# RFBoard.net
KiCad netlist of a schematic drawn in EAGLE
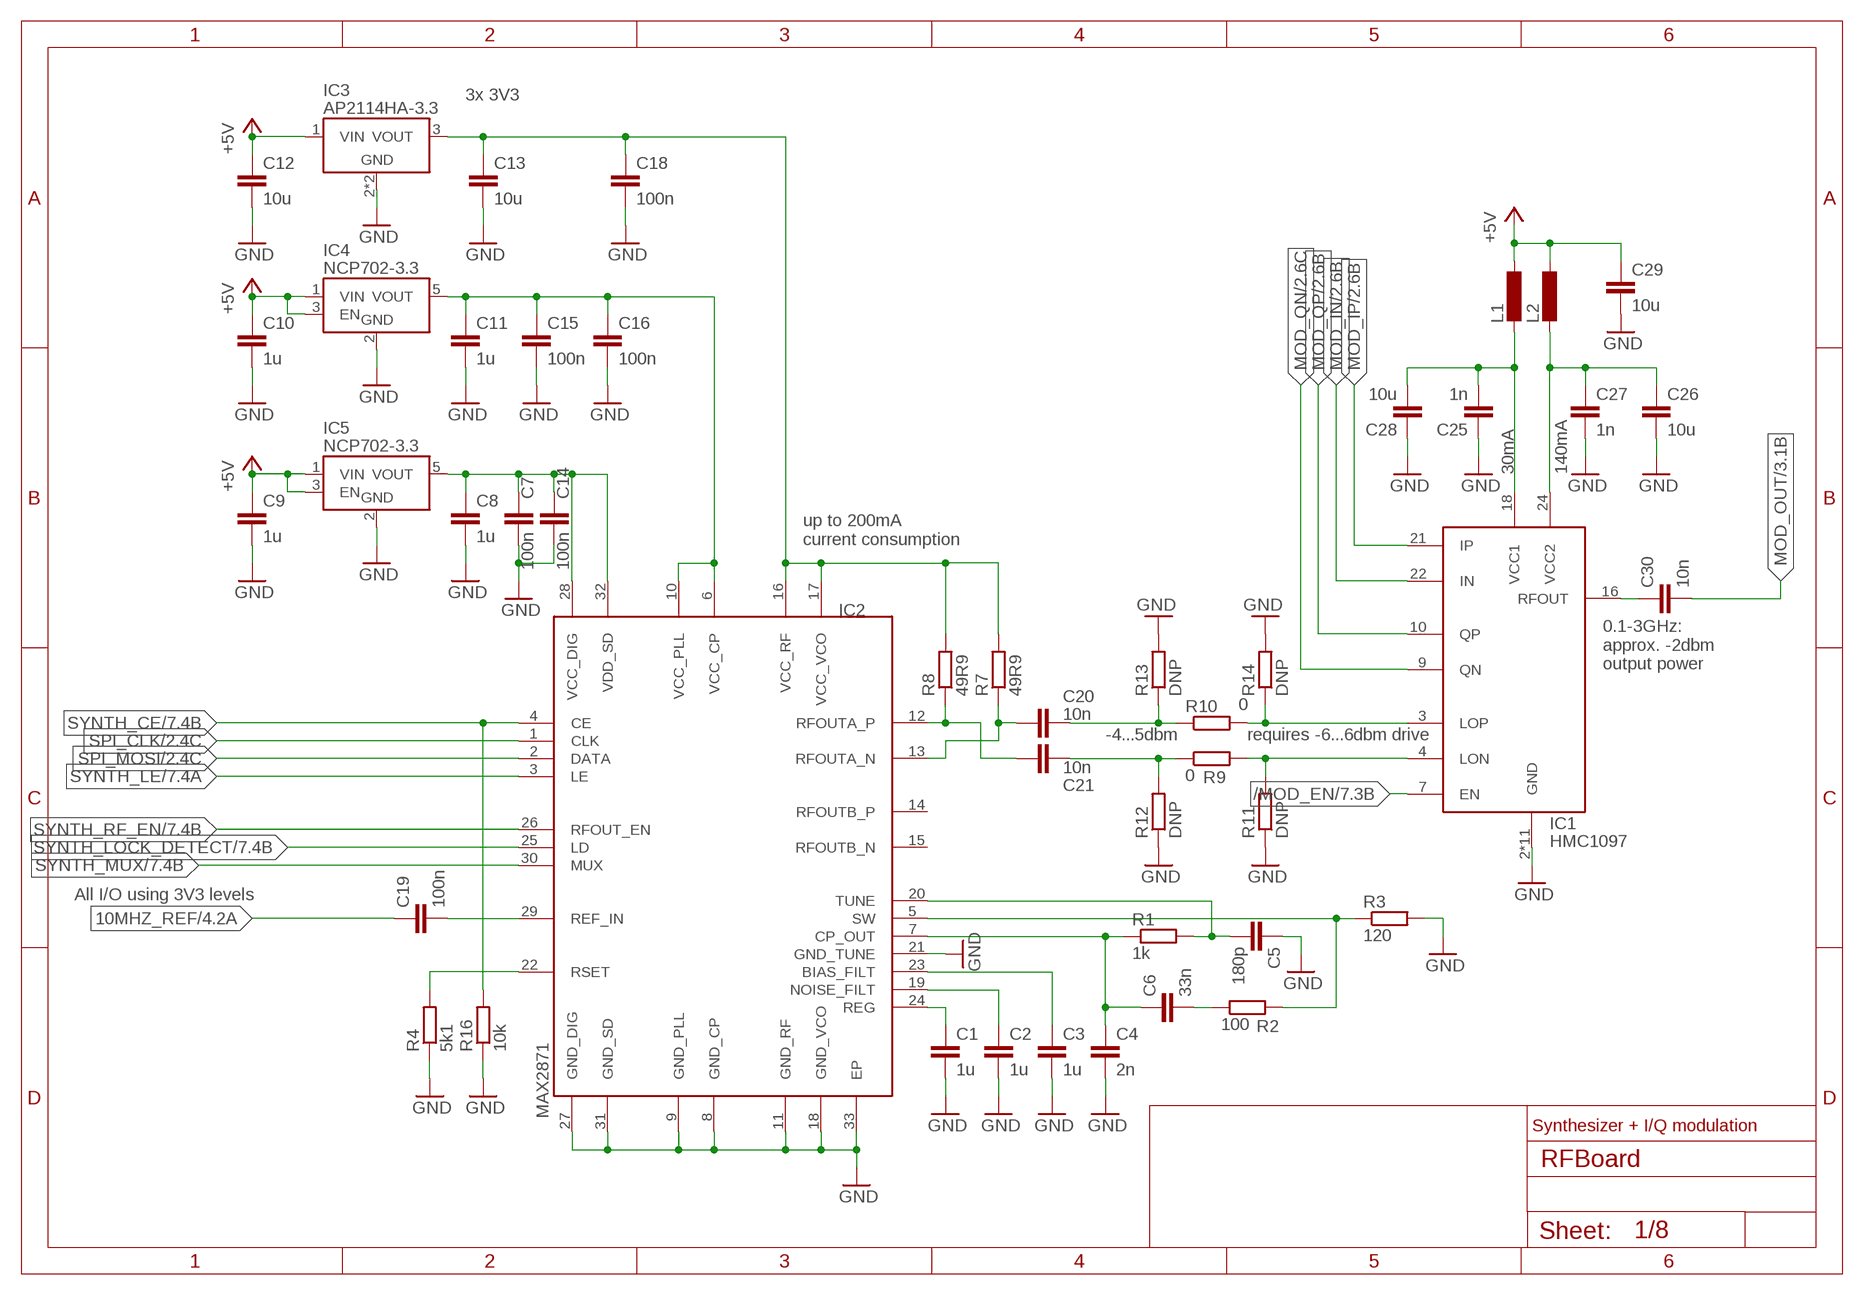
[diagram p0: schematic, sheet 1]
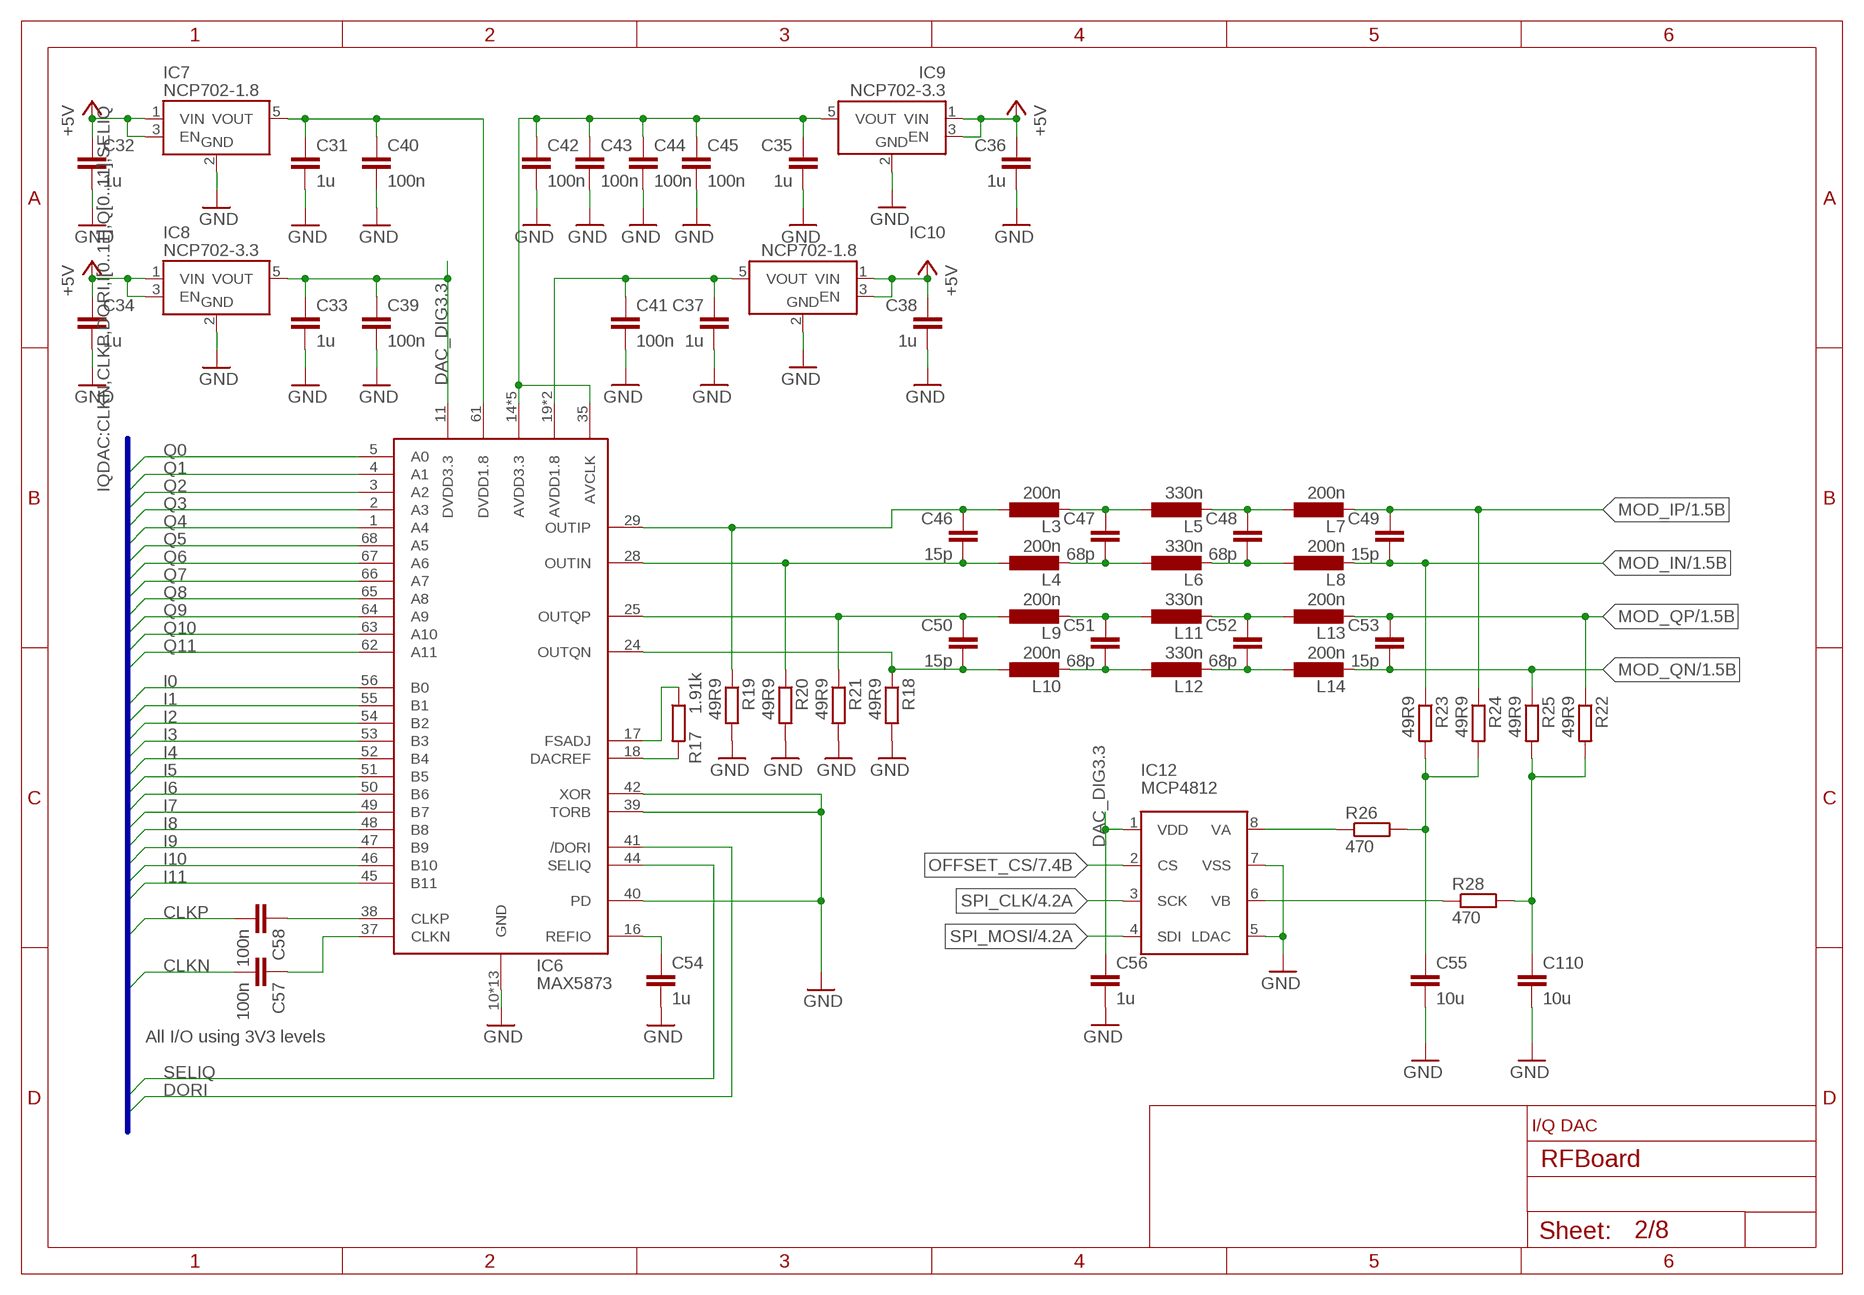
[diagram p1: schematic, sheet 2]
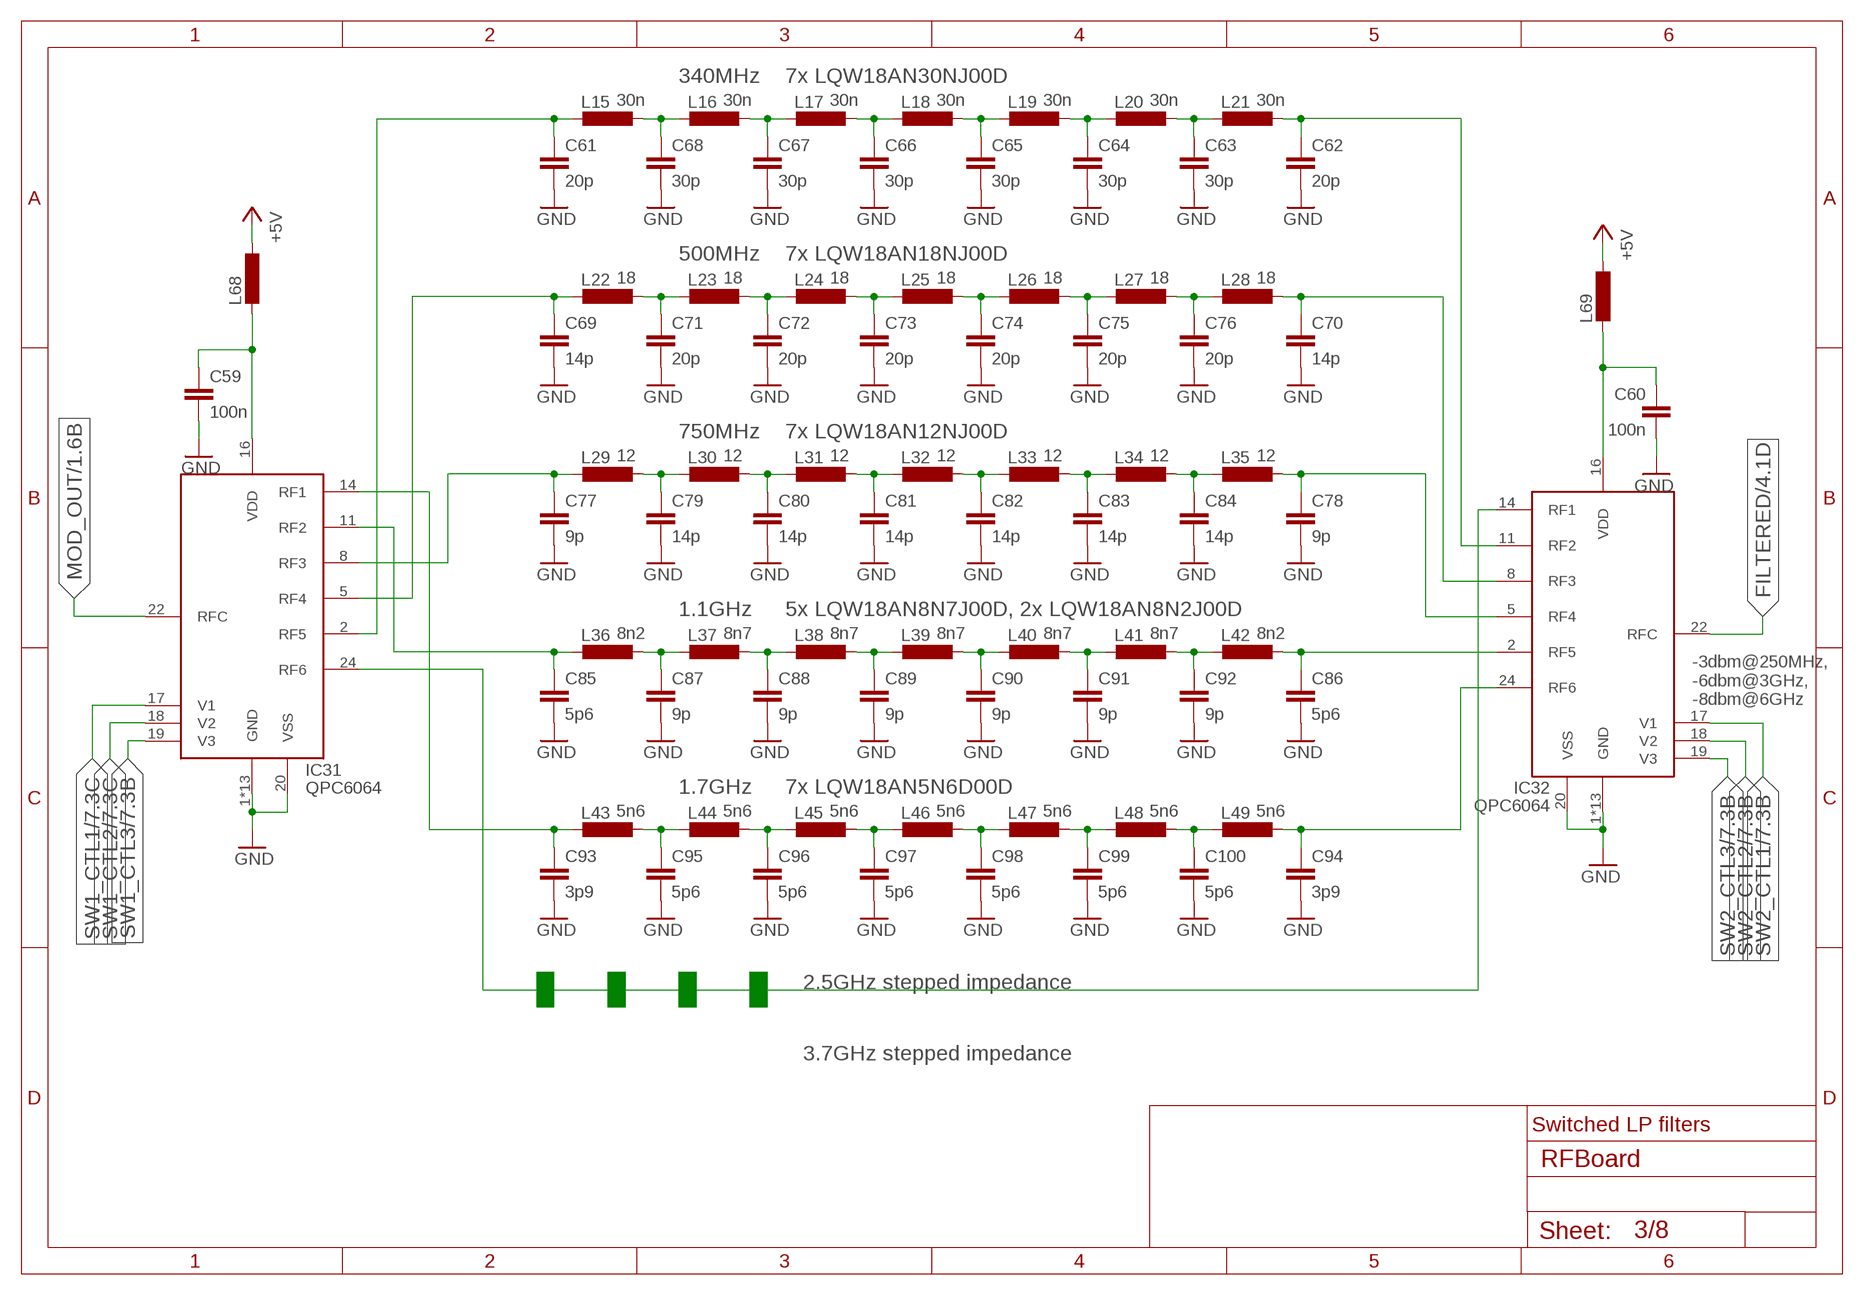
[diagram p2: schematic, sheet 3]
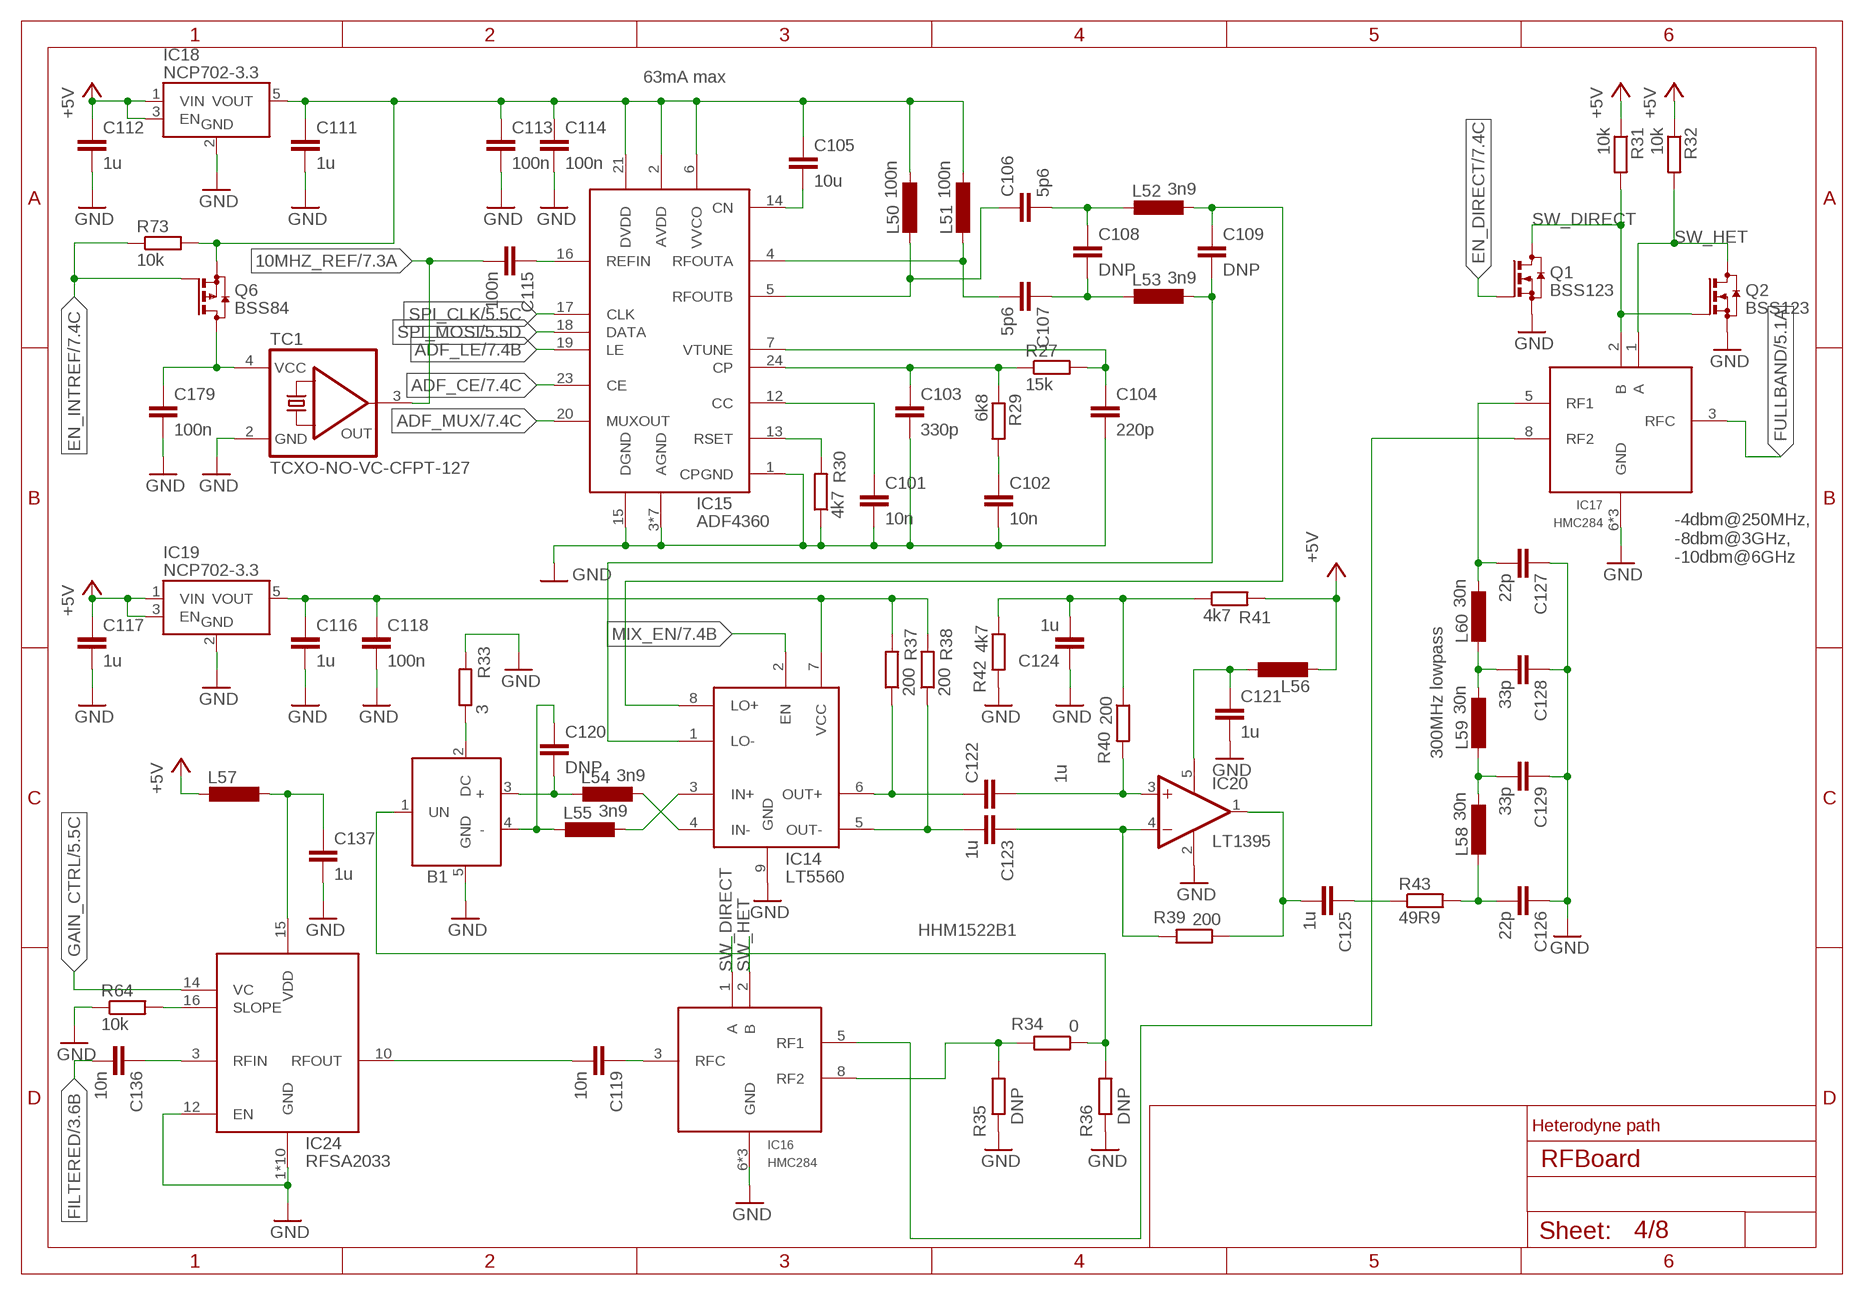
[diagram p3: schematic, sheet 4]
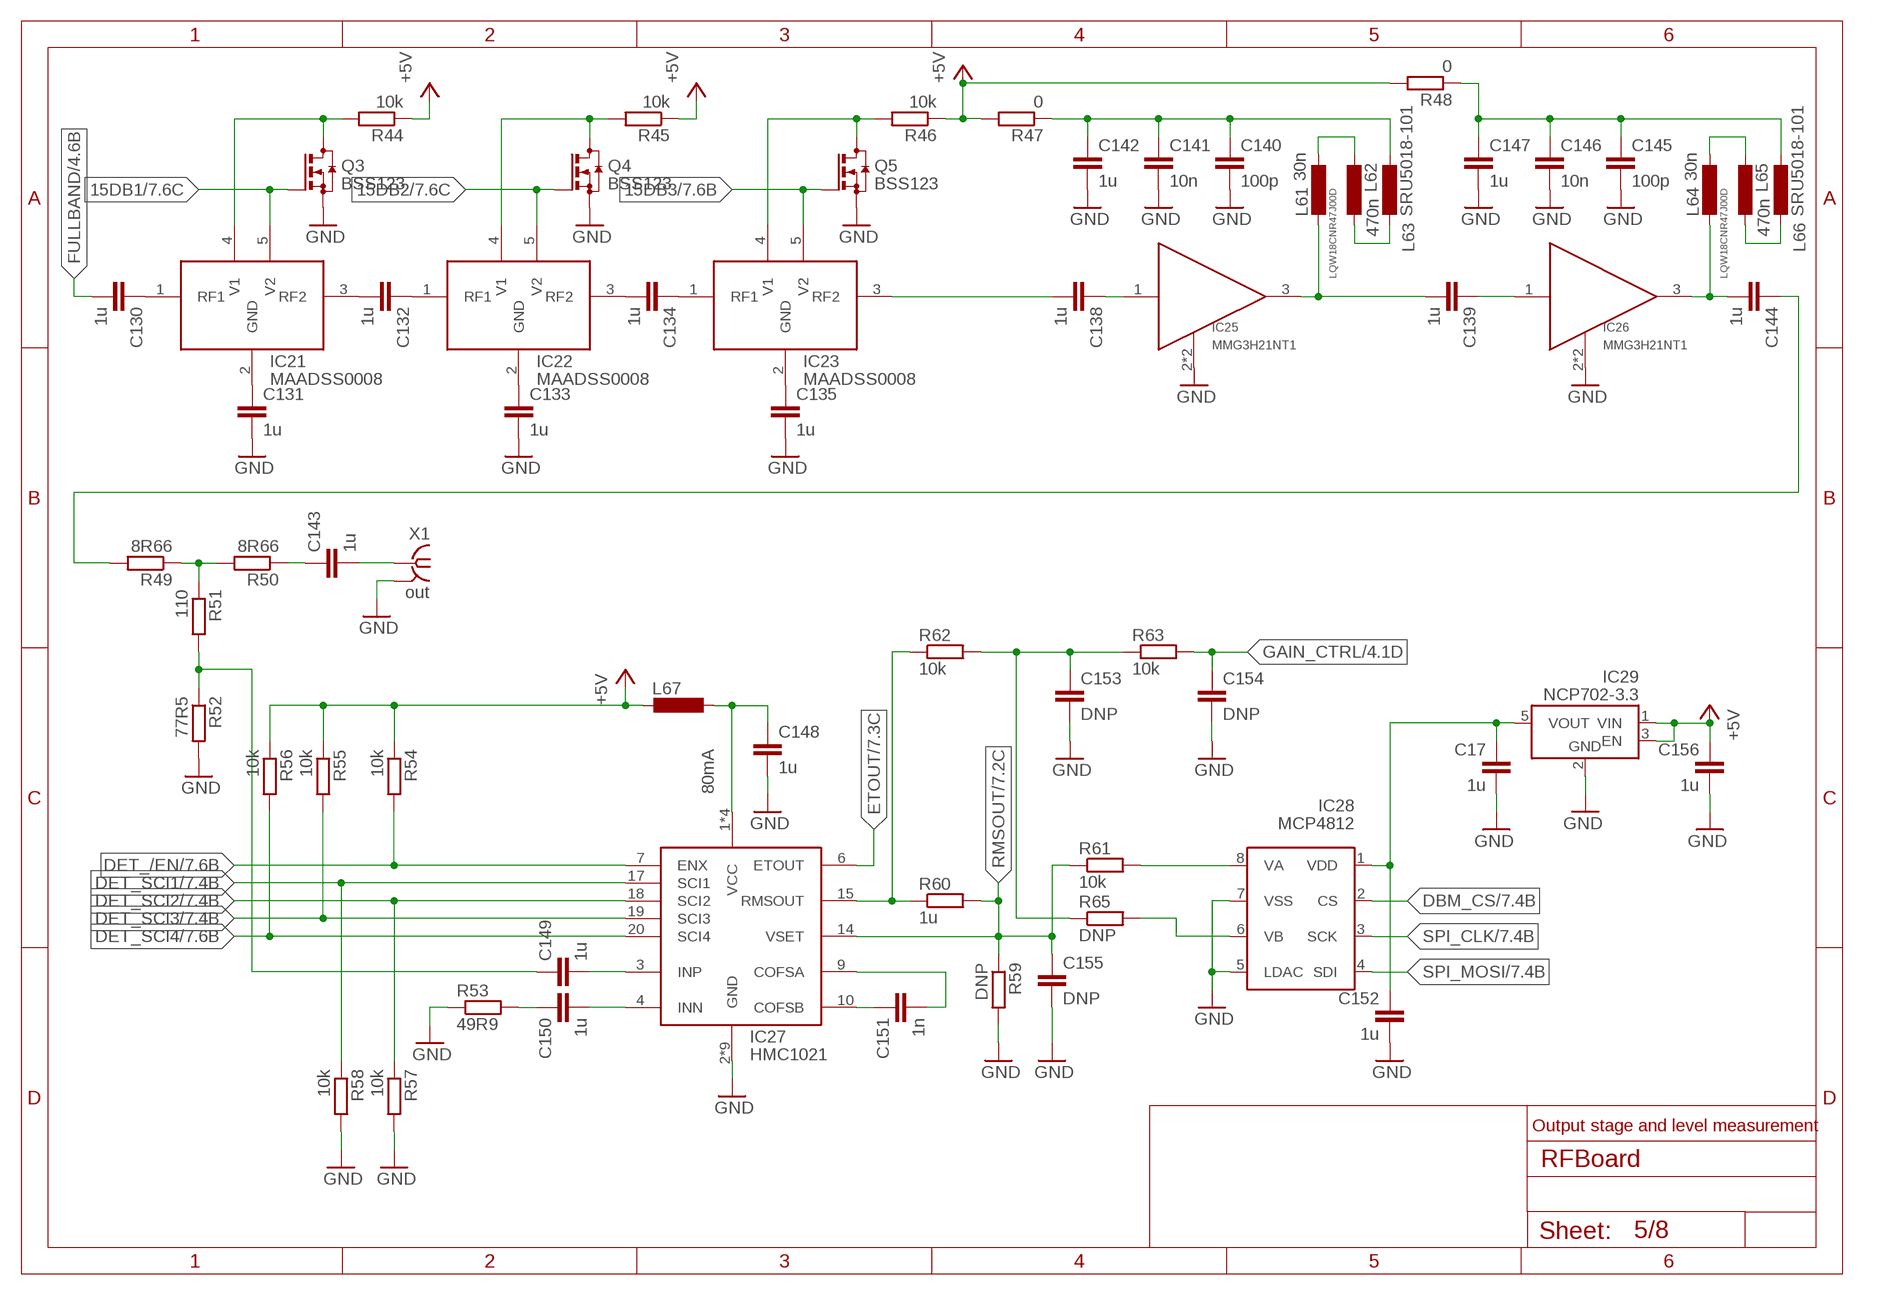
[diagram p4: schematic, sheet 5]
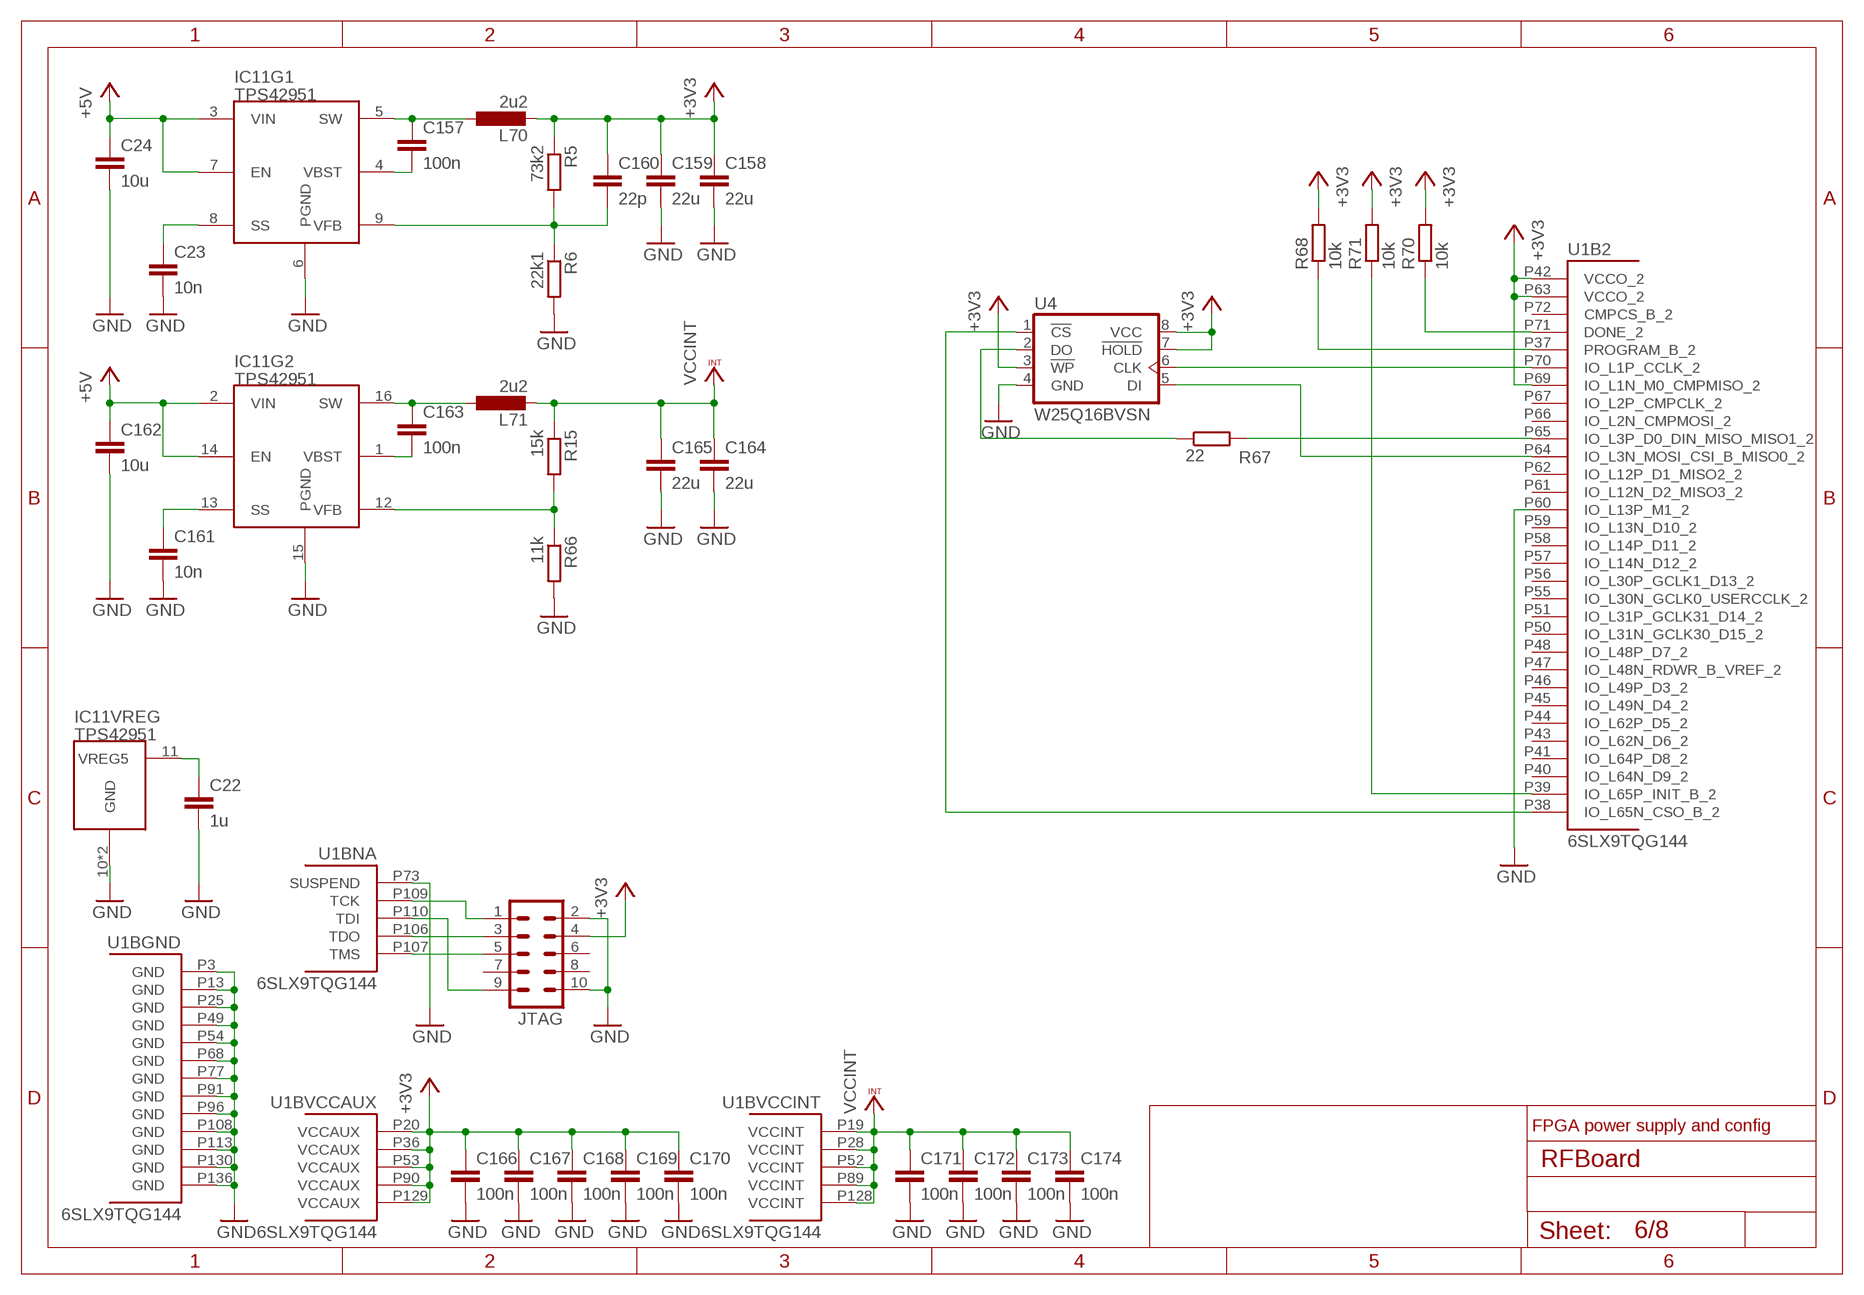
[diagram p5: schematic, sheet 6]
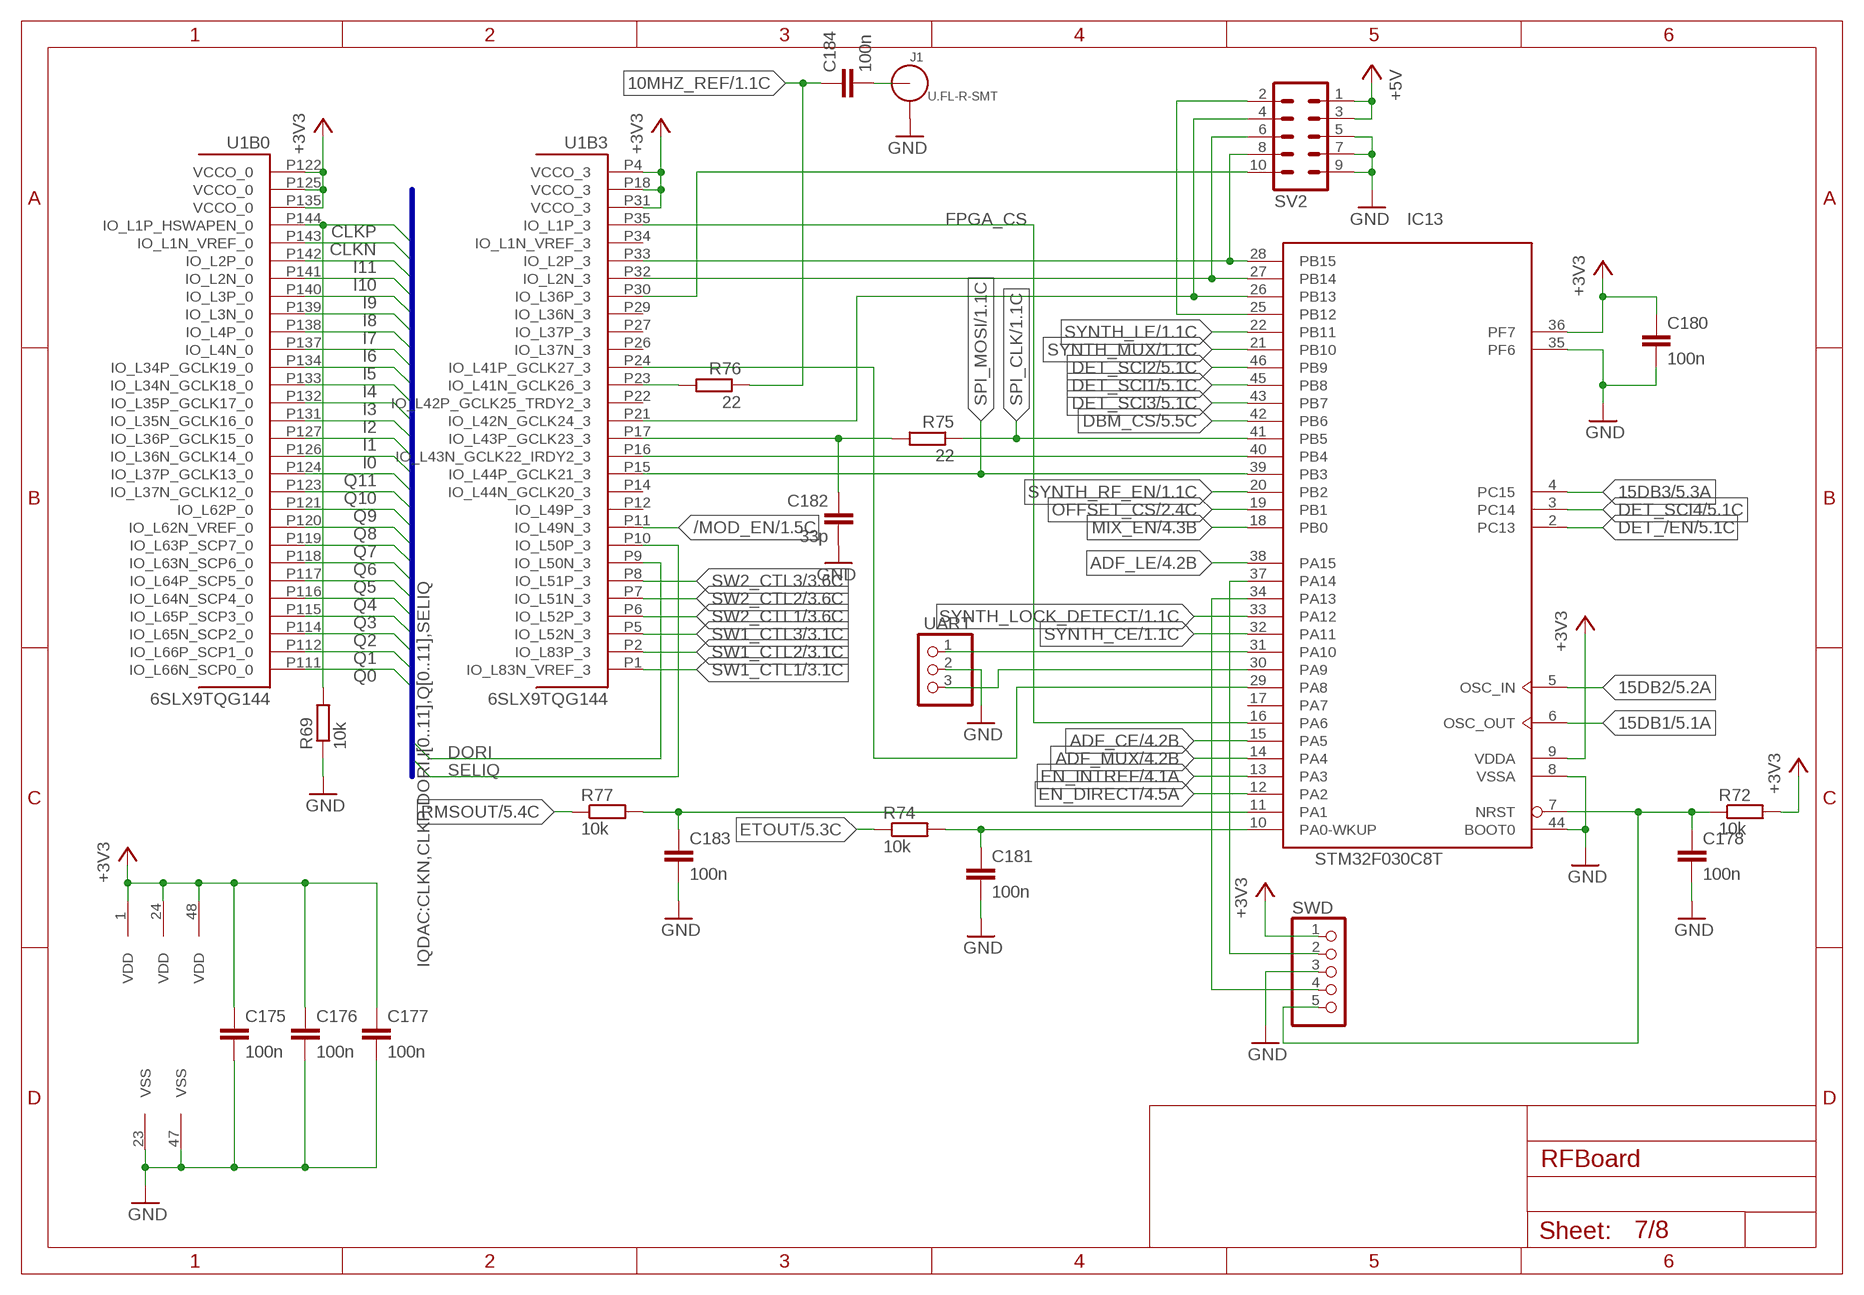
[diagram p6: schematic, sheet 7]
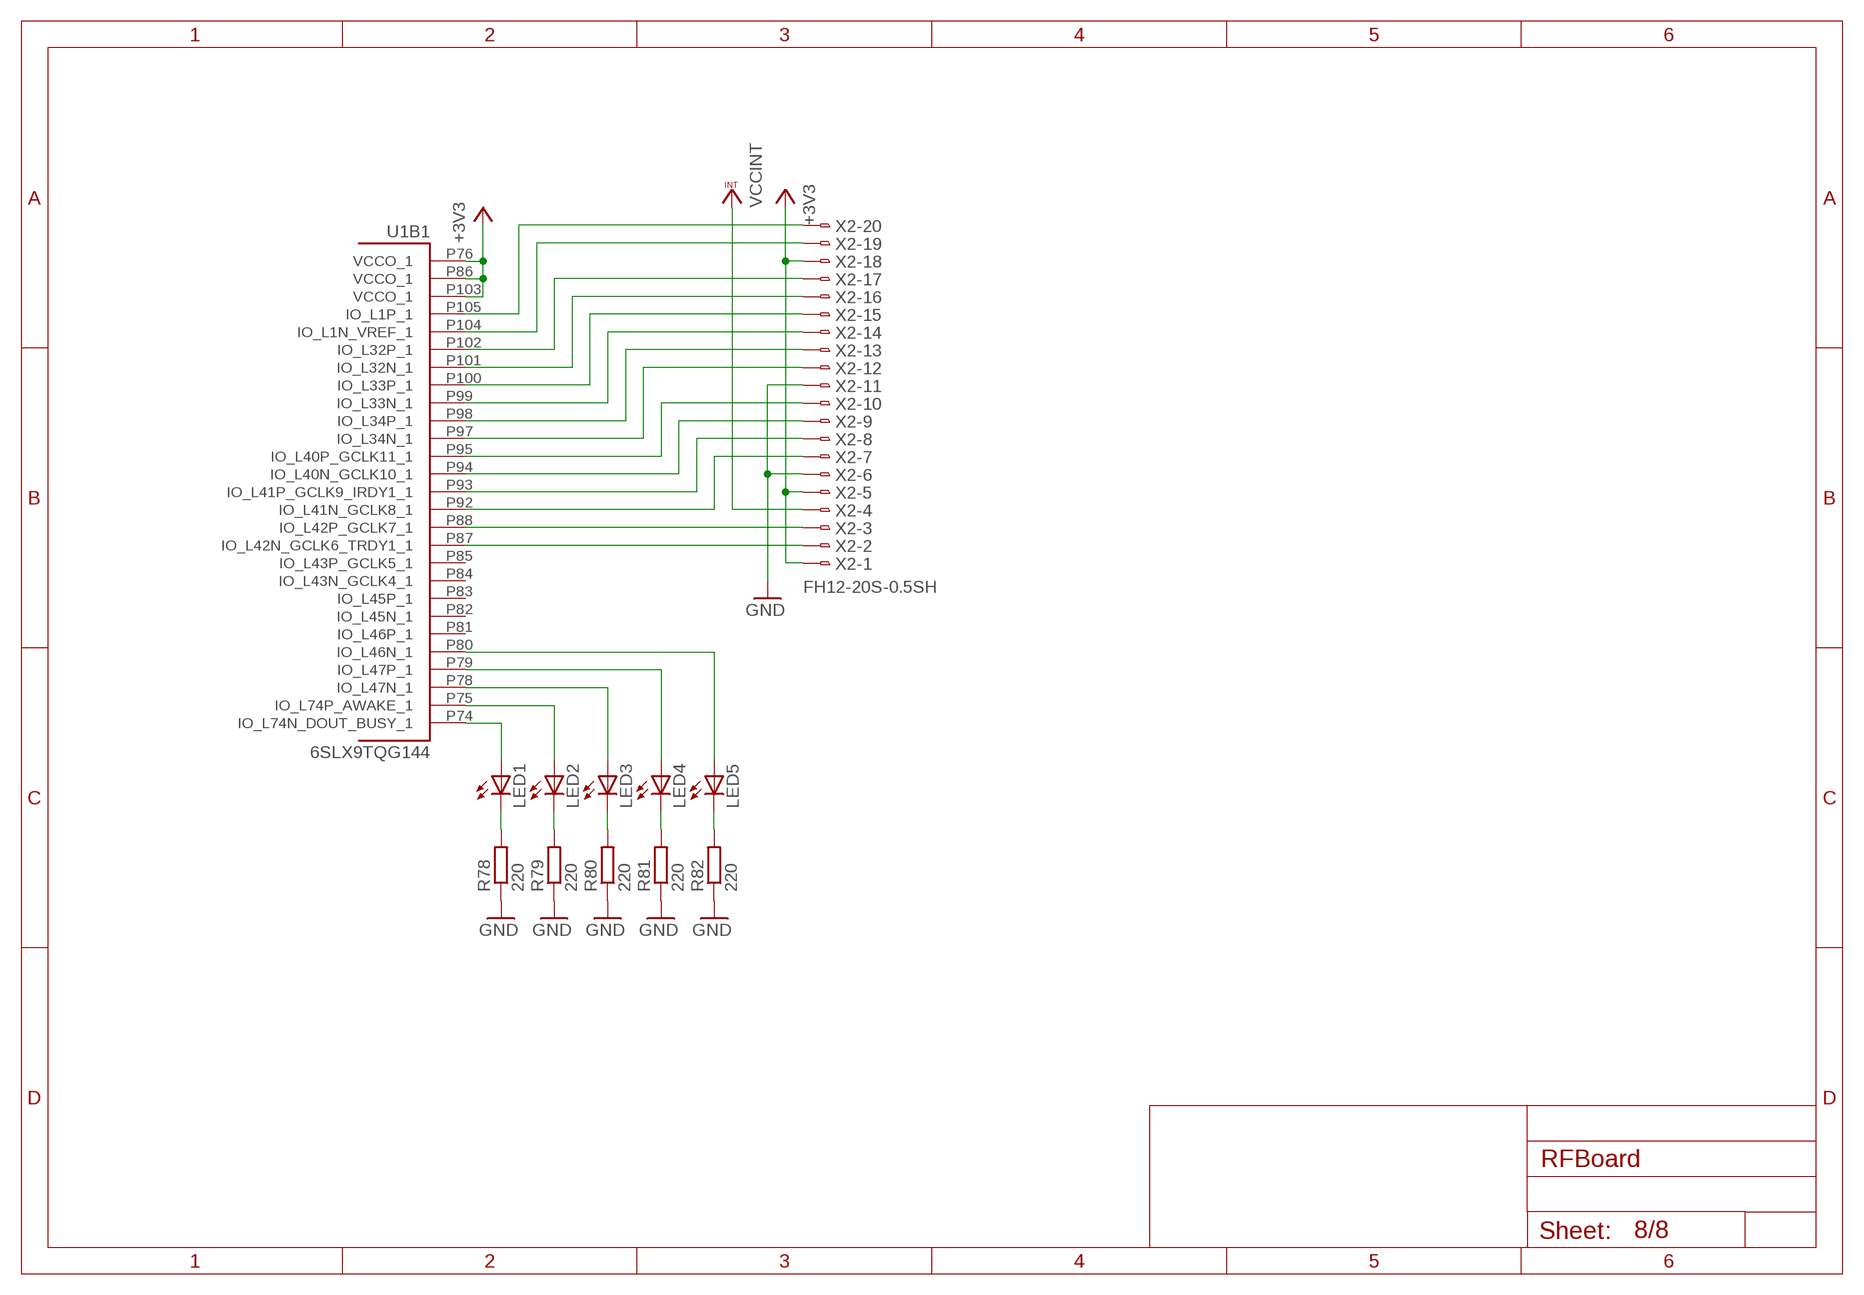
[diagram p7: schematic, sheet 8]

(export (version "E")
  (design (tool "Eeschema 10.0.6"))
  (components
    (comp (ref "C1")
      (value "1u")
      (footprint "eagle-import:C0603")
      (libsource (lib "eagle-import") (part "C-EUC0603"))
    )
    (comp (ref "C2")
      (value "1u")
      (footprint "eagle-import:C0603")
      (libsource (lib "eagle-import") (part "C-EUC0603"))
    )
    (comp (ref "C3")
      (value "1u")
      (footprint "eagle-import:C0603")
      (libsource (lib "eagle-import") (part "C-EUC0603"))
    )
    (comp (ref "C4")
      (value "2n")
      (footprint "eagle-import:C0603")
      (libsource (lib "eagle-import") (part "C-EUC0603"))
    )
    (comp (ref "C5")
      (value "180p")
      (footprint "eagle-import:C0603")
      (libsource (lib "eagle-import") (part "C-EUC0603"))
    )
    (comp (ref "C6")
      (value "33n")
      (footprint "eagle-import:C0603")
      (libsource (lib "eagle-import") (part "C-EUC0603"))
    )
    (comp (ref "C7")
      (value "100n")
      (footprint "eagle-import:C0603")
      (libsource (lib "eagle-import") (part "C-EUC0603"))
    )
    (comp (ref "C8")
      (value "1u")
      (footprint "eagle-import:C0603")
      (libsource (lib "eagle-import") (part "C-EUC0603"))
    )
    (comp (ref "C9")
      (value "1u")
      (footprint "eagle-import:C0603")
      (libsource (lib "eagle-import") (part "C-EUC0603"))
    )
    (comp (ref "C10")
      (value "1u")
      (footprint "eagle-import:C0603")
      (libsource (lib "eagle-import") (part "C-EUC0603"))
    )
    (comp (ref "C11")
      (value "1u")
      (footprint "eagle-import:C0603")
      (libsource (lib "eagle-import") (part "C-EUC0603"))
    )
    (comp (ref "C12")
      (value "10u")
      (footprint "eagle-import:C1206")
      (libsource (lib "eagle-import") (part "C-EUC1206"))
    )
    (comp (ref "C13")
      (value "10u")
      (footprint "eagle-import:C1206")
      (libsource (lib "eagle-import") (part "C-EUC1206"))
    )
    (comp (ref "C14")
      (value "100n")
      (footprint "eagle-import:C0603")
      (libsource (lib "eagle-import") (part "C-EUC0603"))
    )
    (comp (ref "C15")
      (value "100n")
      (footprint "eagle-import:C0603")
      (libsource (lib "eagle-import") (part "C-EUC0603"))
    )
    (comp (ref "C16")
      (value "100n")
      (footprint "eagle-import:C0603")
      (libsource (lib "eagle-import") (part "C-EUC0603"))
    )
    (comp (ref "C18")
      (value "100n")
      (footprint "eagle-import:C0603")
      (libsource (lib "eagle-import") (part "C-EUC0603"))
    )
    (comp (ref "C19")
      (value "100n")
      (footprint "eagle-import:C0603")
      (libsource (lib "eagle-import") (part "C-EUC0603"))
    )
    (comp (ref "C20")
      (value "10n")
      (footprint "eagle-import:C0603")
      (libsource (lib "eagle-import") (part "C-EUC0603"))
    )
    (comp (ref "C21")
      (value "10n")
      (footprint "eagle-import:C0603")
      (libsource (lib "eagle-import") (part "C-EUC0603"))
    )
    (comp (ref "C25")
      (value "1n")
      (footprint "eagle-import:C0603")
      (libsource (lib "eagle-import") (part "C-EUC0603"))
    )
    (comp (ref "C26")
      (value "10u")
      (footprint "eagle-import:C1206")
      (libsource (lib "eagle-import") (part "C-EUC1206"))
    )
    (comp (ref "C27")
      (value "1n")
      (footprint "eagle-import:C0603")
      (libsource (lib "eagle-import") (part "C-EUC0603"))
    )
    (comp (ref "C28")
      (value "10u")
      (footprint "eagle-import:C1206")
      (libsource (lib "eagle-import") (part "C-EUC1206"))
    )
    (comp (ref "C29")
      (value "10u")
      (footprint "eagle-import:C1206")
      (libsource (lib "eagle-import") (part "C-EUC1206"))
    )
    (comp (ref "C30")
      (value "10n")
      (footprint "eagle-import:C0603")
      (libsource (lib "eagle-import") (part "C-EUC0603"))
    )
    (comp (ref "IC1")
      (value "HMC1097")
      (footprint "eagle-import:QFN50P400X400X100-25T280")
      (libsource (lib "eagle-import") (part "HMC1097"))
    )
    (comp (ref "IC2")
      (value "MAX2871")
      (footprint "eagle-import:QFN50P500X500X80-33T310")
      (libsource (lib "eagle-import") (part "MAX2871"))
    )
    (comp (ref "IC3")
      (value "AP2114HA-3.3")
      (footprint "eagle-import:SOT230P700X180-4")
      (libsource (lib "eagle-import") (part "AP2114HA"))
    )
    (comp (ref "IC4")
      (value "NCP702-3.3")
      (footprint "eagle-import:SOT95P240X110-5")
      (libsource (lib "eagle-import") (part "NCP702"))
    )
    (comp (ref "IC5")
      (value "NCP702-3.3")
      (footprint "eagle-import:SOT95P240X110-5")
      (libsource (lib "eagle-import") (part "NCP702"))
    )
    (comp (ref "L1")
      (value "L-EUL2012C")
      (footprint "eagle-import:L2012C")
      (libsource (lib "eagle-import") (part "L-EUL2012C"))
    )
    (comp (ref "L2")
      (value "L-EUL2012C")
      (footprint "eagle-import:L2012C")
      (libsource (lib "eagle-import") (part "L-EUL2012C"))
    )
    (comp (ref "R1")
      (value "1k")
      (footprint "eagle-import:R0603")
      (libsource (lib "eagle-import") (part "resistor_R-EU_R0603"))
    )
    (comp (ref "R2")
      (value "100")
      (footprint "eagle-import:R0603")
      (libsource (lib "eagle-import") (part "resistor_R-EU_R0603"))
    )
    (comp (ref "R3")
      (value "120")
      (footprint "eagle-import:R0603")
      (libsource (lib "eagle-import") (part "resistor_R-EU_R0603"))
    )
    (comp (ref "R4")
      (value "5k1")
      (footprint "eagle-import:R0603")
      (libsource (lib "eagle-import") (part "resistor_R-EU_R0603"))
    )
    (comp (ref "R7")
      (value "49R9")
      (footprint "eagle-import:R0603")
      (libsource (lib "eagle-import") (part "resistor_R-EU_R0603"))
    )
    (comp (ref "R8")
      (value "49R9")
      (footprint "eagle-import:R0603")
      (libsource (lib "eagle-import") (part "resistor_R-EU_R0603"))
    )
    (comp (ref "R9")
      (value "0")
      (footprint "eagle-import:R0603")
      (libsource (lib "eagle-import") (part "resistor_R-EU_R0603"))
    )
    (comp (ref "R10")
      (value "0")
      (footprint "eagle-import:R0603")
      (libsource (lib "eagle-import") (part "resistor_R-EU_R0603"))
    )
    (comp (ref "R11")
      (value "DNP")
      (footprint "eagle-import:R0603")
      (libsource (lib "eagle-import") (part "resistor_R-EU_R0603"))
    )
    (comp (ref "R12")
      (value "DNP")
      (footprint "eagle-import:R0603")
      (libsource (lib "eagle-import") (part "resistor_R-EU_R0603"))
    )
    (comp (ref "R13")
      (value "DNP")
      (footprint "eagle-import:R0603")
      (libsource (lib "eagle-import") (part "resistor_R-EU_R0603"))
    )
    (comp (ref "R14")
      (value "DNP")
      (footprint "eagle-import:R0603")
      (libsource (lib "eagle-import") (part "resistor_R-EU_R0603"))
    )
    (comp (ref "R16")
      (value "10k")
      (footprint "eagle-import:R0603")
      (libsource (lib "eagle-import") (part "resistor_R-EU_R0603"))
    )
    (comp (ref "C175")
      (value "100n")
      (footprint "eagle-import:C0603")
      (libsource (lib "eagle-import") (part "C-EUC0603"))
    )
    (comp (ref "C176")
      (value "100n")
      (footprint "eagle-import:C0603")
      (libsource (lib "eagle-import") (part "C-EUC0603"))
    )
    (comp (ref "C177")
      (value "100n")
      (footprint "eagle-import:C0603")
      (libsource (lib "eagle-import") (part "C-EUC0603"))
    )
    (comp (ref "C178")
      (value "100n")
      (footprint "eagle-import:C0603")
      (libsource (lib "eagle-import") (part "C-EUC0603"))
    )
    (comp (ref "C180")
      (value "100n")
      (footprint "eagle-import:C0603")
      (libsource (lib "eagle-import") (part "C-EUC0603"))
    )
    (comp (ref "C181")
      (value "100n")
      (footprint "eagle-import:C0603")
      (libsource (lib "eagle-import") (part "C-EUC0603"))
    )
    (comp (ref "C182")
      (value "33p")
      (footprint "eagle-import:C0603")
      (libsource (lib "eagle-import") (part "C-EUC0603"))
    )
    (comp (ref "C183")
      (value "100n")
      (footprint "eagle-import:C0603")
      (libsource (lib "eagle-import") (part "C-EUC0603"))
    )
    (comp (ref "C184")
      (value "100n")
      (footprint "eagle-import:C0603")
      (libsource (lib "eagle-import") (part "C-EUC0603"))
    )
    (comp (ref "IC13")
      (value "STM32F030C8T")
      (footprint "eagle-import:LQFP48")
      (libsource (lib "eagle-import") (part "STM32F030CT8"))
    )
    (comp (ref "J1")
      (value "U.FL-R-SMT")
      (footprint "eagle-import:U.FL_SMT")
      (fields (field (name "MANUFACTURER") "Hirose") (field (name "MPN") "U.FL-R-SMT-1(01)"))
      (libsource (lib "eagle-import") (part "U.FL-R-SMT"))
    )
    (comp (ref "R69")
      (value "10k")
      (footprint "eagle-import:R0603")
      (libsource (lib "eagle-import") (part "resistor_R-EU_R0603"))
    )
    (comp (ref "R72")
      (value "10k")
      (footprint "eagle-import:R0603")
      (libsource (lib "eagle-import") (part "resistor_R-EU_R0603"))
    )
    (comp (ref "R74")
      (value "10k")
      (footprint "eagle-import:R0603")
      (libsource (lib "eagle-import") (part "resistor_R-EU_R0603"))
    )
    (comp (ref "R75")
      (value "22")
      (footprint "eagle-import:R0603")
      (libsource (lib "eagle-import") (part "resistor_R-EU_R0603"))
    )
    (comp (ref "R76")
      (value "22")
      (footprint "eagle-import:R0603")
      (libsource (lib "eagle-import") (part "resistor_R-EU_R0603"))
    )
    (comp (ref "R77")
      (value "10k")
      (footprint "eagle-import:R0603")
      (libsource (lib "eagle-import") (part "resistor_R-EU_R0603"))
    )
    (comp (ref "SV2")
      (value "ML10")
      (footprint "eagle-import:ML10")
      (libsource (lib "eagle-import") (part "ML10"))
    )
    (comp (ref "SWD")
      (value "PINHD-1X5")
      (footprint "eagle-import:1X05")
      (libsource (lib "eagle-import") (part "PINHD-1X5"))
    )
    (comp (ref "U1")
      (value "6SLX9TQG144")
      (footprint "eagle-import:TQ144")
      (libsource (lib "eagle-import") (part "6SLX9TQG144"))
    )
    (comp (ref "UART")
      (value "PINHD-1X3")
      (footprint "eagle-import:1X03")
      (libsource (lib "eagle-import") (part "PINHD-1X3"))
    )
    (comp (ref "C17")
      (value "1u")
      (footprint "eagle-import:C0603")
      (libsource (lib "eagle-import") (part "C-EUC0603"))
    )
    (comp (ref "C130")
      (value "1u")
      (footprint "eagle-import:C0603")
      (libsource (lib "eagle-import") (part "C-EUC0603"))
    )
    (comp (ref "C131")
      (value "1u")
      (footprint "eagle-import:C0603")
      (libsource (lib "eagle-import") (part "C-EUC0603"))
    )
    (comp (ref "C132")
      (value "1u")
      (footprint "eagle-import:C0603")
      (libsource (lib "eagle-import") (part "C-EUC0603"))
    )
    (comp (ref "C133")
      (value "1u")
      (footprint "eagle-import:C0603")
      (libsource (lib "eagle-import") (part "C-EUC0603"))
    )
    (comp (ref "C134")
      (value "1u")
      (footprint "eagle-import:C0603")
      (libsource (lib "eagle-import") (part "C-EUC0603"))
    )
    (comp (ref "C135")
      (value "1u")
      (footprint "eagle-import:C0603")
      (libsource (lib "eagle-import") (part "C-EUC0603"))
    )
    (comp (ref "C138")
      (value "1u")
      (footprint "eagle-import:C0603")
      (libsource (lib "eagle-import") (part "C-EUC0603"))
    )
    (comp (ref "C139")
      (value "1u")
      (footprint "eagle-import:C0603")
      (libsource (lib "eagle-import") (part "C-EUC0603"))
    )
    (comp (ref "C140")
      (value "100p")
      (footprint "eagle-import:C0603")
      (libsource (lib "eagle-import") (part "C-EUC0603"))
    )
    (comp (ref "C141")
      (value "10n")
      (footprint "eagle-import:C0603")
      (libsource (lib "eagle-import") (part "C-EUC0603"))
    )
    (comp (ref "C142")
      (value "1u")
      (footprint "eagle-import:C0603")
      (libsource (lib "eagle-import") (part "C-EUC0603"))
    )
    (comp (ref "C143")
      (value "1u")
      (footprint "eagle-import:C0603")
      (libsource (lib "eagle-import") (part "C-EUC0603"))
    )
    (comp (ref "C144")
      (value "1u")
      (footprint "eagle-import:C0603")
      (libsource (lib "eagle-import") (part "C-EUC0603"))
    )
    (comp (ref "C145")
      (value "100p")
      (footprint "eagle-import:C0603")
      (libsource (lib "eagle-import") (part "C-EUC0603"))
    )
    (comp (ref "C146")
      (value "10n")
      (footprint "eagle-import:C0603")
      (libsource (lib "eagle-import") (part "C-EUC0603"))
    )
    (comp (ref "C147")
      (value "1u")
      (footprint "eagle-import:C0603")
      (libsource (lib "eagle-import") (part "C-EUC0603"))
    )
    (comp (ref "C148")
      (value "1u")
      (footprint "eagle-import:C0603")
      (libsource (lib "eagle-import") (part "C-EUC0603"))
    )
    (comp (ref "C149")
      (value "1u")
      (footprint "eagle-import:C0603")
      (libsource (lib "eagle-import") (part "C-EUC0603"))
    )
    (comp (ref "C150")
      (value "1u")
      (footprint "eagle-import:C0603")
      (libsource (lib "eagle-import") (part "C-EUC0603"))
    )
    (comp (ref "C151")
      (value "1n")
      (footprint "eagle-import:C0603")
      (libsource (lib "eagle-import") (part "C-EUC0603"))
    )
    (comp (ref "C152")
      (value "1u")
      (footprint "eagle-import:C0603")
      (libsource (lib "eagle-import") (part "C-EUC0603"))
    )
    (comp (ref "C153")
      (value "DNP")
      (footprint "eagle-import:C0603")
      (libsource (lib "eagle-import") (part "C-EUC0603"))
    )
    (comp (ref "C154")
      (value "DNP")
      (footprint "eagle-import:C0603")
      (libsource (lib "eagle-import") (part "C-EUC0603"))
    )
    (comp (ref "C155")
      (value "DNP")
      (footprint "eagle-import:C0603")
      (libsource (lib "eagle-import") (part "C-EUC0603"))
    )
    (comp (ref "C156")
      (value "1u")
      (footprint "eagle-import:C0603")
      (libsource (lib "eagle-import") (part "C-EUC0603"))
    )
    (comp (ref "IC21")
      (value "MAADSS0008")
      (footprint "eagle-import:SOT95P280X110-5")
      (libsource (lib "eagle-import") (part "MAADSS0008"))
    )
    (comp (ref "IC22")
      (value "MAADSS0008")
      (footprint "eagle-import:SOT95P280X110-5")
      (libsource (lib "eagle-import") (part "MAADSS0008"))
    )
    (comp (ref "IC23")
      (value "MAADSS0008")
      (footprint "eagle-import:SOT95P280X110-5")
      (libsource (lib "eagle-import") (part "MAADSS0008"))
    )
    (comp (ref "IC25")
      (value "MMG3H21NT1")
      (footprint "eagle-import:SOT89")
      (libsource (lib "eagle-import") (part "HMC480"))
    )
    (comp (ref "IC26")
      (value "MMG3H21NT1")
      (footprint "eagle-import:SOT89")
      (libsource (lib "eagle-import") (part "HMC480"))
    )
    (comp (ref "IC27")
      (value "HMC1021")
      (footprint "eagle-import:QFN50P400X400X100-25T270")
      (libsource (lib "eagle-import") (part "HMC1021"))
    )
    (comp (ref "IC28")
      (value "MCP4812")
      (footprint "eagle-import:SO08")
      (fields (field (name "MPN") "MCP4822-E/SN"))
      (libsource (lib "eagle-import") (part "MCP4812"))
    )
    (comp (ref "IC29")
      (value "NCP702-3.3")
      (footprint "eagle-import:SOT95P240X110-5")
      (libsource (lib "eagle-import") (part "NCP702"))
    )
    (comp (ref "L61")
      (value "30n")
      (footprint "eagle-import:R0603")
      (libsource (lib "eagle-import") (part "INDUCTOR0603"))
    )
    (comp (ref "L62")
      (value "470n")
      (footprint "eagle-import:R0603")
      (libsource (lib "eagle-import") (part "INDUCTOR0603"))
    )
    (comp (ref "L63")
      (value "SRU5018-101")
      (footprint "eagle-import:SMD5018")
      (libsource (lib "eagle-import") (part "INDUCTOR5018"))
    )
    (comp (ref "L64")
      (value "30n")
      (footprint "eagle-import:R0603")
      (libsource (lib "eagle-import") (part "INDUCTOR0603"))
    )
    (comp (ref "L65")
      (value "470n")
      (footprint "eagle-import:R0603")
      (libsource (lib "eagle-import") (part "INDUCTOR0603"))
    )
    (comp (ref "L66")
      (value "SRU5018-101")
      (footprint "eagle-import:SMD5018")
      (libsource (lib "eagle-import") (part "INDUCTOR5018"))
    )
    (comp (ref "L67")
      (value "L-EUL2012C")
      (footprint "eagle-import:L2012C")
      (libsource (lib "eagle-import") (part "L-EUL2012C"))
    )
    (comp (ref "Q3")
      (value "BSS123")
      (footprint "eagle-import:SOT23")
      (libsource (lib "eagle-import") (part "BSS123"))
    )
    (comp (ref "Q4")
      (value "BSS123")
      (footprint "eagle-import:SOT23")
      (libsource (lib "eagle-import") (part "BSS123"))
    )
    (comp (ref "Q5")
      (value "BSS123")
      (footprint "eagle-import:SOT23")
      (libsource (lib "eagle-import") (part "BSS123"))
    )
    (comp (ref "R44")
      (value "10k")
      (footprint "eagle-import:R0603")
      (libsource (lib "eagle-import") (part "resistor_R-EU_R0603"))
    )
    (comp (ref "R45")
      (value "10k")
      (footprint "eagle-import:R0603")
      (libsource (lib "eagle-import") (part "resistor_R-EU_R0603"))
    )
    (comp (ref "R46")
      (value "10k")
      (footprint "eagle-import:R0603")
      (libsource (lib "eagle-import") (part "resistor_R-EU_R0603"))
    )
    (comp (ref "R47")
      (value "0")
      (footprint "eagle-import:R0603")
      (libsource (lib "eagle-import") (part "resistor_R-EU_R0603"))
    )
    (comp (ref "R48")
      (value "0")
      (footprint "eagle-import:R0603")
      (libsource (lib "eagle-import") (part "resistor_R-EU_R0603"))
    )
    (comp (ref "R49")
      (value "8R66")
      (footprint "eagle-import:R0603")
      (libsource (lib "eagle-import") (part "resistor_R-EU_R0603"))
    )
    (comp (ref "R50")
      (value "8R66")
      (footprint "eagle-import:R0603")
      (libsource (lib "eagle-import") (part "resistor_R-EU_R0603"))
    )
    (comp (ref "R51")
      (value "110")
      (footprint "eagle-import:R0603")
      (libsource (lib "eagle-import") (part "resistor_R-EU_R0603"))
    )
    (comp (ref "R52")
      (value "77R5")
      (footprint "eagle-import:R0603")
      (libsource (lib "eagle-import") (part "resistor_R-EU_R0603"))
    )
    (comp (ref "R53")
      (value "49R9")
      (footprint "eagle-import:R0603")
      (libsource (lib "eagle-import") (part "R-EU_R0603"))
    )
    (comp (ref "R54")
      (value "10k")
      (footprint "eagle-import:R0603")
      (libsource (lib "eagle-import") (part "resistor_R-EU_R0603"))
    )
    (comp (ref "R55")
      (value "10k")
      (footprint "eagle-import:R0603")
      (libsource (lib "eagle-import") (part "resistor_R-EU_R0603"))
    )
    (comp (ref "R56")
      (value "10k")
      (footprint "eagle-import:R0603")
      (libsource (lib "eagle-import") (part "resistor_R-EU_R0603"))
    )
    (comp (ref "R57")
      (value "10k")
      (footprint "eagle-import:R0603")
      (libsource (lib "eagle-import") (part "resistor_R-EU_R0603"))
    )
    (comp (ref "R58")
      (value "10k")
      (footprint "eagle-import:R0603")
      (libsource (lib "eagle-import") (part "resistor_R-EU_R0603"))
    )
    (comp (ref "R59")
      (value "DNP")
      (footprint "eagle-import:R0603")
      (libsource (lib "eagle-import") (part "resistor_R-EU_R0603"))
    )
    (comp (ref "R60")
      (value "1u")
      (footprint "eagle-import:R0603")
      (libsource (lib "eagle-import") (part "resistor_R-EU_R0603"))
    )
    (comp (ref "R61")
      (value "10k")
      (footprint "eagle-import:R0603")
      (libsource (lib "eagle-import") (part "resistor_R-EU_R0603"))
    )
    (comp (ref "R62")
      (value "10k")
      (footprint "eagle-import:R0603")
      (libsource (lib "eagle-import") (part "resistor_R-EU_R0603"))
    )
    (comp (ref "R63")
      (value "10k")
      (footprint "eagle-import:R0603")
      (libsource (lib "eagle-import") (part "resistor_R-EU_R0603"))
    )
    (comp (ref "R65")
      (value "DNP")
      (footprint "eagle-import:R0603")
      (libsource (lib "eagle-import") (part "resistor_R-EU_R0603"))
    )
    (comp (ref "X1")
      (value "out")
      (footprint "eagle-import:J502-ND-142-0711-821_826")
      (libsource (lib "eagle-import") (part "SMA_CONNECTOR"))
    )
    (comp (ref "C31")
      (value "1u")
      (footprint "eagle-import:C0603")
      (libsource (lib "eagle-import") (part "C-EUC0603"))
    )
    (comp (ref "C32")
      (value "1u")
      (footprint "eagle-import:C0603")
      (libsource (lib "eagle-import") (part "C-EUC0603"))
    )
    (comp (ref "C33")
      (value "1u")
      (footprint "eagle-import:C0603")
      (libsource (lib "eagle-import") (part "C-EUC0603"))
    )
    (comp (ref "C34")
      (value "1u")
      (footprint "eagle-import:C0603")
      (libsource (lib "eagle-import") (part "C-EUC0603"))
    )
    (comp (ref "C35")
      (value "1u")
      (footprint "eagle-import:C0603")
      (libsource (lib "eagle-import") (part "C-EUC0603"))
    )
    (comp (ref "C36")
      (value "1u")
      (footprint "eagle-import:C0603")
      (libsource (lib "eagle-import") (part "C-EUC0603"))
    )
    (comp (ref "C37")
      (value "1u")
      (footprint "eagle-import:C0603")
      (libsource (lib "eagle-import") (part "C-EUC0603"))
    )
    (comp (ref "C38")
      (value "1u")
      (footprint "eagle-import:C0603")
      (libsource (lib "eagle-import") (part "C-EUC0603"))
    )
    (comp (ref "C39")
      (value "100n")
      (footprint "eagle-import:C0603")
      (libsource (lib "eagle-import") (part "C-EUC0603"))
    )
    (comp (ref "C40")
      (value "100n")
      (footprint "eagle-import:C0603")
      (libsource (lib "eagle-import") (part "C-EUC0603"))
    )
    (comp (ref "C41")
      (value "100n")
      (footprint "eagle-import:C0603")
      (libsource (lib "eagle-import") (part "C-EUC0603"))
    )
    (comp (ref "C42")
      (value "100n")
      (footprint "eagle-import:C0603")
      (libsource (lib "eagle-import") (part "C-EUC0603"))
    )
    (comp (ref "C43")
      (value "100n")
      (footprint "eagle-import:C0603")
      (libsource (lib "eagle-import") (part "C-EUC0603"))
    )
    (comp (ref "C44")
      (value "100n")
      (footprint "eagle-import:C0603")
      (libsource (lib "eagle-import") (part "C-EUC0603"))
    )
    (comp (ref "C45")
      (value "100n")
      (footprint "eagle-import:C0603")
      (libsource (lib "eagle-import") (part "C-EUC0603"))
    )
    (comp (ref "C46")
      (value "15p")
      (footprint "eagle-import:C0603")
      (libsource (lib "eagle-import") (part "C-EUC0603"))
    )
    (comp (ref "C47")
      (value "68p")
      (footprint "eagle-import:C0603")
      (libsource (lib "eagle-import") (part "C-EUC0603"))
    )
    (comp (ref "C48")
      (value "68p")
      (footprint "eagle-import:C0603")
      (libsource (lib "eagle-import") (part "C-EUC0603"))
    )
    (comp (ref "C49")
      (value "15p")
      (footprint "eagle-import:C0603")
      (libsource (lib "eagle-import") (part "C-EUC0603"))
    )
    (comp (ref "C50")
      (value "15p")
      (footprint "eagle-import:C0603")
      (libsource (lib "eagle-import") (part "C-EUC0603"))
    )
    (comp (ref "C51")
      (value "68p")
      (footprint "eagle-import:C0603")
      (libsource (lib "eagle-import") (part "C-EUC0603"))
    )
    (comp (ref "C52")
      (value "68p")
      (footprint "eagle-import:C0603")
      (libsource (lib "eagle-import") (part "C-EUC0603"))
    )
    (comp (ref "C53")
      (value "15p")
      (footprint "eagle-import:C0603")
      (libsource (lib "eagle-import") (part "C-EUC0603"))
    )
    (comp (ref "C54")
      (value "1u")
      (footprint "eagle-import:C0603")
      (libsource (lib "eagle-import") (part "C-EUC0603"))
    )
    (comp (ref "C55")
      (value "10u")
      (footprint "eagle-import:C0603")
      (libsource (lib "eagle-import") (part "C-EUC0603"))
    )
    (comp (ref "C56")
      (value "1u")
      (footprint "eagle-import:C0603")
      (libsource (lib "eagle-import") (part "C-EUC0603"))
    )
    (comp (ref "C57")
      (value "100n")
      (footprint "eagle-import:C0603")
      (libsource (lib "eagle-import") (part "C-EUC0603"))
    )
    (comp (ref "C58")
      (value "100n")
      (footprint "eagle-import:C0603")
      (libsource (lib "eagle-import") (part "C-EUC0603"))
    )
    (comp (ref "C110")
      (value "10u")
      (footprint "eagle-import:C0603")
      (libsource (lib "eagle-import") (part "C-EUC0603"))
    )
    (comp (ref "IC6")
      (value "MAX5873")
      (footprint "eagle-import:QFN50P1000X1000X100-69T770")
      (libsource (lib "eagle-import") (part "MAX5873"))
    )
    (comp (ref "IC7")
      (value "NCP702-1.8")
      (footprint "eagle-import:SOT95P240X110-5")
      (libsource (lib "eagle-import") (part "NCP702"))
    )
    (comp (ref "IC8")
      (value "NCP702-3.3")
      (footprint "eagle-import:SOT95P240X110-5")
      (libsource (lib "eagle-import") (part "NCP702"))
    )
    (comp (ref "IC9")
      (value "NCP702-3.3")
      (footprint "eagle-import:SOT95P240X110-5")
      (libsource (lib "eagle-import") (part "NCP702"))
    )
    (comp (ref "IC10")
      (value "NCP702-1.8")
      (footprint "eagle-import:SOT95P240X110-5")
      (libsource (lib "eagle-import") (part "NCP702"))
    )
    (comp (ref "IC12")
      (value "MCP4812")
      (footprint "eagle-import:SO08")
      (fields (field (name "MPN") "MCP4822-E/SN"))
      (libsource (lib "eagle-import") (part "MCP4812"))
    )
    (comp (ref "L3")
      (value "200n")
      (footprint "eagle-import:R0603")
      (libsource (lib "eagle-import") (part "INDUCTOR0603"))
    )
    (comp (ref "L4")
      (value "200n")
      (footprint "eagle-import:R0603")
      (libsource (lib "eagle-import") (part "INDUCTOR0603"))
    )
    (comp (ref "L5")
      (value "330n")
      (footprint "eagle-import:R0603")
      (libsource (lib "eagle-import") (part "INDUCTOR0603"))
    )
    (comp (ref "L6")
      (value "330n")
      (footprint "eagle-import:R0603")
      (libsource (lib "eagle-import") (part "INDUCTOR0603"))
    )
    (comp (ref "L7")
      (value "200n")
      (footprint "eagle-import:R0603")
      (libsource (lib "eagle-import") (part "INDUCTOR0603"))
    )
    (comp (ref "L8")
      (value "200n")
      (footprint "eagle-import:R0603")
      (libsource (lib "eagle-import") (part "INDUCTOR0603"))
    )
    (comp (ref "L9")
      (value "200n")
      (footprint "eagle-import:R0603")
      (libsource (lib "eagle-import") (part "INDUCTOR0603"))
    )
    (comp (ref "L10")
      (value "200n")
      (footprint "eagle-import:R0603")
      (libsource (lib "eagle-import") (part "INDUCTOR0603"))
    )
    (comp (ref "L11")
      (value "330n")
      (footprint "eagle-import:R0603")
      (libsource (lib "eagle-import") (part "INDUCTOR0603"))
    )
    (comp (ref "L12")
      (value "330n")
      (footprint "eagle-import:R0603")
      (libsource (lib "eagle-import") (part "INDUCTOR0603"))
    )
    (comp (ref "L13")
      (value "200n")
      (footprint "eagle-import:R0603")
      (libsource (lib "eagle-import") (part "INDUCTOR0603"))
    )
    (comp (ref "L14")
      (value "200n")
      (footprint "eagle-import:R0603")
      (libsource (lib "eagle-import") (part "INDUCTOR0603"))
    )
    (comp (ref "R17")
      (value "1.91k")
      (footprint "eagle-import:R0603")
      (libsource (lib "eagle-import") (part "R-EU_R0603"))
    )
    (comp (ref "R18")
      (value "49R9")
      (footprint "eagle-import:R0603")
      (libsource (lib "eagle-import") (part "R-EU_R0603"))
    )
    (comp (ref "R19")
      (value "49R9")
      (footprint "eagle-import:R0603")
      (libsource (lib "eagle-import") (part "R-EU_R0603"))
    )
    (comp (ref "R20")
      (value "49R9")
      (footprint "eagle-import:R0603")
      (libsource (lib "eagle-import") (part "R-EU_R0603"))
    )
    (comp (ref "R21")
      (value "49R9")
      (footprint "eagle-import:R0603")
      (libsource (lib "eagle-import") (part "R-EU_R0603"))
    )
    (comp (ref "R22")
      (value "49R9")
      (footprint "eagle-import:R0603")
      (libsource (lib "eagle-import") (part "R-EU_R0603"))
    )
    (comp (ref "R23")
      (value "49R9")
      (footprint "eagle-import:R0603")
      (libsource (lib "eagle-import") (part "R-EU_R0603"))
    )
    (comp (ref "R24")
      (value "49R9")
      (footprint "eagle-import:R0603")
      (libsource (lib "eagle-import") (part "R-EU_R0603"))
    )
    (comp (ref "R25")
      (value "49R9")
      (footprint "eagle-import:R0603")
      (libsource (lib "eagle-import") (part "R-EU_R0603"))
    )
    (comp (ref "R26")
      (value "470")
      (footprint "eagle-import:R0603")
      (libsource (lib "eagle-import") (part "R-EU_R0603"))
    )
    (comp (ref "R28")
      (value "470")
      (footprint "eagle-import:R0603")
      (libsource (lib "eagle-import") (part "R-EU_R0603"))
    )
    (comp (ref "C22")
      (value "1u")
      (footprint "eagle-import:C0603")
      (libsource (lib "eagle-import") (part "C-EUC0603"))
    )
    (comp (ref "C23")
      (value "10n")
      (footprint "eagle-import:C0603")
      (libsource (lib "eagle-import") (part "C-EUC0603"))
    )
    (comp (ref "C24")
      (value "10u")
      (footprint "eagle-import:C1206")
      (libsource (lib "eagle-import") (part "C-EUC1206"))
    )
    (comp (ref "C157")
      (value "100n")
      (footprint "eagle-import:C0603")
      (libsource (lib "eagle-import") (part "C-EUC0603"))
    )
    (comp (ref "C158")
      (value "22u")
      (footprint "eagle-import:C1206")
      (libsource (lib "eagle-import") (part "C-EUC1206"))
    )
    (comp (ref "C159")
      (value "22u")
      (footprint "eagle-import:C1206")
      (libsource (lib "eagle-import") (part "C-EUC1206"))
    )
    (comp (ref "C160")
      (value "22p")
      (footprint "eagle-import:C0603")
      (libsource (lib "eagle-import") (part "C-EUC0603"))
    )
    (comp (ref "C161")
      (value "10n")
      (footprint "eagle-import:C0603")
      (libsource (lib "eagle-import") (part "C-EUC0603"))
    )
    (comp (ref "C162")
      (value "10u")
      (footprint "eagle-import:C1206")
      (libsource (lib "eagle-import") (part "C-EUC1206"))
    )
    (comp (ref "C163")
      (value "100n")
      (footprint "eagle-import:C0603")
      (libsource (lib "eagle-import") (part "C-EUC0603"))
    )
    (comp (ref "C164")
      (value "22u")
      (footprint "eagle-import:C1206")
      (libsource (lib "eagle-import") (part "C-EUC1206"))
    )
    (comp (ref "C165")
      (value "22u")
      (footprint "eagle-import:C1206")
      (libsource (lib "eagle-import") (part "C-EUC1206"))
    )
    (comp (ref "C166")
      (value "100n")
      (footprint "eagle-import:C0603")
      (libsource (lib "eagle-import") (part "C-EUC0603"))
    )
    (comp (ref "C167")
      (value "100n")
      (footprint "eagle-import:C0603")
      (libsource (lib "eagle-import") (part "C-EUC0603"))
    )
    (comp (ref "C168")
      (value "100n")
      (footprint "eagle-import:C0603")
      (libsource (lib "eagle-import") (part "C-EUC0603"))
    )
    (comp (ref "C169")
      (value "100n")
      (footprint "eagle-import:C0603")
      (libsource (lib "eagle-import") (part "C-EUC0603"))
    )
    (comp (ref "C170")
      (value "100n")
      (footprint "eagle-import:C0603")
      (libsource (lib "eagle-import") (part "C-EUC0603"))
    )
    (comp (ref "C171")
      (value "100n")
      (footprint "eagle-import:C0603")
      (libsource (lib "eagle-import") (part "C-EUC0603"))
    )
    (comp (ref "C172")
      (value "100n")
      (footprint "eagle-import:C0603")
      (libsource (lib "eagle-import") (part "C-EUC0603"))
    )
    (comp (ref "C173")
      (value "100n")
      (footprint "eagle-import:C0603")
      (libsource (lib "eagle-import") (part "C-EUC0603"))
    )
    (comp (ref "C174")
      (value "100n")
      (footprint "eagle-import:C0603")
      (libsource (lib "eagle-import") (part "C-EUC0603"))
    )
    (comp (ref "IC11")
      (value "TPS42951")
      (footprint "eagle-import:QFN65P400X400X100-17T270")
      (libsource (lib "eagle-import") (part "TPS42951"))
    )
    (comp (ref "JTAG")
      (value "ML10")
      (footprint "eagle-import:ML10")
      (libsource (lib "eagle-import") (part "ML10"))
    )
    (comp (ref "L70")
      (value "2u2")
      (footprint "eagle-import:SRN5040")
      (libsource (lib "eagle-import") (part "SRN5040"))
    )
    (comp (ref "L71")
      (value "2u2")
      (footprint "eagle-import:SRN5040")
      (libsource (lib "eagle-import") (part "SRN5040"))
    )
    (comp (ref "R5")
      (value "73k2")
      (footprint "eagle-import:R0603")
      (libsource (lib "eagle-import") (part "resistor_R-EU_R0603"))
    )
    (comp (ref "R6")
      (value "22k1")
      (footprint "eagle-import:R0603")
      (libsource (lib "eagle-import") (part "resistor_R-EU_R0603"))
    )
    (comp (ref "R15")
      (value "15k")
      (footprint "eagle-import:R0603")
      (libsource (lib "eagle-import") (part "resistor_R-EU_R0603"))
    )
    (comp (ref "R66")
      (value "11k")
      (footprint "eagle-import:R0603")
      (libsource (lib "eagle-import") (part "resistor_R-EU_R0603"))
    )
    (comp (ref "R67")
      (value "22")
      (footprint "eagle-import:R0603")
      (libsource (lib "eagle-import") (part "resistor_R-EU_R0603"))
    )
    (comp (ref "R68")
      (value "10k")
      (footprint "eagle-import:R0603")
      (libsource (lib "eagle-import") (part "resistor_R-EU_R0603"))
    )
    (comp (ref "R70")
      (value "10k")
      (footprint "eagle-import:R0603")
      (libsource (lib "eagle-import") (part "resistor_R-EU_R0603"))
    )
    (comp (ref "R71")
      (value "10k")
      (footprint "eagle-import:R0603")
      (libsource (lib "eagle-import") (part "resistor_R-EU_R0603"))
    )
    (comp (ref "U4")
      (value "W25Q16BVSN")
      (footprint "eagle-import:SO08")
      (libsource (lib "eagle-import") (part "W25Q16BVSN"))
    )
    (comp (ref "LED1")
      (value "LEDCHIP-LED0603")
      (footprint "eagle-import:CHIP-LED0603")
      (libsource (lib "eagle-import") (part "LEDCHIP-LED0603"))
    )
    (comp (ref "LED2")
      (value "LEDCHIP-LED0603")
      (footprint "eagle-import:CHIP-LED0603")
      (libsource (lib "eagle-import") (part "LEDCHIP-LED0603"))
    )
    (comp (ref "LED3")
      (value "LEDCHIP-LED0603")
      (footprint "eagle-import:CHIP-LED0603")
      (libsource (lib "eagle-import") (part "LEDCHIP-LED0603"))
    )
    (comp (ref "LED4")
      (value "LEDCHIP-LED0603")
      (footprint "eagle-import:CHIP-LED0603")
      (libsource (lib "eagle-import") (part "LEDCHIP-LED0603"))
    )
    (comp (ref "LED5")
      (value "LEDCHIP-LED0603")
      (footprint "eagle-import:CHIP-LED0603")
      (libsource (lib "eagle-import") (part "LEDCHIP-LED0603"))
    )
    (comp (ref "R78")
      (value "220")
      (footprint "eagle-import:R0603")
      (libsource (lib "eagle-import") (part "resistor_R-EU_R0603"))
    )
    (comp (ref "R79")
      (value "220")
      (footprint "eagle-import:R0603")
      (libsource (lib "eagle-import") (part "resistor_R-EU_R0603"))
    )
    (comp (ref "R80")
      (value "220")
      (footprint "eagle-import:R0603")
      (libsource (lib "eagle-import") (part "resistor_R-EU_R0603"))
    )
    (comp (ref "R81")
      (value "220")
      (footprint "eagle-import:R0603")
      (libsource (lib "eagle-import") (part "resistor_R-EU_R0603"))
    )
    (comp (ref "R82")
      (value "220")
      (footprint "eagle-import:R0603")
      (libsource (lib "eagle-import") (part "resistor_R-EU_R0603"))
    )
    (comp (ref "X2")
      (value "FH12-20S-0.5SH")
      (footprint "eagle-import:FH12-20S-0.5SH")
      (fields (field (name "MPN") "FH12-20S-0.5SH(55)"))
      (libsource (lib "eagle-import") (part "FH12-20S-0.5SH"))
    )
    (comp (ref "B1")
      (value "HHM1522B1")
      (footprint "eagle-import:INDCAF65P200X125X95-6")
      (libsource (lib "eagle-import") (part "HHM1522B1"))
    )
    (comp (ref "C101")
      (value "10n")
      (footprint "eagle-import:C0603")
      (libsource (lib "eagle-import") (part "C-EUC0603"))
    )
    (comp (ref "C102")
      (value "10n")
      (footprint "eagle-import:C0603")
      (libsource (lib "eagle-import") (part "C-EUC0603"))
    )
    (comp (ref "C103")
      (value "330p")
      (footprint "eagle-import:C0603")
      (libsource (lib "eagle-import") (part "C-EUC0603"))
    )
    (comp (ref "C104")
      (value "220p")
      (footprint "eagle-import:C0603")
      (libsource (lib "eagle-import") (part "C-EUC0603"))
    )
    (comp (ref "C105")
      (value "10u")
      (footprint "eagle-import:C0603")
      (libsource (lib "eagle-import") (part "C-EUC0603"))
    )
    (comp (ref "C106")
      (value "5p6")
      (footprint "eagle-import:C0603")
      (libsource (lib "eagle-import") (part "C-EUC0603"))
    )
    (comp (ref "C107")
      (value "5p6")
      (footprint "eagle-import:C0603")
      (libsource (lib "eagle-import") (part "C-EUC0603"))
    )
    (comp (ref "C108")
      (value "DNP")
      (footprint "eagle-import:C0603")
      (libsource (lib "eagle-import") (part "C-EUC0603"))
    )
    (comp (ref "C109")
      (value "DNP")
      (footprint "eagle-import:C0603")
      (libsource (lib "eagle-import") (part "C-EUC0603"))
    )
    (comp (ref "C111")
      (value "1u")
      (footprint "eagle-import:C0603")
      (libsource (lib "eagle-import") (part "C-EUC0603"))
    )
    (comp (ref "C112")
      (value "1u")
      (footprint "eagle-import:C0603")
      (libsource (lib "eagle-import") (part "C-EUC0603"))
    )
    (comp (ref "C113")
      (value "100n")
      (footprint "eagle-import:C0603")
      (libsource (lib "eagle-import") (part "C-EUC0603"))
    )
    (comp (ref "C114")
      (value "100n")
      (footprint "eagle-import:C0603")
      (libsource (lib "eagle-import") (part "C-EUC0603"))
    )
    (comp (ref "C115")
      (value "100n")
      (footprint "eagle-import:C0603")
      (libsource (lib "eagle-import") (part "C-EUC0603"))
    )
    (comp (ref "C116")
      (value "1u")
      (footprint "eagle-import:C0603")
      (libsource (lib "eagle-import") (part "C-EUC0603"))
    )
    (comp (ref "C117")
      (value "1u")
      (footprint "eagle-import:C0603")
      (libsource (lib "eagle-import") (part "C-EUC0603"))
    )
    (comp (ref "C118")
      (value "100n")
      (footprint "eagle-import:C0603")
      (libsource (lib "eagle-import") (part "C-EUC0603"))
    )
    (comp (ref "C119")
      (value "10n")
      (footprint "eagle-import:C0603")
      (libsource (lib "eagle-import") (part "C-EUC0603"))
    )
    (comp (ref "C120")
      (value "DNP")
      (footprint "eagle-import:C0603")
      (libsource (lib "eagle-import") (part "C-EUC0603"))
    )
    (comp (ref "C121")
      (value "1u")
      (footprint "eagle-import:C0603")
      (libsource (lib "eagle-import") (part "C-EUC0603"))
    )
    (comp (ref "C122")
      (value "1u")
      (footprint "eagle-import:C0603")
      (libsource (lib "eagle-import") (part "C-EUC0603"))
    )
    (comp (ref "C123")
      (value "1u")
      (footprint "eagle-import:C0603")
      (libsource (lib "eagle-import") (part "C-EUC0603"))
    )
    (comp (ref "C124")
      (value "1u")
      (footprint "eagle-import:C0603")
      (libsource (lib "eagle-import") (part "C-EUC0603"))
    )
    (comp (ref "C125")
      (value "1u")
      (footprint "eagle-import:C0603")
      (libsource (lib "eagle-import") (part "C-EUC0603"))
    )
    (comp (ref "C126")
      (value "22p")
      (footprint "eagle-import:C0603")
      (libsource (lib "eagle-import") (part "C-EUC0603"))
    )
    (comp (ref "C127")
      (value "22p")
      (footprint "eagle-import:C0603")
      (libsource (lib "eagle-import") (part "C-EUC0603"))
    )
    (comp (ref "C128")
      (value "33p")
      (footprint "eagle-import:C0603")
      (libsource (lib "eagle-import") (part "C-EUC0603"))
    )
    (comp (ref "C129")
      (value "33p")
      (footprint "eagle-import:C0603")
      (libsource (lib "eagle-import") (part "C-EUC0603"))
    )
    (comp (ref "C136")
      (value "10n")
      (footprint "eagle-import:C0603")
      (libsource (lib "eagle-import") (part "C-EUC0603"))
    )
    (comp (ref "C137")
      (value "1u")
      (footprint "eagle-import:C0603")
      (libsource (lib "eagle-import") (part "C-EUC0603"))
    )
    (comp (ref "C179")
      (value "100n")
      (footprint "eagle-import:C0603")
      (libsource (lib "eagle-import") (part "C-EUC0603"))
    )
    (comp (ref "IC14")
      (value "LT5560")
      (footprint "eagle-import:SON50P300X300X80-9T165X238")
      (libsource (lib "eagle-import") (part "LT5560"))
    )
    (comp (ref "IC15")
      (value "ADF4360")
      (footprint "eagle-import:QFN50P400X400X80-25T230")
      (libsource (lib "eagle-import") (part "ADF4360"))
    )
    (comp (ref "IC16")
      (value "HMC284")
      (footprint "eagle-import:MSOP08")
      (libsource (lib "eagle-import") (part "HMC284"))
    )
    (comp (ref "IC17")
      (value "HMC284")
      (footprint "eagle-import:MSOP08")
      (libsource (lib "eagle-import") (part "HMC284"))
    )
    (comp (ref "IC18")
      (value "NCP702-3.3")
      (footprint "eagle-import:SOT95P240X110-5")
      (libsource (lib "eagle-import") (part "NCP702"))
    )
    (comp (ref "IC19")
      (value "NCP702-3.3")
      (footprint "eagle-import:SOT95P240X110-5")
      (libsource (lib "eagle-import") (part "NCP702"))
    )
    (comp (ref "IC20")
      (value "LT1395")
      (footprint "eagle-import:SOT23-5")
      (libsource (lib "eagle-import") (part "OPA-SOT23344N"))
    )
    (comp (ref "IC24")
      (value "RFSA2033")
      (footprint "eagle-import:QFN50P300X300X85-17T170")
      (libsource (lib "eagle-import") (part "RFSA2033"))
    )
    (comp (ref "L50")
      (value "100n")
      (footprint "eagle-import:R0603")
      (libsource (lib "eagle-import") (part "INDUCTOR0603"))
    )
    (comp (ref "L51")
      (value "100n")
      (footprint "eagle-import:R0603")
      (libsource (lib "eagle-import") (part "INDUCTOR0603"))
    )
    (comp (ref "L52")
      (value "3n9")
      (footprint "eagle-import:R0603")
      (libsource (lib "eagle-import") (part "INDUCTOR0603"))
    )
    (comp (ref "L53")
      (value "3n9")
      (footprint "eagle-import:R0603")
      (libsource (lib "eagle-import") (part "INDUCTOR0603"))
    )
    (comp (ref "L54")
      (value "3n9")
      (footprint "eagle-import:R0603")
      (libsource (lib "eagle-import") (part "INDUCTOR0603"))
    )
    (comp (ref "L55")
      (value "3n9")
      (footprint "eagle-import:R0603")
      (libsource (lib "eagle-import") (part "INDUCTOR0603"))
    )
    (comp (ref "L56")
      (value "L-EUL2012C")
      (footprint "eagle-import:L2012C")
      (libsource (lib "eagle-import") (part "L-EUL2012C"))
    )
    (comp (ref "L57")
      (value "L-EUL2012C")
      (footprint "eagle-import:L2012C")
      (libsource (lib "eagle-import") (part "L-EUL2012C"))
    )
    (comp (ref "L58")
      (value "30n")
      (footprint "eagle-import:R0603")
      (libsource (lib "eagle-import") (part "INDUCTOR0603"))
    )
    (comp (ref "L59")
      (value "30n")
      (footprint "eagle-import:R0603")
      (libsource (lib "eagle-import") (part "INDUCTOR0603"))
    )
    (comp (ref "L60")
      (value "30n")
      (footprint "eagle-import:R0603")
      (libsource (lib "eagle-import") (part "INDUCTOR0603"))
    )
    (comp (ref "Q1")
      (value "BSS123")
      (footprint "eagle-import:SOT23")
      (libsource (lib "eagle-import") (part "BSS123"))
    )
    (comp (ref "Q2")
      (value "BSS123")
      (footprint "eagle-import:SOT23")
      (libsource (lib "eagle-import") (part "BSS123"))
    )
    (comp (ref "Q6")
      (value "BSS84")
      (footprint "eagle-import:SOT23")
      (libsource (lib "eagle-import") (part "BSS84"))
    )
    (comp (ref "R27")
      (value "15k")
      (footprint "eagle-import:R0603")
      (libsource (lib "eagle-import") (part "resistor_R-EU_R0603"))
    )
    (comp (ref "R29")
      (value "6k8")
      (footprint "eagle-import:R0603")
      (libsource (lib "eagle-import") (part "resistor_R-EU_R0603"))
    )
    (comp (ref "R30")
      (value "4k7")
      (footprint "eagle-import:R0603")
      (libsource (lib "eagle-import") (part "resistor_R-EU_R0603"))
    )
    (comp (ref "R31")
      (value "10k")
      (footprint "eagle-import:R0603")
      (libsource (lib "eagle-import") (part "resistor_R-EU_R0603"))
    )
    (comp (ref "R32")
      (value "10k")
      (footprint "eagle-import:R0603")
      (libsource (lib "eagle-import") (part "resistor_R-EU_R0603"))
    )
    (comp (ref "R33")
      (value "3")
      (footprint "eagle-import:R0603")
      (libsource (lib "eagle-import") (part "resistor_R-EU_R0603"))
    )
    (comp (ref "R34")
      (value "0")
      (footprint "eagle-import:R0603")
      (libsource (lib "eagle-import") (part "resistor_R-EU_R0603"))
    )
    (comp (ref "R35")
      (value "DNP")
      (footprint "eagle-import:R0603")
      (libsource (lib "eagle-import") (part "resistor_R-EU_R0603"))
    )
    (comp (ref "R36")
      (value "DNP")
      (footprint "eagle-import:R0603")
      (libsource (lib "eagle-import") (part "resistor_R-EU_R0603"))
    )
    (comp (ref "R37")
      (value "200")
      (footprint "eagle-import:R0603")
      (libsource (lib "eagle-import") (part "resistor_R-EU_R0603"))
    )
    (comp (ref "R38")
      (value "200")
      (footprint "eagle-import:R0603")
      (libsource (lib "eagle-import") (part "resistor_R-EU_R0603"))
    )
    (comp (ref "R39")
      (value "200")
      (footprint "eagle-import:R0603")
      (libsource (lib "eagle-import") (part "resistor_R-EU_R0603"))
    )
    (comp (ref "R40")
      (value "200")
      (footprint "eagle-import:R0603")
      (libsource (lib "eagle-import") (part "resistor_R-EU_R0603"))
    )
    (comp (ref "R41")
      (value "4k7")
      (footprint "eagle-import:R0603")
      (libsource (lib "eagle-import") (part "resistor_R-EU_R0603"))
    )
    (comp (ref "R42")
      (value "4k7")
      (footprint "eagle-import:R0603")
      (libsource (lib "eagle-import") (part "resistor_R-EU_R0603"))
    )
    (comp (ref "R43")
      (value "49R9")
      (footprint "eagle-import:R0603")
      (libsource (lib "eagle-import") (part "R-EU_R0603"))
    )
    (comp (ref "R64")
      (value "10k")
      (footprint "eagle-import:R0603")
      (libsource (lib "eagle-import") (part "resistor_R-EU_R0603"))
    )
    (comp (ref "R73")
      (value "10k")
      (footprint "eagle-import:R0603")
      (libsource (lib "eagle-import") (part "resistor_R-EU_R0603"))
    )
    (comp (ref "TC1")
      (value "TCXO-NO-VC-CFPT-127")
      (footprint "eagle-import:5.0X3.2-TCXO")
      (libsource (lib "eagle-import") (part "TCXO-NO-VC-CFPT-127"))
    )
    (comp (ref "C59")
      (value "100n")
      (footprint "eagle-import:C0603")
      (libsource (lib "eagle-import") (part "C-EUC0603"))
    )
    (comp (ref "C60")
      (value "100n")
      (footprint "eagle-import:C0603")
      (libsource (lib "eagle-import") (part "C-EUC0603"))
    )
    (comp (ref "C61")
      (value "20p")
      (footprint "eagle-import:C0603")
      (libsource (lib "eagle-import") (part "resistor_C-EUC0603"))
    )
    (comp (ref "C62")
      (value "20p")
      (footprint "eagle-import:C0603")
      (libsource (lib "eagle-import") (part "resistor_C-EUC0603"))
    )
    (comp (ref "C63")
      (value "30p")
      (footprint "eagle-import:C0603")
      (libsource (lib "eagle-import") (part "resistor_C-EUC0603"))
    )
    (comp (ref "C64")
      (value "30p")
      (footprint "eagle-import:C0603")
      (libsource (lib "eagle-import") (part "resistor_C-EUC0603"))
    )
    (comp (ref "C65")
      (value "30p")
      (footprint "eagle-import:C0603")
      (libsource (lib "eagle-import") (part "resistor_C-EUC0603"))
    )
    (comp (ref "C66")
      (value "30p")
      (footprint "eagle-import:C0603")
      (libsource (lib "eagle-import") (part "resistor_C-EUC0603"))
    )
    (comp (ref "C67")
      (value "30p")
      (footprint "eagle-import:C0603")
      (libsource (lib "eagle-import") (part "resistor_C-EUC0603"))
    )
    (comp (ref "C68")
      (value "30p")
      (footprint "eagle-import:C0603")
      (libsource (lib "eagle-import") (part "resistor_C-EUC0603"))
    )
    (comp (ref "C69")
      (value "14p")
      (footprint "eagle-import:C0603")
      (libsource (lib "eagle-import") (part "resistor_C-EUC0603"))
    )
    (comp (ref "C70")
      (value "14p")
      (footprint "eagle-import:C0603")
      (libsource (lib "eagle-import") (part "resistor_C-EUC0603"))
    )
    (comp (ref "C71")
      (value "20p")
      (footprint "eagle-import:C0603")
      (libsource (lib "eagle-import") (part "resistor_C-EUC0603"))
    )
    (comp (ref "C72")
      (value "20p")
      (footprint "eagle-import:C0603")
      (libsource (lib "eagle-import") (part "resistor_C-EUC0603"))
    )
    (comp (ref "C73")
      (value "20p")
      (footprint "eagle-import:C0603")
      (libsource (lib "eagle-import") (part "resistor_C-EUC0603"))
    )
    (comp (ref "C74")
      (value "20p")
      (footprint "eagle-import:C0603")
      (libsource (lib "eagle-import") (part "resistor_C-EUC0603"))
    )
    (comp (ref "C75")
      (value "20p")
      (footprint "eagle-import:C0603")
      (libsource (lib "eagle-import") (part "resistor_C-EUC0603"))
    )
    (comp (ref "C76")
      (value "20p")
      (footprint "eagle-import:C0603")
      (libsource (lib "eagle-import") (part "resistor_C-EUC0603"))
    )
    (comp (ref "C77")
      (value "9p")
      (footprint "eagle-import:C0603")
      (libsource (lib "eagle-import") (part "resistor_C-EUC0603"))
    )
    (comp (ref "C78")
      (value "9p")
      (footprint "eagle-import:C0603")
      (libsource (lib "eagle-import") (part "resistor_C-EUC0603"))
    )
    (comp (ref "C79")
      (value "14p")
      (footprint "eagle-import:C0603")
      (libsource (lib "eagle-import") (part "resistor_C-EUC0603"))
    )
    (comp (ref "C80")
      (value "14p")
      (footprint "eagle-import:C0603")
      (libsource (lib "eagle-import") (part "resistor_C-EUC0603"))
    )
    (comp (ref "C81")
      (value "14p")
      (footprint "eagle-import:C0603")
      (libsource (lib "eagle-import") (part "resistor_C-EUC0603"))
    )
    (comp (ref "C82")
      (value "14p")
      (footprint "eagle-import:C0603")
      (libsource (lib "eagle-import") (part "resistor_C-EUC0603"))
    )
    (comp (ref "C83")
      (value "14p")
      (footprint "eagle-import:C0603")
      (libsource (lib "eagle-import") (part "resistor_C-EUC0603"))
    )
    (comp (ref "C84")
      (value "14p")
      (footprint "eagle-import:C0603")
      (libsource (lib "eagle-import") (part "resistor_C-EUC0603"))
    )
    (comp (ref "C85")
      (value "5p6")
      (footprint "eagle-import:C0603")
      (libsource (lib "eagle-import") (part "resistor_C-EUC0603"))
    )
    (comp (ref "C86")
      (value "5p6")
      (footprint "eagle-import:C0603")
      (libsource (lib "eagle-import") (part "resistor_C-EUC0603"))
    )
    (comp (ref "C87")
      (value "9p")
      (footprint "eagle-import:C0603")
      (libsource (lib "eagle-import") (part "resistor_C-EUC0603"))
    )
    (comp (ref "C88")
      (value "9p")
      (footprint "eagle-import:C0603")
      (libsource (lib "eagle-import") (part "resistor_C-EUC0603"))
    )
    (comp (ref "C89")
      (value "9p")
      (footprint "eagle-import:C0603")
      (libsource (lib "eagle-import") (part "resistor_C-EUC0603"))
    )
    (comp (ref "C90")
      (value "9p")
      (footprint "eagle-import:C0603")
      (libsource (lib "eagle-import") (part "resistor_C-EUC0603"))
    )
    (comp (ref "C91")
      (value "9p")
      (footprint "eagle-import:C0603")
      (libsource (lib "eagle-import") (part "resistor_C-EUC0603"))
    )
    (comp (ref "C92")
      (value "9p")
      (footprint "eagle-import:C0603")
      (libsource (lib "eagle-import") (part "resistor_C-EUC0603"))
    )
    (comp (ref "C93")
      (value "3p9")
      (footprint "eagle-import:C0603")
      (libsource (lib "eagle-import") (part "resistor_C-EUC0603"))
    )
    (comp (ref "C94")
      (value "3p9")
      (footprint "eagle-import:C0603")
      (libsource (lib "eagle-import") (part "resistor_C-EUC0603"))
    )
    (comp (ref "C95")
      (value "5p6")
      (footprint "eagle-import:C0603")
      (libsource (lib "eagle-import") (part "resistor_C-EUC0603"))
    )
    (comp (ref "C96")
      (value "5p6")
      (footprint "eagle-import:C0603")
      (libsource (lib "eagle-import") (part "resistor_C-EUC0603"))
    )
    (comp (ref "C97")
      (value "5p6")
      (footprint "eagle-import:C0603")
      (libsource (lib "eagle-import") (part "resistor_C-EUC0603"))
    )
    (comp (ref "C98")
      (value "5p6")
      (footprint "eagle-import:C0603")
      (libsource (lib "eagle-import") (part "resistor_C-EUC0603"))
    )
    (comp (ref "C99")
      (value "5p6")
      (footprint "eagle-import:C0603")
      (libsource (lib "eagle-import") (part "resistor_C-EUC0603"))
    )
    (comp (ref "C100")
      (value "5p6")
      (footprint "eagle-import:C0603")
      (libsource (lib "eagle-import") (part "resistor_C-EUC0603"))
    )
    (comp (ref "IC31")
      (value "QPC6064")
      (footprint "eagle-import:QFN50P400X400X75-25T270")
      (libsource (lib "eagle-import") (part "QPC6064"))
    )
    (comp (ref "IC32")
      (value "QPC6064")
      (footprint "eagle-import:QFN50P400X400X75-25T270")
      (libsource (lib "eagle-import") (part "QPC6064"))
    )
    (comp (ref "L15")
      (value "30n")
      (footprint "eagle-import:R0603")
      (libsource (lib "eagle-import") (part "INDUCTOR0603"))
    )
    (comp (ref "L16")
      (value "30n")
      (footprint "eagle-import:R0603")
      (libsource (lib "eagle-import") (part "INDUCTOR0603"))
    )
    (comp (ref "L17")
      (value "30n")
      (footprint "eagle-import:R0603")
      (libsource (lib "eagle-import") (part "INDUCTOR0603"))
    )
    (comp (ref "L18")
      (value "30n")
      (footprint "eagle-import:R0603")
      (libsource (lib "eagle-import") (part "INDUCTOR0603"))
    )
    (comp (ref "L19")
      (value "30n")
      (footprint "eagle-import:R0603")
      (libsource (lib "eagle-import") (part "INDUCTOR0603"))
    )
    (comp (ref "L20")
      (value "30n")
      (footprint "eagle-import:R0603")
      (libsource (lib "eagle-import") (part "INDUCTOR0603"))
    )
    (comp (ref "L21")
      (value "30n")
      (footprint "eagle-import:R0603")
      (libsource (lib "eagle-import") (part "INDUCTOR0603"))
    )
    (comp (ref "L22")
      (value "18")
      (footprint "eagle-import:R0603")
      (libsource (lib "eagle-import") (part "INDUCTOR0603"))
    )
    (comp (ref "L23")
      (value "18")
      (footprint "eagle-import:R0603")
      (libsource (lib "eagle-import") (part "INDUCTOR0603"))
    )
    (comp (ref "L24")
      (value "18")
      (footprint "eagle-import:R0603")
      (libsource (lib "eagle-import") (part "INDUCTOR0603"))
    )
    (comp (ref "L25")
      (value "18")
      (footprint "eagle-import:R0603")
      (libsource (lib "eagle-import") (part "INDUCTOR0603"))
    )
    (comp (ref "L26")
      (value "18")
      (footprint "eagle-import:R0603")
      (libsource (lib "eagle-import") (part "INDUCTOR0603"))
    )
    (comp (ref "L27")
      (value "18")
      (footprint "eagle-import:R0603")
      (libsource (lib "eagle-import") (part "INDUCTOR0603"))
    )
    (comp (ref "L28")
      (value "18")
      (footprint "eagle-import:R0603")
      (libsource (lib "eagle-import") (part "INDUCTOR0603"))
    )
    (comp (ref "L29")
      (value "12")
      (footprint "eagle-import:R0603")
      (libsource (lib "eagle-import") (part "INDUCTOR0603"))
    )
    (comp (ref "L30")
      (value "12")
      (footprint "eagle-import:R0603")
      (libsource (lib "eagle-import") (part "INDUCTOR0603"))
    )
    (comp (ref "L31")
      (value "12")
      (footprint "eagle-import:R0603")
      (libsource (lib "eagle-import") (part "INDUCTOR0603"))
    )
    (comp (ref "L32")
      (value "12")
      (footprint "eagle-import:R0603")
      (libsource (lib "eagle-import") (part "INDUCTOR0603"))
    )
    (comp (ref "L33")
      (value "12")
      (footprint "eagle-import:R0603")
      (libsource (lib "eagle-import") (part "INDUCTOR0603"))
    )
    (comp (ref "L34")
      (value "12")
      (footprint "eagle-import:R0603")
      (libsource (lib "eagle-import") (part "INDUCTOR0603"))
    )
    (comp (ref "L35")
      (value "12")
      (footprint "eagle-import:R0603")
      (libsource (lib "eagle-import") (part "INDUCTOR0603"))
    )
    (comp (ref "L36")
      (value "8n2")
      (footprint "eagle-import:R0603")
      (libsource (lib "eagle-import") (part "INDUCTOR0603"))
    )
    (comp (ref "L37")
      (value "8n7")
      (footprint "eagle-import:R0603")
      (libsource (lib "eagle-import") (part "INDUCTOR0603"))
    )
    (comp (ref "L38")
      (value "8n7")
      (footprint "eagle-import:R0603")
      (libsource (lib "eagle-import") (part "INDUCTOR0603"))
    )
    (comp (ref "L39")
      (value "8n7")
      (footprint "eagle-import:R0603")
      (libsource (lib "eagle-import") (part "INDUCTOR0603"))
    )
    (comp (ref "L40")
      (value "8n7")
      (footprint "eagle-import:R0603")
      (libsource (lib "eagle-import") (part "INDUCTOR0603"))
    )
    (comp (ref "L41")
      (value "8n7")
      (footprint "eagle-import:R0603")
      (libsource (lib "eagle-import") (part "INDUCTOR0603"))
    )
    (comp (ref "L42")
      (value "8n2")
      (footprint "eagle-import:R0603")
      (libsource (lib "eagle-import") (part "INDUCTOR0603"))
    )
    (comp (ref "L43")
      (value "5n6")
      (footprint "eagle-import:R0603")
      (libsource (lib "eagle-import") (part "INDUCTOR0603"))
    )
    (comp (ref "L44")
      (value "5n6")
      (footprint "eagle-import:R0603")
      (libsource (lib "eagle-import") (part "INDUCTOR0603"))
    )
    (comp (ref "L45")
      (value "5n6")
      (footprint "eagle-import:R0603")
      (libsource (lib "eagle-import") (part "INDUCTOR0603"))
    )
    (comp (ref "L46")
      (value "5n6")
      (footprint "eagle-import:R0603")
      (libsource (lib "eagle-import") (part "INDUCTOR0603"))
    )
    (comp (ref "L47")
      (value "5n6")
      (footprint "eagle-import:R0603")
      (libsource (lib "eagle-import") (part "INDUCTOR0603"))
    )
    (comp (ref "L48")
      (value "5n6")
      (footprint "eagle-import:R0603")
      (libsource (lib "eagle-import") (part "INDUCTOR0603"))
    )
    (comp (ref "L49")
      (value "5n6")
      (footprint "eagle-import:R0603")
      (libsource (lib "eagle-import") (part "INDUCTOR0603"))
    )
    (comp (ref "L68")
      (value "L-EUL2012C")
      (footprint "eagle-import:L2012C")
      (libsource (lib "eagle-import") (part "L-EUL2012C"))
    )
    (comp (ref "L69")
      (value "L-EUL2012C")
      (footprint "eagle-import:L2012C")
      (libsource (lib "eagle-import") (part "L-EUL2012C"))
    )
  )
  (nets
    (net (code "3") (name "+3V3") (class "Default")
      (node (ref "C158") (pin "1") (pinfunction "1_1") (pintype "passive"))
      (node (ref "C159") (pin "1") (pinfunction "1_1") (pintype "passive"))
      (node (ref "C160") (pin "1") (pinfunction "1_1") (pintype "passive"))
      (node (ref "C166") (pin "1") (pinfunction "1_1") (pintype "passive"))
      (node (ref "C167") (pin "1") (pinfunction "1_1") (pintype "passive"))
      (node (ref "C168") (pin "1") (pinfunction "1_1") (pintype "passive"))
      (node (ref "C169") (pin "1") (pinfunction "1_1") (pintype "passive"))
      (node (ref "C170") (pin "1") (pinfunction "1_1") (pintype "passive"))
      (node (ref "C175") (pin "1") (pinfunction "1_1") (pintype "passive"))
      (node (ref "C176") (pin "1") (pinfunction "1_1") (pintype "passive"))
      (node (ref "C177") (pin "1") (pinfunction "1_1") (pintype "passive"))
      (node (ref "C180") (pin "1") (pinfunction "1_1") (pintype "passive"))
      (node (ref "IC13") (pin "1") (pinfunction "VDD_1") (pintype "power_in"))
      (node (ref "IC13") (pin "24") (pinfunction "VDD_24") (pintype "power_in"))
      (node (ref "IC13") (pin "36") (pinfunction "PF7_36") (pintype "bidirectional"))
      (node (ref "IC13") (pin "48") (pinfunction "VDD_48") (pintype "power_in"))
      (node (ref "IC13") (pin "9") (pinfunction "VDDA_9") (pintype "power_in"))
      (node (ref "JTAG") (pin "4") (pinfunction "4_4") (pintype "passive"))
      (node (ref "L70") (pin "P$2") (pinfunction "2_P$2") (pintype "passive"))
      (node (ref "R5") (pin "1") (pinfunction "1_1") (pintype "passive"))
      (node (ref "R68") (pin "2") (pinfunction "2_2") (pintype "passive"))
      (node (ref "R70") (pin "2") (pinfunction "2_2") (pintype "passive"))
      (node (ref "R71") (pin "2") (pinfunction "2_2") (pintype "passive"))
      (node (ref "R72") (pin "2") (pinfunction "2_2") (pintype "passive"))
      (node (ref "SWD") (pin "1") (pinfunction "1_1") (pintype "passive"))
      (node (ref "U1") (pin "P103") (pinfunction "VCCO_1_P103") (pintype "input"))
      (node (ref "U1") (pin "P122") (pinfunction "VCCO_0_P122") (pintype "input"))
      (node (ref "U1") (pin "P125") (pinfunction "VCCO_0_P125") (pintype "input"))
      (node (ref "U1") (pin "P129") (pinfunction "VCCAUX_P129") (pintype "input"))
      (node (ref "U1") (pin "P135") (pinfunction "VCCO_0_P135") (pintype "input"))
      (node (ref "U1") (pin "P18") (pinfunction "VCCO_3_P18") (pintype "input"))
      (node (ref "U1") (pin "P20") (pinfunction "VCCAUX_P20") (pintype "input"))
      (node (ref "U1") (pin "P31") (pinfunction "VCCO_3_P31") (pintype "input"))
      (node (ref "U1") (pin "P36") (pinfunction "VCCAUX_P36") (pintype "input"))
      (node (ref "U1") (pin "P4") (pinfunction "VCCO_3_P4") (pintype "input"))
      (node (ref "U1") (pin "P42") (pinfunction "VCCO_2_P42") (pintype "input"))
      (node (ref "U1") (pin "P53") (pinfunction "VCCAUX_P53") (pintype "input"))
      (node (ref "U1") (pin "P63") (pinfunction "VCCO_2_P63") (pintype "input"))
      (node (ref "U1") (pin "P69") (pinfunction "IO_L1N_M0_CMPMISO_2_P69") (pintype "bidirectional"))
      (node (ref "U1") (pin "P76") (pinfunction "VCCO_1_P76") (pintype "input"))
      (node (ref "U1") (pin "P86") (pinfunction "VCCO_1_P86") (pintype "input"))
      (node (ref "U1") (pin "P90") (pinfunction "VCCAUX_P90") (pintype "input"))
      (node (ref "U4") (pin "3") (pinfunction "~{WP}_3") (pintype "input"))
      (node (ref "U4") (pin "7") (pinfunction "~{HOLD}_7") (pintype "input"))
      (node (ref "U4") (pin "8") (pinfunction "VCC_8") (pintype "power_in"))
      (node (ref "X2") (pin "1") (pinfunction "1_1") (pintype "passive"))
      (node (ref "X2") (pin "18") (pinfunction "1_18") (pintype "passive"))
      (node (ref "X2") (pin "5") (pinfunction "1_5") (pintype "passive"))
    )
    (net (code "4") (name "+5V") (class "Default")
      (node (ref "C10") (pin "1") (pinfunction "1_1") (pintype "passive"))
      (node (ref "C112") (pin "1") (pinfunction "1_1") (pintype "passive"))
      (node (ref "C117") (pin "1") (pinfunction "1_1") (pintype "passive"))
      (node (ref "C12") (pin "1") (pinfunction "1_1") (pintype "passive"))
      (node (ref "C156") (pin "1") (pinfunction "1_1") (pintype "passive"))
      (node (ref "C162") (pin "1") (pinfunction "1_1") (pintype "passive"))
      (node (ref "C24") (pin "1") (pinfunction "1_1") (pintype "passive"))
      (node (ref "C29") (pin "1") (pinfunction "1_1") (pintype "passive"))
      (node (ref "C32") (pin "1") (pinfunction "1_1") (pintype "passive"))
      (node (ref "C34") (pin "1") (pinfunction "1_1") (pintype "passive"))
      (node (ref "C36") (pin "1") (pinfunction "1_1") (pintype "passive"))
      (node (ref "C38") (pin "1") (pinfunction "1_1") (pintype "passive"))
      (node (ref "C9") (pin "1") (pinfunction "1_1") (pintype "passive"))
      (node (ref "IC10") (pin "1") (pinfunction "VIN_1") (pintype "power_in"))
      (node (ref "IC10") (pin "3") (pinfunction "EN_3") (pintype "input"))
      (node (ref "IC11") (pin "14") (pinfunction "EN_14") (pintype "bidirectional"))
      (node (ref "IC11") (pin "2") (pinfunction "VIN_2") (pintype "bidirectional"))
      (node (ref "IC11") (pin "3") (pinfunction "VIN_3") (pintype "bidirectional"))
      (node (ref "IC11") (pin "7") (pinfunction "EN_7") (pintype "bidirectional"))
      (node (ref "IC18") (pin "1") (pinfunction "VIN_1") (pintype "power_in"))
      (node (ref "IC18") (pin "3") (pinfunction "EN_3") (pintype "input"))
      (node (ref "IC19") (pin "1") (pinfunction "VIN_1") (pintype "power_in"))
      (node (ref "IC19") (pin "3") (pinfunction "EN_3") (pintype "input"))
      (node (ref "IC29") (pin "1") (pinfunction "VIN_1") (pintype "power_in"))
      (node (ref "IC29") (pin "3") (pinfunction "EN_3") (pintype "input"))
      (node (ref "IC3") (pin "1") (pinfunction "VIN_1") (pintype "power_in"))
      (node (ref "IC4") (pin "1") (pinfunction "VIN_1") (pintype "power_in"))
      (node (ref "IC4") (pin "3") (pinfunction "EN_3") (pintype "input"))
      (node (ref "IC5") (pin "1") (pinfunction "VIN_1") (pintype "power_in"))
      (node (ref "IC5") (pin "3") (pinfunction "EN_3") (pintype "input"))
      (node (ref "IC7") (pin "1") (pinfunction "VIN_1") (pintype "power_in"))
      (node (ref "IC7") (pin "3") (pinfunction "EN_3") (pintype "input"))
      (node (ref "IC8") (pin "1") (pinfunction "VIN_1") (pintype "power_in"))
      (node (ref "IC8") (pin "3") (pinfunction "EN_3") (pintype "input"))
      (node (ref "IC9") (pin "1") (pinfunction "VIN_1") (pintype "power_in"))
      (node (ref "IC9") (pin "3") (pinfunction "EN_3") (pintype "input"))
      (node (ref "L1") (pin "1") (pinfunction "1_1") (pintype "passive"))
      (node (ref "L2") (pin "1") (pinfunction "1_1") (pintype "passive"))
      (node (ref "L56") (pin "2") (pinfunction "2_2") (pintype "passive"))
      (node (ref "L57") (pin "2") (pinfunction "2_2") (pintype "passive"))
      (node (ref "L67") (pin "2") (pinfunction "2_2") (pintype "passive"))
      (node (ref "L68") (pin "1") (pinfunction "1_1") (pintype "passive"))
      (node (ref "L69") (pin "1") (pinfunction "1_1") (pintype "passive"))
      (node (ref "R31") (pin "1") (pinfunction "1_1") (pintype "passive"))
      (node (ref "R32") (pin "1") (pinfunction "1_1") (pintype "passive"))
      (node (ref "R41") (pin "2") (pinfunction "2_2") (pintype "passive"))
      (node (ref "R44") (pin "1") (pinfunction "1_1") (pintype "passive"))
      (node (ref "R45") (pin "1") (pinfunction "1_1") (pintype "passive"))
      (node (ref "R46") (pin "1") (pinfunction "1_1") (pintype "passive"))
      (node (ref "R47") (pin "2") (pinfunction "2_2") (pintype "passive"))
      (node (ref "R48") (pin "2") (pinfunction "2_2") (pintype "passive"))
      (node (ref "R54") (pin "1") (pinfunction "1_1") (pintype "passive"))
      (node (ref "R55") (pin "1") (pinfunction "1_1") (pintype "passive"))
      (node (ref "R56") (pin "1") (pinfunction "1_1") (pintype "passive"))
      (node (ref "SV2") (pin "1") (pinfunction "1_1") (pintype "passive"))
      (node (ref "SV2") (pin "3") (pinfunction "3_3") (pintype "passive"))
    )
    (net (code "7") (name "10MHZ_REF") (class "Default")
      (node (ref "C115") (pin "2") (pinfunction "2_2") (pintype "passive"))
      (node (ref "C184") (pin "1") (pinfunction "1_1") (pintype "passive"))
      (node (ref "C19") (pin "1") (pinfunction "1_1") (pintype "passive"))
      (node (ref "R76") (pin "1") (pinfunction "1_1") (pintype "passive"))
      (node (ref "TC1") (pin "3") (pinfunction "OUT_3") (pintype "output"))
    )
    (net (code "8") (name "15DB1") (class "Default")
      (node (ref "IC13") (pin "6") (pinfunction "OSC_OUT_6") (pintype "bidirectional"))
      (node (ref "IC21") (pin "5") (pinfunction "V2_5") (pintype "bidirectional"))
      (node (ref "Q3") (pin "1") (pinfunction "G_1") (pintype "passive"))
    )
    (net (code "9") (name "15DB2") (class "Default")
      (node (ref "IC13") (pin "5") (pinfunction "OSC_IN_5") (pintype "bidirectional"))
      (node (ref "IC22") (pin "5") (pinfunction "V2_5") (pintype "bidirectional"))
      (node (ref "Q4") (pin "1") (pinfunction "G_1") (pintype "passive"))
    )
    (net (code "10") (name "15DB3") (class "Default")
      (node (ref "IC13") (pin "4") (pinfunction "PC15_4") (pintype "bidirectional"))
      (node (ref "IC23") (pin "5") (pinfunction "V2_5") (pintype "bidirectional"))
      (node (ref "Q5") (pin "1") (pinfunction "G_1") (pintype "passive"))
    )
    (net (code "11") (name "ADF_CE") (class "Default")
      (node (ref "IC13") (pin "15") (pinfunction "PA5_15") (pintype "bidirectional"))
      (node (ref "IC15") (pin "23") (pinfunction "CE_23") (pintype "bidirectional"))
    )
    (net (code "12") (name "ADF_LE") (class "Default")
      (node (ref "IC13") (pin "38") (pinfunction "PA15_38") (pintype "bidirectional"))
      (node (ref "IC15") (pin "19") (pinfunction "LE_19") (pintype "bidirectional"))
    )
    (net (code "13") (name "ADF_MUX") (class "Default")
      (node (ref "IC13") (pin "14") (pinfunction "PA4_14") (pintype "bidirectional"))
      (node (ref "IC15") (pin "20") (pinfunction "MUXOUT_20") (pintype "bidirectional"))
    )
    (net (code "14") (name "CLKN") (class "Default")
      (node (ref "C57") (pin "2") (pinfunction "2_2") (pintype "passive"))
      (node (ref "U1") (pin "P143") (pinfunction "IO_L1N_VREF_0_P143") (pintype "bidirectional"))
    )
    (net (code "15") (name "CLKP") (class "Default")
      (node (ref "C58") (pin "2") (pinfunction "2_2") (pintype "passive"))
      (node (ref "R69") (pin "2") (pinfunction "2_2") (pintype "passive"))
      (node (ref "U1") (pin "P144") (pinfunction "IO_L1P_HSWAPEN_0_P144") (pintype "bidirectional"))
    )
    (net (code "16") (name "DAC_DIG3.3") (class "Default")
      (node (ref "C33") (pin "1") (pinfunction "1_1") (pintype "passive"))
      (node (ref "C39") (pin "1") (pinfunction "1_1") (pintype "passive"))
      (node (ref "C56") (pin "1") (pinfunction "1_1") (pintype "passive"))
      (node (ref "IC12") (pin "1") (pinfunction "VDD_1") (pintype "bidirectional"))
      (node (ref "IC6") (pin "11") (pinfunction "DVDD3.3_11") (pintype "bidirectional"))
      (node (ref "IC8") (pin "5") (pinfunction "VOUT_5") (pintype "power_in"))
    )
    (net (code "17") (name "DBM_CS") (class "Default")
      (node (ref "IC13") (pin "42") (pinfunction "PB6_42") (pintype "bidirectional"))
      (node (ref "IC28") (pin "2") (pinfunction "CS_2") (pintype "bidirectional"))
    )
    (net (code "18") (name "DET_SCI1") (class "Default")
      (node (ref "IC13") (pin "45") (pinfunction "PB8_45") (pintype "bidirectional"))
      (node (ref "IC27") (pin "17") (pinfunction "SCI1_17") (pintype "bidirectional"))
      (node (ref "R58") (pin "1") (pinfunction "1_1") (pintype "passive"))
    )
    (net (code "19") (name "DET_SCI2") (class "Default")
      (node (ref "IC13") (pin "46") (pinfunction "PB9_46") (pintype "bidirectional"))
      (node (ref "IC27") (pin "18") (pinfunction "SCI2_18") (pintype "bidirectional"))
      (node (ref "R57") (pin "1") (pinfunction "1_1") (pintype "passive"))
    )
    (net (code "20") (name "DET_SCI3") (class "Default")
      (node (ref "IC13") (pin "43") (pinfunction "PB7_43") (pintype "bidirectional"))
      (node (ref "IC27") (pin "19") (pinfunction "SCI3_19") (pintype "bidirectional"))
      (node (ref "R55") (pin "2") (pinfunction "2_2") (pintype "passive"))
    )
    (net (code "21") (name "DET_SCI4") (class "Default")
      (node (ref "IC13") (pin "3") (pinfunction "PC14_3") (pintype "bidirectional"))
      (node (ref "IC27") (pin "20") (pinfunction "SCI4_20") (pintype "bidirectional"))
      (node (ref "R56") (pin "2") (pinfunction "2_2") (pintype "passive"))
    )
    (net (code "22") (name "DET_{slash}EN") (class "Default")
      (node (ref "IC13") (pin "2") (pinfunction "PC13_2") (pintype "bidirectional"))
      (node (ref "IC27") (pin "7") (pinfunction "ENX_7") (pintype "bidirectional"))
      (node (ref "R54") (pin "2") (pinfunction "2_2") (pintype "passive"))
    )
    (net (code "23") (name "DORI") (class "Default")
      (node (ref "IC6") (pin "41") (pinfunction "/DORI_41") (pintype "bidirectional"))
      (node (ref "U1") (pin "P9") (pinfunction "IO_L50N_3_P9") (pintype "bidirectional"))
    )
    (net (code "24") (name "EN_DIRECT") (class "Default")
      (node (ref "IC13") (pin "12") (pinfunction "PA2_12") (pintype "bidirectional"))
      (node (ref "Q1") (pin "1") (pinfunction "G_1") (pintype "passive"))
    )
    (net (code "25") (name "EN_INTREF") (class "Default")
      (node (ref "IC13") (pin "13") (pinfunction "PA3_13") (pintype "bidirectional"))
      (node (ref "Q6") (pin "1") (pinfunction "G_1") (pintype "passive"))
      (node (ref "R73") (pin "1") (pinfunction "1_1") (pintype "passive"))
    )
    (net (code "26") (name "ETOUT") (class "Default")
      (node (ref "IC27") (pin "6") (pinfunction "ETOUT_6") (pintype "bidirectional"))
      (node (ref "R74") (pin "1") (pinfunction "1_1") (pintype "passive"))
    )
    (net (code "27") (name "FILTERED") (class "Default")
      (node (ref "C136") (pin "2") (pinfunction "2_2") (pintype "passive"))
      (node (ref "IC32") (pin "22") (pinfunction "RFC_22") (pintype "bidirectional"))
    )
    (net (code "28") (name "FPGA_CS") (class "Default")
      (node (ref "IC13") (pin "16") (pinfunction "PA6_16") (pintype "bidirectional"))
      (node (ref "U1") (pin "P35") (pinfunction "IO_L1P_3_P35") (pintype "bidirectional"))
    )
    (net (code "29") (name "FULLBAND") (class "Default")
      (node (ref "C130") (pin "2") (pinfunction "2_2") (pintype "passive"))
      (node (ref "IC17") (pin "3") (pinfunction "RFC_3") (pintype "bidirectional"))
    )
    (net (code "30") (name "GAIN_CTRL") (class "Default")
      (node (ref "C154") (pin "1") (pinfunction "1_1") (pintype "passive"))
      (node (ref "IC24") (pin "14") (pinfunction "VC_14") (pintype "bidirectional"))
      (node (ref "R63") (pin "2") (pinfunction "2_2") (pintype "passive"))
    )
    (net (code "31") (name "GND") (class "Default")
      (node (ref "B1") (pin "5") (pinfunction "GND_5") (pintype "bidirectional"))
      (node (ref "C1") (pin "2") (pinfunction "2_2") (pintype "passive"))
      (node (ref "C10") (pin "2") (pinfunction "2_2") (pintype "passive"))
      (node (ref "C100") (pin "2") (pinfunction "2_2") (pintype "passive"))
      (node (ref "C101") (pin "2") (pinfunction "2_2") (pintype "passive"))
      (node (ref "C102") (pin "2") (pinfunction "2_2") (pintype "passive"))
      (node (ref "C103") (pin "2") (pinfunction "2_2") (pintype "passive"))
      (node (ref "C104") (pin "2") (pinfunction "2_2") (pintype "passive"))
      (node (ref "C11") (pin "2") (pinfunction "2_2") (pintype "passive"))
      (node (ref "C110") (pin "2") (pinfunction "2_2") (pintype "passive"))
      (node (ref "C111") (pin "2") (pinfunction "2_2") (pintype "passive"))
      (node (ref "C112") (pin "2") (pinfunction "2_2") (pintype "passive"))
      (node (ref "C113") (pin "2") (pinfunction "2_2") (pintype "passive"))
      (node (ref "C114") (pin "2") (pinfunction "2_2") (pintype "passive"))
      (node (ref "C116") (pin "2") (pinfunction "2_2") (pintype "passive"))
      (node (ref "C117") (pin "2") (pinfunction "2_2") (pintype "passive"))
      (node (ref "C118") (pin "2") (pinfunction "2_2") (pintype "passive"))
      (node (ref "C12") (pin "2") (pinfunction "2_2") (pintype "passive"))
      (node (ref "C121") (pin "2") (pinfunction "2_2") (pintype "passive"))
      (node (ref "C124") (pin "1") (pinfunction "1_1") (pintype "passive"))
      (node (ref "C126") (pin "1") (pinfunction "1_1") (pintype "passive"))
      (node (ref "C127") (pin "1") (pinfunction "1_1") (pintype "passive"))
      (node (ref "C128") (pin "1") (pinfunction "1_1") (pintype "passive"))
      (node (ref "C129") (pin "1") (pinfunction "1_1") (pintype "passive"))
      (node (ref "C13") (pin "2") (pinfunction "2_2") (pintype "passive"))
      (node (ref "C131") (pin "2") (pinfunction "2_2") (pintype "passive"))
      (node (ref "C133") (pin "2") (pinfunction "2_2") (pintype "passive"))
      (node (ref "C135") (pin "2") (pinfunction "2_2") (pintype "passive"))
      (node (ref "C137") (pin "2") (pinfunction "2_2") (pintype "passive"))
      (node (ref "C14") (pin "2") (pinfunction "2_2") (pintype "passive"))
      (node (ref "C140") (pin "2") (pinfunction "2_2") (pintype "passive"))
      (node (ref "C141") (pin "2") (pinfunction "2_2") (pintype "passive"))
      (node (ref "C142") (pin "2") (pinfunction "2_2") (pintype "passive"))
      (node (ref "C145") (pin "2") (pinfunction "2_2") (pintype "passive"))
      (node (ref "C146") (pin "2") (pinfunction "2_2") (pintype "passive"))
      (node (ref "C147") (pin "2") (pinfunction "2_2") (pintype "passive"))
      (node (ref "C148") (pin "2") (pinfunction "2_2") (pintype "passive"))
      (node (ref "C15") (pin "2") (pinfunction "2_2") (pintype "passive"))
      (node (ref "C152") (pin "2") (pinfunction "2_2") (pintype "passive"))
      (node (ref "C153") (pin "2") (pinfunction "2_2") (pintype "passive"))
      (node (ref "C154") (pin "2") (pinfunction "2_2") (pintype "passive"))
      (node (ref "C155") (pin "2") (pinfunction "2_2") (pintype "passive"))
      (node (ref "C156") (pin "2") (pinfunction "2_2") (pintype "passive"))
      (node (ref "C158") (pin "2") (pinfunction "2_2") (pintype "passive"))
      (node (ref "C159") (pin "2") (pinfunction "2_2") (pintype "passive"))
      (node (ref "C16") (pin "2") (pinfunction "2_2") (pintype "passive"))
      (node (ref "C161") (pin "2") (pinfunction "2_2") (pintype "passive"))
      (node (ref "C162") (pin "2") (pinfunction "2_2") (pintype "passive"))
      (node (ref "C164") (pin "2") (pinfunction "2_2") (pintype "passive"))
      (node (ref "C165") (pin "2") (pinfunction "2_2") (pintype "passive"))
      (node (ref "C166") (pin "2") (pinfunction "2_2") (pintype "passive"))
      (node (ref "C167") (pin "2") (pinfunction "2_2") (pintype "passive"))
      (node (ref "C168") (pin "2") (pinfunction "2_2") (pintype "passive"))
      (node (ref "C169") (pin "2") (pinfunction "2_2") (pintype "passive"))
      (node (ref "C17") (pin "2") (pinfunction "2_2") (pintype "passive"))
      (node (ref "C170") (pin "2") (pinfunction "2_2") (pintype "passive"))
      (node (ref "C171") (pin "2") (pinfunction "2_2") (pintype "passive"))
      (node (ref "C172") (pin "2") (pinfunction "2_2") (pintype "passive"))
      (node (ref "C173") (pin "2") (pinfunction "2_2") (pintype "passive"))
      (node (ref "C174") (pin "2") (pinfunction "2_2") (pintype "passive"))
      (node (ref "C175") (pin "2") (pinfunction "2_2") (pintype "passive"))
      (node (ref "C176") (pin "2") (pinfunction "2_2") (pintype "passive"))
      (node (ref "C177") (pin "2") (pinfunction "2_2") (pintype "passive"))
      (node (ref "C178") (pin "2") (pinfunction "2_2") (pintype "passive"))
      (node (ref "C179") (pin "2") (pinfunction "2_2") (pintype "passive"))
      (node (ref "C18") (pin "2") (pinfunction "2_2") (pintype "passive"))
      (node (ref "C180") (pin "2") (pinfunction "2_2") (pintype "passive"))
      (node (ref "C181") (pin "2") (pinfunction "2_2") (pintype "passive"))
      (node (ref "C182") (pin "2") (pinfunction "2_2") (pintype "passive"))
      (node (ref "C183") (pin "2") (pinfunction "2_2") (pintype "passive"))
      (node (ref "C2") (pin "2") (pinfunction "2_2") (pintype "passive"))
      (node (ref "C22") (pin "2") (pinfunction "2_2") (pintype "passive"))
      (node (ref "C23") (pin "2") (pinfunction "2_2") (pintype "passive"))
      (node (ref "C24") (pin "2") (pinfunction "2_2") (pintype "passive"))
      (node (ref "C25") (pin "1") (pinfunction "1_1") (pintype "passive"))
      (node (ref "C26") (pin "2") (pinfunction "2_2") (pintype "passive"))
      (node (ref "C27") (pin "2") (pinfunction "2_2") (pintype "passive"))
      (node (ref "C28") (pin "1") (pinfunction "1_1") (pintype "passive"))
      (node (ref "C29") (pin "2") (pinfunction "2_2") (pintype "passive"))
      (node (ref "C3") (pin "2") (pinfunction "2_2") (pintype "passive"))
      (node (ref "C31") (pin "2") (pinfunction "2_2") (pintype "passive"))
      (node (ref "C32") (pin "2") (pinfunction "2_2") (pintype "passive"))
      (node (ref "C33") (pin "2") (pinfunction "2_2") (pintype "passive"))
      (node (ref "C34") (pin "2") (pinfunction "2_2") (pintype "passive"))
      (node (ref "C35") (pin "2") (pinfunction "2_2") (pintype "passive"))
      (node (ref "C36") (pin "2") (pinfunction "2_2") (pintype "passive"))
      (node (ref "C37") (pin "2") (pinfunction "2_2") (pintype "passive"))
      (node (ref "C38") (pin "2") (pinfunction "2_2") (pintype "passive"))
      (node (ref "C39") (pin "2") (pinfunction "2_2") (pintype "passive"))
      (node (ref "C4") (pin "2") (pinfunction "2_2") (pintype "passive"))
      (node (ref "C40") (pin "2") (pinfunction "2_2") (pintype "passive"))
      (node (ref "C41") (pin "2") (pinfunction "2_2") (pintype "passive"))
      (node (ref "C42") (pin "2") (pinfunction "2_2") (pintype "passive"))
      (node (ref "C43") (pin "2") (pinfunction "2_2") (pintype "passive"))
      (node (ref "C44") (pin "2") (pinfunction "2_2") (pintype "passive"))
      (node (ref "C45") (pin "2") (pinfunction "2_2") (pintype "passive"))
      (node (ref "C5") (pin "1") (pinfunction "1_1") (pintype "passive"))
      (node (ref "C54") (pin "2") (pinfunction "2_2") (pintype "passive"))
      (node (ref "C55") (pin "2") (pinfunction "2_2") (pintype "passive"))
      (node (ref "C56") (pin "2") (pinfunction "2_2") (pintype "passive"))
      (node (ref "C59") (pin "2") (pinfunction "2_2") (pintype "passive"))
      (node (ref "C60") (pin "2") (pinfunction "2_2") (pintype "passive"))
      (node (ref "C61") (pin "2") (pinfunction "2_2") (pintype "passive"))
      (node (ref "C62") (pin "2") (pinfunction "2_2") (pintype "passive"))
      (node (ref "C63") (pin "2") (pinfunction "2_2") (pintype "passive"))
      (node (ref "C64") (pin "2") (pinfunction "2_2") (pintype "passive"))
      (node (ref "C65") (pin "2") (pinfunction "2_2") (pintype "passive"))
      (node (ref "C66") (pin "2") (pinfunction "2_2") (pintype "passive"))
      (node (ref "C67") (pin "2") (pinfunction "2_2") (pintype "passive"))
      (node (ref "C68") (pin "2") (pinfunction "2_2") (pintype "passive"))
      (node (ref "C69") (pin "2") (pinfunction "2_2") (pintype "passive"))
      (node (ref "C7") (pin "2") (pinfunction "2_2") (pintype "passive"))
      (node (ref "C70") (pin "2") (pinfunction "2_2") (pintype "passive"))
      (node (ref "C71") (pin "2") (pinfunction "2_2") (pintype "passive"))
      (node (ref "C72") (pin "2") (pinfunction "2_2") (pintype "passive"))
      (node (ref "C73") (pin "2") (pinfunction "2_2") (pintype "passive"))
      (node (ref "C74") (pin "2") (pinfunction "2_2") (pintype "passive"))
      (node (ref "C75") (pin "2") (pinfunction "2_2") (pintype "passive"))
      (node (ref "C76") (pin "2") (pinfunction "2_2") (pintype "passive"))
      (node (ref "C77") (pin "2") (pinfunction "2_2") (pintype "passive"))
      (node (ref "C78") (pin "2") (pinfunction "2_2") (pintype "passive"))
      (node (ref "C79") (pin "2") (pinfunction "2_2") (pintype "passive"))
      (node (ref "C8") (pin "2") (pinfunction "2_2") (pintype "passive"))
      (node (ref "C80") (pin "2") (pinfunction "2_2") (pintype "passive"))
      (node (ref "C81") (pin "2") (pinfunction "2_2") (pintype "passive"))
      (node (ref "C82") (pin "2") (pinfunction "2_2") (pintype "passive"))
      (node (ref "C83") (pin "2") (pinfunction "2_2") (pintype "passive"))
      (node (ref "C84") (pin "2") (pinfunction "2_2") (pintype "passive"))
      (node (ref "C85") (pin "2") (pinfunction "2_2") (pintype "passive"))
      (node (ref "C86") (pin "2") (pinfunction "2_2") (pintype "passive"))
      (node (ref "C87") (pin "2") (pinfunction "2_2") (pintype "passive"))
      (node (ref "C88") (pin "2") (pinfunction "2_2") (pintype "passive"))
      (node (ref "C89") (pin "2") (pinfunction "2_2") (pintype "passive"))
      (node (ref "C9") (pin "2") (pinfunction "2_2") (pintype "passive"))
      (node (ref "C90") (pin "2") (pinfunction "2_2") (pintype "passive"))
      (node (ref "C91") (pin "2") (pinfunction "2_2") (pintype "passive"))
      (node (ref "C92") (pin "2") (pinfunction "2_2") (pintype "passive"))
      (node (ref "C93") (pin "2") (pinfunction "2_2") (pintype "passive"))
      (node (ref "C94") (pin "2") (pinfunction "2_2") (pintype "passive"))
      (node (ref "C95") (pin "2") (pinfunction "2_2") (pintype "passive"))
      (node (ref "C96") (pin "2") (pinfunction "2_2") (pintype "passive"))
      (node (ref "C97") (pin "2") (pinfunction "2_2") (pintype "passive"))
      (node (ref "C98") (pin "2") (pinfunction "2_2") (pintype "passive"))
      (node (ref "C99") (pin "2") (pinfunction "2_2") (pintype "passive"))
      (node (ref "IC1") (pin "11") (pinfunction "GND_11") (pintype "bidirectional"))
      (node (ref "IC1") (pin "12") (pinfunction "GND_12") (pintype "bidirectional"))
      (node (ref "IC1") (pin "14") (pinfunction "GND_14") (pintype "bidirectional"))
      (node (ref "IC1") (pin "17") (pinfunction "GND_17") (pintype "bidirectional"))
      (node (ref "IC1") (pin "19") (pinfunction "GND_19") (pintype "bidirectional"))
      (node (ref "IC1") (pin "2") (pinfunction "GND_2") (pintype "bidirectional"))
      (node (ref "IC1") (pin "20") (pinfunction "GND_20") (pintype "bidirectional"))
      (node (ref "IC1") (pin "23") (pinfunction "GND_23") (pintype "bidirectional"))
      (node (ref "IC1") (pin "25") (pinfunction "GND_25") (pintype "bidirectional"))
      (node (ref "IC1") (pin "5") (pinfunction "GND_5") (pintype "bidirectional"))
      (node (ref "IC1") (pin "8") (pinfunction "GND_8") (pintype "bidirectional"))
      (node (ref "IC10") (pin "2") (pinfunction "GND_2") (pintype "power_in"))
      (node (ref "IC11") (pin "10") (pinfunction "GND_10") (pintype "bidirectional"))
      (node (ref "IC11") (pin "15") (pinfunction "PGND_15") (pintype "bidirectional"))
      (node (ref "IC11") (pin "17") (pinfunction "GND_17") (pintype "bidirectional"))
      (node (ref "IC11") (pin "6") (pinfunction "PGND_6") (pintype "bidirectional"))
      (node (ref "IC12") (pin "5") (pinfunction "LDAC_5") (pintype "bidirectional"))
      (node (ref "IC12") (pin "7") (pinfunction "VSS_7") (pintype "bidirectional"))
      (node (ref "IC13") (pin "23") (pinfunction "VSS_23") (pintype "power_in"))
      (node (ref "IC13") (pin "35") (pinfunction "PF6_35") (pintype "bidirectional"))
      (node (ref "IC13") (pin "44") (pinfunction "BOOT0_44") (pintype "input"))
      (node (ref "IC13") (pin "47") (pinfunction "VSS_47") (pintype "power_in"))
      (node (ref "IC13") (pin "8") (pinfunction "VSSA_8") (pintype "power_in"))
      (node (ref "IC14") (pin "9") (pinfunction "GND_9") (pintype "bidirectional"))
      (node (ref "IC15") (pin "1") (pinfunction "CPGND_1") (pintype "bidirectional"))
      (node (ref "IC15") (pin "10") (pinfunction "AGND_10") (pintype "bidirectional"))
      (node (ref "IC15") (pin "11") (pinfunction "AGND_11") (pintype "bidirectional"))
      (node (ref "IC15") (pin "15") (pinfunction "DGND_15") (pintype "bidirectional"))
      (node (ref "IC15") (pin "22") (pinfunction "AGND_22") (pintype "bidirectional"))
      (node (ref "IC15") (pin "25") (pinfunction "AGND_25") (pintype "bidirectional"))
      (node (ref "IC15") (pin "3") (pinfunction "AGND_3") (pintype "bidirectional"))
      (node (ref "IC15") (pin "8") (pinfunction "AGND_8") (pintype "bidirectional"))
      (node (ref "IC15") (pin "9") (pinfunction "AGND_9") (pintype "bidirectional"))
      (node (ref "IC16") (pin "6") (pinfunction "GND_6") (pintype "bidirectional"))
      (node (ref "IC16") (pin "7") (pinfunction "GND_7") (pintype "bidirectional"))
      (node (ref "IC16") (pin "9") (pinfunction "GND_9") (pintype "bidirectional"))
      (node (ref "IC17") (pin "6") (pinfunction "GND_6") (pintype "bidirectional"))
      (node (ref "IC17") (pin "7") (pinfunction "GND_7") (pintype "bidirectional"))
      (node (ref "IC17") (pin "9") (pinfunction "GND_9") (pintype "bidirectional"))
      (node (ref "IC18") (pin "2") (pinfunction "GND_2") (pintype "power_in"))
      (node (ref "IC19") (pin "2") (pinfunction "GND_2") (pintype "power_in"))
      (node (ref "IC2") (pin "11") (pinfunction "GND_RF_11") (pintype "bidirectional"))
      (node (ref "IC2") (pin "18") (pinfunction "GND_VCO_18") (pintype "bidirectional"))
      (node (ref "IC2") (pin "21") (pinfunction "GND_TUNE_21") (pintype "bidirectional"))
      (node (ref "IC2") (pin "27") (pinfunction "GND_DIG_27") (pintype "bidirectional"))
      (node (ref "IC2") (pin "31") (pinfunction "GND_SD_31") (pintype "bidirectional"))
      (node (ref "IC2") (pin "33") (pinfunction "EP_33") (pintype "bidirectional"))
      (node (ref "IC2") (pin "8") (pinfunction "GND_CP_8") (pintype "bidirectional"))
      (node (ref "IC2") (pin "9") (pinfunction "GND_PLL_9") (pintype "bidirectional"))
      (node (ref "IC20") (pin "2") (pinfunction "V-_2") (pintype "power_in"))
      (node (ref "IC24") (pin "1") (pinfunction "GND_1") (pintype "bidirectional"))
      (node (ref "IC24") (pin "11") (pinfunction "GND_11") (pintype "bidirectional"))
      (node (ref "IC24") (pin "12") (pinfunction "EN_12") (pintype "bidirectional"))
      (node (ref "IC24") (pin "17") (pinfunction "GND_17") (pintype "bidirectional"))
      (node (ref "IC24") (pin "2") (pinfunction "GND_2") (pintype "bidirectional"))
      (node (ref "IC24") (pin "4") (pinfunction "GND_4") (pintype "bidirectional"))
      (node (ref "IC24") (pin "5") (pinfunction "GND_5") (pintype "bidirectional"))
      (node (ref "IC24") (pin "6") (pinfunction "GND_6") (pintype "bidirectional"))
      (node (ref "IC24") (pin "7") (pinfunction "GND_7") (pintype "bidirectional"))
      (node (ref "IC24") (pin "8") (pinfunction "GND_8") (pintype "bidirectional"))
      (node (ref "IC24") (pin "9") (pinfunction "GND_9") (pintype "bidirectional"))
      (node (ref "IC25") (pin "2") (pinfunction "GND_2") (pintype "bidirectional"))
      (node (ref "IC25") (pin "2@1") (pinfunction "GND_2@1") (pintype "bidirectional"))
      (node (ref "IC26") (pin "2") (pinfunction "GND_2") (pintype "bidirectional"))
      (node (ref "IC26") (pin "2@1") (pinfunction "GND_2@1") (pintype "bidirectional"))
      (node (ref "IC27") (pin "11") (pinfunction "GND_11") (pintype "bidirectional"))
      (node (ref "IC27") (pin "12") (pinfunction "GND_12") (pintype "bidirectional"))
      (node (ref "IC27") (pin "13") (pinfunction "GND_13") (pintype "bidirectional"))
      (node (ref "IC27") (pin "2") (pinfunction "GND_2") (pintype "bidirectional"))
      (node (ref "IC27") (pin "22") (pinfunction "GND_22") (pintype "bidirectional"))
      (node (ref "IC27") (pin "24") (pinfunction "GND_24") (pintype "bidirectional"))
      (node (ref "IC27") (pin "25") (pinfunction "GND_25") (pintype "bidirectional"))
      (node (ref "IC27") (pin "5") (pinfunction "GND_5") (pintype "bidirectional"))
      (node (ref "IC27") (pin "8") (pinfunction "GND_8") (pintype "bidirectional"))
      (node (ref "IC28") (pin "5") (pinfunction "LDAC_5") (pintype "bidirectional"))
      (node (ref "IC28") (pin "7") (pinfunction "VSS_7") (pintype "bidirectional"))
      (node (ref "IC29") (pin "2") (pinfunction "GND_2") (pintype "power_in"))
      (node (ref "IC3") (pin "2") (pinfunction "GND_2") (pintype "power_in"))
      (node (ref "IC3") (pin "4") (pinfunction "GND_4") (pintype "power_in"))
      (node (ref "IC31") (pin "1") (pinfunction "GND_1") (pintype "bidirectional"))
      (node (ref "IC31") (pin "10") (pinfunction "GND_10") (pintype "bidirectional"))
      (node (ref "IC31") (pin "12") (pinfunction "GND_12") (pintype "bidirectional"))
      (node (ref "IC31") (pin "13") (pinfunction "GND_13") (pintype "bidirectional"))
      (node (ref "IC31") (pin "15") (pinfunction "GND_15") (pintype "bidirectional"))
      (node (ref "IC31") (pin "20") (pinfunction "VSS_20") (pintype "bidirectional"))
      (node (ref "IC31") (pin "21") (pinfunction "GND_21") (pintype "bidirectional"))
      (node (ref "IC31") (pin "23") (pinfunction "GND_23") (pintype "bidirectional"))
      (node (ref "IC31") (pin "25") (pinfunction "GND_25") (pintype "bidirectional"))
      (node (ref "IC31") (pin "3") (pinfunction "GND_3") (pintype "bidirectional"))
      (node (ref "IC31") (pin "4") (pinfunction "GND_4") (pintype "bidirectional"))
      (node (ref "IC31") (pin "6") (pinfunction "GND_6") (pintype "bidirectional"))
      (node (ref "IC31") (pin "7") (pinfunction "GND_7") (pintype "bidirectional"))
      (node (ref "IC31") (pin "9") (pinfunction "GND_9") (pintype "bidirectional"))
      (node (ref "IC32") (pin "1") (pinfunction "GND_1") (pintype "bidirectional"))
      (node (ref "IC32") (pin "10") (pinfunction "GND_10") (pintype "bidirectional"))
      (node (ref "IC32") (pin "12") (pinfunction "GND_12") (pintype "bidirectional"))
      (node (ref "IC32") (pin "13") (pinfunction "GND_13") (pintype "bidirectional"))
      (node (ref "IC32") (pin "15") (pinfunction "GND_15") (pintype "bidirectional"))
      (node (ref "IC32") (pin "20") (pinfunction "VSS_20") (pintype "bidirectional"))
      (node (ref "IC32") (pin "21") (pinfunction "GND_21") (pintype "bidirectional"))
      (node (ref "IC32") (pin "23") (pinfunction "GND_23") (pintype "bidirectional"))
      (node (ref "IC32") (pin "25") (pinfunction "GND_25") (pintype "bidirectional"))
      (node (ref "IC32") (pin "3") (pinfunction "GND_3") (pintype "bidirectional"))
      (node (ref "IC32") (pin "4") (pinfunction "GND_4") (pintype "bidirectional"))
      (node (ref "IC32") (pin "6") (pinfunction "GND_6") (pintype "bidirectional"))
      (node (ref "IC32") (pin "7") (pinfunction "GND_7") (pintype "bidirectional"))
      (node (ref "IC32") (pin "9") (pinfunction "GND_9") (pintype "bidirectional"))
      (node (ref "IC4") (pin "2") (pinfunction "GND_2") (pintype "power_in"))
      (node (ref "IC5") (pin "2") (pinfunction "GND_2") (pintype "power_in"))
      (node (ref "IC6") (pin "10") (pinfunction "GND_10") (pintype "bidirectional"))
      (node (ref "IC6") (pin "12") (pinfunction "GND_12") (pintype "bidirectional"))
      (node (ref "IC6") (pin "13") (pinfunction "GND_13") (pintype "bidirectional"))
      (node (ref "IC6") (pin "15") (pinfunction "GND_15") (pintype "bidirectional"))
      (node (ref "IC6") (pin "20") (pinfunction "GND_20") (pintype "bidirectional"))
      (node (ref "IC6") (pin "23") (pinfunction "GND_23") (pintype "bidirectional"))
      (node (ref "IC6") (pin "26") (pinfunction "GND_26") (pintype "bidirectional"))
      (node (ref "IC6") (pin "27") (pinfunction "GND_27") (pintype "bidirectional"))
      (node (ref "IC6") (pin "30") (pinfunction "GND_30") (pintype "bidirectional"))
      (node (ref "IC6") (pin "33") (pinfunction "GND_33") (pintype "bidirectional"))
      (node (ref "IC6") (pin "36") (pinfunction "GND_36") (pintype "bidirectional"))
      (node (ref "IC6") (pin "39") (pinfunction "TORB_39") (pintype "bidirectional"))
      (node (ref "IC6") (pin "40") (pinfunction "PD_40") (pintype "bidirectional"))
      (node (ref "IC6") (pin "42") (pinfunction "XOR_42") (pintype "bidirectional"))
      (node (ref "IC6") (pin "43") (pinfunction "GND_43") (pintype "bidirectional"))
      (node (ref "IC6") (pin "69") (pinfunction "GND_69") (pintype "bidirectional"))
      (node (ref "IC7") (pin "2") (pinfunction "GND_2") (pintype "power_in"))
      (node (ref "IC8") (pin "2") (pinfunction "GND_2") (pintype "power_in"))
      (node (ref "IC9") (pin "2") (pinfunction "GND_2") (pintype "power_in"))
      (node (ref "J1") (pin "GND1") (pinfunction "P$2_GND1") (pintype "bidirectional"))
      (node (ref "J1") (pin "GND2") (pinfunction "P$2_GND2") (pintype "bidirectional"))
      (node (ref "JTAG") (pin "10") (pinfunction "10_10") (pintype "passive"))
      (node (ref "JTAG") (pin "2") (pinfunction "2_2") (pintype "passive"))
      (node (ref "Q1") (pin "2") (pinfunction "S_2") (pintype "passive"))
      (node (ref "Q2") (pin "2") (pinfunction "S_2") (pintype "passive"))
      (node (ref "Q3") (pin "2") (pinfunction "S_2") (pintype "passive"))
      (node (ref "Q4") (pin "2") (pinfunction "S_2") (pintype "passive"))
      (node (ref "Q5") (pin "2") (pinfunction "S_2") (pintype "passive"))
      (node (ref "R11") (pin "1") (pinfunction "1_1") (pintype "passive"))
      (node (ref "R12") (pin "1") (pinfunction "1_1") (pintype "passive"))
      (node (ref "R13") (pin "2") (pinfunction "2_2") (pintype "passive"))
      (node (ref "R14") (pin "2") (pinfunction "2_2") (pintype "passive"))
      (node (ref "R16") (pin "1") (pinfunction "1_1") (pintype "passive"))
      (node (ref "R18") (pin "2") (pinfunction "2_2") (pintype "passive"))
      (node (ref "R19") (pin "2") (pinfunction "2_2") (pintype "passive"))
      (node (ref "R20") (pin "2") (pinfunction "2_2") (pintype "passive"))
      (node (ref "R21") (pin "2") (pinfunction "2_2") (pintype "passive"))
      (node (ref "R3") (pin "2") (pinfunction "2_2") (pintype "passive"))
      (node (ref "R30") (pin "1") (pinfunction "1_1") (pintype "passive"))
      (node (ref "R33") (pin "2") (pinfunction "2_2") (pintype "passive"))
      (node (ref "R35") (pin "2") (pinfunction "2_2") (pintype "passive"))
      (node (ref "R36") (pin "2") (pinfunction "2_2") (pintype "passive"))
      (node (ref "R4") (pin "1") (pinfunction "1_1") (pintype "passive"))
      (node (ref "R42") (pin "2") (pinfunction "2_2") (pintype "passive"))
      (node (ref "R52") (pin "2") (pinfunction "2_2") (pintype "passive"))
      (node (ref "R53") (pin "1") (pinfunction "1_1") (pintype "passive"))
      (node (ref "R57") (pin "2") (pinfunction "2_2") (pintype "passive"))
      (node (ref "R58") (pin "2") (pinfunction "2_2") (pintype "passive"))
      (node (ref "R59") (pin "2") (pinfunction "2_2") (pintype "passive"))
      (node (ref "R6") (pin "2") (pinfunction "2_2") (pintype "passive"))
      (node (ref "R64") (pin "1") (pinfunction "1_1") (pintype "passive"))
      (node (ref "R66") (pin "2") (pinfunction "2_2") (pintype "passive"))
      (node (ref "R69") (pin "1") (pinfunction "1_1") (pintype "passive"))
      (node (ref "R78") (pin "1") (pinfunction "1_1") (pintype "passive"))
      (node (ref "R79") (pin "1") (pinfunction "1_1") (pintype "passive"))
      (node (ref "R80") (pin "1") (pinfunction "1_1") (pintype "passive"))
      (node (ref "R81") (pin "1") (pinfunction "1_1") (pintype "passive"))
      (node (ref "R82") (pin "1") (pinfunction "1_1") (pintype "passive"))
      (node (ref "SV2") (pin "5") (pinfunction "5_5") (pintype "passive"))
      (node (ref "SV2") (pin "7") (pinfunction "7_7") (pintype "passive"))
      (node (ref "SV2") (pin "9") (pinfunction "9_9") (pintype "passive"))
      (node (ref "SWD") (pin "3") (pinfunction "3_3") (pintype "passive"))
      (node (ref "TC1") (pin "2") (pinfunction "GND_2") (pintype "power_in"))
      (node (ref "U1") (pin "P108") (pinfunction "GND_P108") (pintype "power_in"))
      (node (ref "U1") (pin "P113") (pinfunction "GND_P113") (pintype "power_in"))
      (node (ref "U1") (pin "P13") (pinfunction "GND_P13") (pintype "power_in"))
      (node (ref "U1") (pin "P130") (pinfunction "GND_P130") (pintype "power_in"))
      (node (ref "U1") (pin "P136") (pinfunction "GND_P136") (pintype "power_in"))
      (node (ref "U1") (pin "P25") (pinfunction "GND_P25") (pintype "power_in"))
      (node (ref "U1") (pin "P3") (pinfunction "GND_P3") (pintype "power_in"))
      (node (ref "U1") (pin "P49") (pinfunction "GND_P49") (pintype "power_in"))
      (node (ref "U1") (pin "P54") (pinfunction "GND_P54") (pintype "power_in"))
      (node (ref "U1") (pin "P60") (pinfunction "IO_L13P_M1_2_P60") (pintype "bidirectional"))
      (node (ref "U1") (pin "P68") (pinfunction "GND_P68") (pintype "power_in"))
      (node (ref "U1") (pin "P73") (pinfunction "SUSPEND_P73") (pintype "input"))
      (node (ref "U1") (pin "P77") (pinfunction "GND_P77") (pintype "power_in"))
      (node (ref "U1") (pin "P91") (pinfunction "GND_P91") (pintype "power_in"))
      (node (ref "U1") (pin "P96") (pinfunction "GND_P96") (pintype "power_in"))
      (node (ref "U4") (pin "4") (pinfunction "GND_4") (pintype "power_in"))
      (node (ref "UART") (pin "2") (pinfunction "2_2") (pintype "passive"))
      (node (ref "X1") (pin "G@1") (pinfunction "2_G@1") (pintype "passive"))
      (node (ref "X1") (pin "G@2") (pinfunction "2_G@2") (pintype "passive"))
      (node (ref "X1") (pin "G@3") (pinfunction "2_G@3") (pintype "passive"))
      (node (ref "X1") (pin "G@4") (pinfunction "2_G@4") (pintype "passive"))
      (node (ref "X2") (pin "11") (pinfunction "1_11") (pintype "passive"))
      (node (ref "X2") (pin "6") (pinfunction "1_6") (pintype "passive"))
    )
    (net (code "32") (name "I0") (class "Default")
      (node (ref "IC6") (pin "56") (pinfunction "B0_56") (pintype "bidirectional"))
      (node (ref "U1") (pin "P126") (pinfunction "IO_L36N_GCLK14_0_P126") (pintype "bidirectional"))
    )
    (net (code "33") (name "I1") (class "Default")
      (node (ref "IC6") (pin "55") (pinfunction "B1_55") (pintype "bidirectional"))
      (node (ref "U1") (pin "P127") (pinfunction "IO_L36P_GCLK15_0_P127") (pintype "bidirectional"))
    )
    (net (code "34") (name "I2") (class "Default")
      (node (ref "IC6") (pin "54") (pinfunction "B2_54") (pintype "bidirectional"))
      (node (ref "U1") (pin "P131") (pinfunction "IO_L35N_GCLK16_0_P131") (pintype "bidirectional"))
    )
    (net (code "35") (name "I3") (class "Default")
      (node (ref "IC6") (pin "53") (pinfunction "B3_53") (pintype "bidirectional"))
      (node (ref "U1") (pin "P132") (pinfunction "IO_L35P_GCLK17_0_P132") (pintype "bidirectional"))
    )
    (net (code "36") (name "I4") (class "Default")
      (node (ref "IC6") (pin "52") (pinfunction "B4_52") (pintype "bidirectional"))
      (node (ref "U1") (pin "P133") (pinfunction "IO_L34N_GCLK18_0_P133") (pintype "bidirectional"))
    )
    (net (code "37") (name "I5") (class "Default")
      (node (ref "IC6") (pin "51") (pinfunction "B5_51") (pintype "bidirectional"))
      (node (ref "U1") (pin "P134") (pinfunction "IO_L34P_GCLK19_0_P134") (pintype "bidirectional"))
    )
    (net (code "38") (name "I6") (class "Default")
      (node (ref "IC6") (pin "50") (pinfunction "B6_50") (pintype "bidirectional"))
      (node (ref "U1") (pin "P137") (pinfunction "IO_L4N_0_P137") (pintype "bidirectional"))
    )
    (net (code "39") (name "I7") (class "Default")
      (node (ref "IC6") (pin "49") (pinfunction "B7_49") (pintype "bidirectional"))
      (node (ref "U1") (pin "P138") (pinfunction "IO_L4P_0_P138") (pintype "bidirectional"))
    )
    (net (code "40") (name "I8") (class "Default")
      (node (ref "IC6") (pin "48") (pinfunction "B8_48") (pintype "bidirectional"))
      (node (ref "U1") (pin "P139") (pinfunction "IO_L3N_0_P139") (pintype "bidirectional"))
    )
    (net (code "41") (name "I9") (class "Default")
      (node (ref "IC6") (pin "47") (pinfunction "B9_47") (pintype "bidirectional"))
      (node (ref "U1") (pin "P140") (pinfunction "IO_L3P_0_P140") (pintype "bidirectional"))
    )
    (net (code "42") (name "I10") (class "Default")
      (node (ref "IC6") (pin "46") (pinfunction "B10_46") (pintype "bidirectional"))
      (node (ref "U1") (pin "P141") (pinfunction "IO_L2N_0_P141") (pintype "bidirectional"))
    )
    (net (code "43") (name "I11") (class "Default")
      (node (ref "IC6") (pin "45") (pinfunction "B11_45") (pintype "bidirectional"))
      (node (ref "U1") (pin "P142") (pinfunction "IO_L2P_0_P142") (pintype "bidirectional"))
    )
    (net (code "44") (name "MIX_EN") (class "Default")
      (node (ref "IC13") (pin "18") (pinfunction "PB0_18") (pintype "bidirectional"))
      (node (ref "IC14") (pin "2") (pinfunction "EN_2") (pintype "bidirectional"))
    )
    (net (code "45") (name "MOD_IN") (class "Default")
      (node (ref "C49") (pin "2") (pinfunction "2_2") (pintype "passive"))
      (node (ref "IC1") (pin "22") (pinfunction "IN_22") (pintype "bidirectional"))
      (node (ref "L8") (pin "2") (pinfunction "2_2") (pintype "passive"))
      (node (ref "R23") (pin "1") (pinfunction "1_1") (pintype "passive"))
    )
    (net (code "46") (name "MOD_IP") (class "Default")
      (node (ref "C49") (pin "1") (pinfunction "1_1") (pintype "passive"))
      (node (ref "IC1") (pin "21") (pinfunction "IP_21") (pintype "bidirectional"))
      (node (ref "L7") (pin "2") (pinfunction "2_2") (pintype "passive"))
      (node (ref "R24") (pin "1") (pinfunction "1_1") (pintype "passive"))
    )
    (net (code "47") (name "MOD_OUT") (class "Default")
      (node (ref "C30") (pin "2") (pinfunction "2_2") (pintype "passive"))
      (node (ref "IC31") (pin "22") (pinfunction "RFC_22") (pintype "bidirectional"))
    )
    (net (code "48") (name "MOD_QN") (class "Default")
      (node (ref "C53") (pin "2") (pinfunction "2_2") (pintype "passive"))
      (node (ref "IC1") (pin "9") (pinfunction "QN_9") (pintype "bidirectional"))
      (node (ref "L14") (pin "2") (pinfunction "2_2") (pintype "passive"))
      (node (ref "R25") (pin "1") (pinfunction "1_1") (pintype "passive"))
    )
    (net (code "49") (name "MOD_QP") (class "Default")
      (node (ref "C53") (pin "1") (pinfunction "1_1") (pintype "passive"))
      (node (ref "IC1") (pin "10") (pinfunction "QP_10") (pintype "bidirectional"))
      (node (ref "L13") (pin "2") (pinfunction "2_2") (pintype "passive"))
      (node (ref "R22") (pin "1") (pinfunction "1_1") (pintype "passive"))
    )
    (net (code "50") (name "Net-(B1-+)") (class "Default")
      (node (ref "B1") (pin "3") (pinfunction "+_3") (pintype "bidirectional"))
      (node (ref "C120") (pin "2") (pinfunction "2_2") (pintype "passive"))
      (node (ref "L54") (pin "2") (pinfunction "2_2") (pintype "passive"))
    )
    (net (code "51") (name "Net-(B1--)") (class "Default")
      (node (ref "B1") (pin "4") (pinfunction "-_4") (pintype "bidirectional"))
      (node (ref "C120") (pin "1") (pinfunction "1_1") (pintype "passive"))
      (node (ref "L55") (pin "2") (pinfunction "2_2") (pintype "passive"))
    )
    (net (code "52") (name "Net-(B1-DC)") (class "Default")
      (node (ref "B1") (pin "2") (pinfunction "DC_2") (pintype "bidirectional"))
      (node (ref "R33") (pin "1") (pinfunction "1_1") (pintype "passive"))
    )
    (net (code "53") (name "Net-(B1-UN)") (class "Default")
      (node (ref "B1") (pin "1") (pinfunction "UN_1") (pintype "bidirectional"))
      (node (ref "R34") (pin "1") (pinfunction "1_1") (pintype "passive"))
      (node (ref "R36") (pin "1") (pinfunction "1_1") (pintype "passive"))
    )
    (net (code "54") (name "Net-(C6-Pad2)") (class "Default")
      (node (ref "C6") (pin "2") (pinfunction "2_2") (pintype "passive"))
      (node (ref "R2") (pin "1") (pinfunction "1_1") (pintype "passive"))
    )
    (net (code "55") (name "Net-(C20-Pad2)") (class "Default")
      (node (ref "C20") (pin "2") (pinfunction "2_2") (pintype "passive"))
      (node (ref "R10") (pin "1") (pinfunction "1_1") (pintype "passive"))
      (node (ref "R13") (pin "1") (pinfunction "1_1") (pintype "passive"))
    )
    (net (code "56") (name "Net-(C21-Pad2)") (class "Default")
      (node (ref "C21") (pin "2") (pinfunction "2_2") (pintype "passive"))
      (node (ref "R12") (pin "2") (pinfunction "2_2") (pintype "passive"))
      (node (ref "R9") (pin "1") (pinfunction "1_1") (pintype "passive"))
    )
    (net (code "57") (name "Net-(C47-Pad1)") (class "Default")
      (node (ref "C47") (pin "1") (pinfunction "1_1") (pintype "passive"))
      (node (ref "L3") (pin "2") (pinfunction "2_2") (pintype "passive"))
      (node (ref "L5") (pin "1") (pinfunction "1_1") (pintype "passive"))
    )
    (net (code "58") (name "Net-(C47-Pad2)") (class "Default")
      (node (ref "C47") (pin "2") (pinfunction "2_2") (pintype "passive"))
      (node (ref "L4") (pin "2") (pinfunction "2_2") (pintype "passive"))
      (node (ref "L6") (pin "1") (pinfunction "1_1") (pintype "passive"))
    )
    (net (code "59") (name "Net-(C48-Pad1)") (class "Default")
      (node (ref "C48") (pin "1") (pinfunction "1_1") (pintype "passive"))
      (node (ref "L5") (pin "2") (pinfunction "2_2") (pintype "passive"))
      (node (ref "L7") (pin "1") (pinfunction "1_1") (pintype "passive"))
    )
    (net (code "60") (name "Net-(C48-Pad2)") (class "Default")
      (node (ref "C48") (pin "2") (pinfunction "2_2") (pintype "passive"))
      (node (ref "L6") (pin "2") (pinfunction "2_2") (pintype "passive"))
      (node (ref "L8") (pin "1") (pinfunction "1_1") (pintype "passive"))
    )
    (net (code "61") (name "Net-(C51-Pad1)") (class "Default")
      (node (ref "C51") (pin "1") (pinfunction "1_1") (pintype "passive"))
      (node (ref "L11") (pin "1") (pinfunction "1_1") (pintype "passive"))
      (node (ref "L9") (pin "2") (pinfunction "2_2") (pintype "passive"))
    )
    (net (code "62") (name "Net-(C51-Pad2)") (class "Default")
      (node (ref "C51") (pin "2") (pinfunction "2_2") (pintype "passive"))
      (node (ref "L10") (pin "2") (pinfunction "2_2") (pintype "passive"))
      (node (ref "L12") (pin "1") (pinfunction "1_1") (pintype "passive"))
    )
    (net (code "63") (name "Net-(C52-Pad1)") (class "Default")
      (node (ref "C52") (pin "1") (pinfunction "1_1") (pintype "passive"))
      (node (ref "L11") (pin "2") (pinfunction "2_2") (pintype "passive"))
      (node (ref "L13") (pin "1") (pinfunction "1_1") (pintype "passive"))
    )
    (net (code "64") (name "Net-(C52-Pad2)") (class "Default")
      (node (ref "C52") (pin "2") (pinfunction "2_2") (pintype "passive"))
      (node (ref "L12") (pin "2") (pinfunction "2_2") (pintype "passive"))
      (node (ref "L14") (pin "1") (pinfunction "1_1") (pintype "passive"))
    )
    (net (code "65") (name "Net-(C55-Pad1)") (class "Default")
      (node (ref "C55") (pin "1") (pinfunction "1_1") (pintype "passive"))
      (node (ref "R23") (pin "2") (pinfunction "2_2") (pintype "passive"))
      (node (ref "R24") (pin "2") (pinfunction "2_2") (pintype "passive"))
      (node (ref "R26") (pin "2") (pinfunction "2_2") (pintype "passive"))
    )
    (net (code "66") (name "Net-(C63-Pad1)") (class "Default")
      (node (ref "C63") (pin "1") (pinfunction "1_1") (pintype "passive"))
      (node (ref "L20") (pin "1") (pinfunction "1_1") (pintype "passive"))
      (node (ref "L21") (pin "2") (pinfunction "2_2") (pintype "passive"))
    )
    (net (code "67") (name "Net-(C64-Pad1)") (class "Default")
      (node (ref "C64") (pin "1") (pinfunction "1_1") (pintype "passive"))
      (node (ref "L19") (pin "1") (pinfunction "1_1") (pintype "passive"))
      (node (ref "L20") (pin "2") (pinfunction "2_2") (pintype "passive"))
    )
    (net (code "68") (name "Net-(C65-Pad1)") (class "Default")
      (node (ref "C65") (pin "1") (pinfunction "1_1") (pintype "passive"))
      (node (ref "L18") (pin "1") (pinfunction "1_1") (pintype "passive"))
      (node (ref "L19") (pin "2") (pinfunction "2_2") (pintype "passive"))
    )
    (net (code "69") (name "Net-(C66-Pad1)") (class "Default")
      (node (ref "C66") (pin "1") (pinfunction "1_1") (pintype "passive"))
      (node (ref "L17") (pin "1") (pinfunction "1_1") (pintype "passive"))
      (node (ref "L18") (pin "2") (pinfunction "2_2") (pintype "passive"))
    )
    (net (code "70") (name "Net-(C67-Pad1)") (class "Default")
      (node (ref "C67") (pin "1") (pinfunction "1_1") (pintype "passive"))
      (node (ref "L16") (pin "1") (pinfunction "1_1") (pintype "passive"))
      (node (ref "L17") (pin "2") (pinfunction "2_2") (pintype "passive"))
    )
    (net (code "71") (name "Net-(C68-Pad1)") (class "Default")
      (node (ref "C68") (pin "1") (pinfunction "1_1") (pintype "passive"))
      (node (ref "L15") (pin "1") (pinfunction "1_1") (pintype "passive"))
      (node (ref "L16") (pin "2") (pinfunction "2_2") (pintype "passive"))
    )
    (net (code "72") (name "Net-(C71-Pad1)") (class "Default")
      (node (ref "C71") (pin "1") (pinfunction "1_1") (pintype "passive"))
      (node (ref "L22") (pin "1") (pinfunction "1_1") (pintype "passive"))
      (node (ref "L23") (pin "2") (pinfunction "2_2") (pintype "passive"))
    )
    (net (code "73") (name "Net-(C72-Pad1)") (class "Default")
      (node (ref "C72") (pin "1") (pinfunction "1_1") (pintype "passive"))
      (node (ref "L23") (pin "1") (pinfunction "1_1") (pintype "passive"))
      (node (ref "L24") (pin "2") (pinfunction "2_2") (pintype "passive"))
    )
    (net (code "74") (name "Net-(C73-Pad1)") (class "Default")
      (node (ref "C73") (pin "1") (pinfunction "1_1") (pintype "passive"))
      (node (ref "L24") (pin "1") (pinfunction "1_1") (pintype "passive"))
      (node (ref "L25") (pin "2") (pinfunction "2_2") (pintype "passive"))
    )
    (net (code "75") (name "Net-(C74-Pad1)") (class "Default")
      (node (ref "C74") (pin "1") (pinfunction "1_1") (pintype "passive"))
      (node (ref "L25") (pin "1") (pinfunction "1_1") (pintype "passive"))
      (node (ref "L26") (pin "2") (pinfunction "2_2") (pintype "passive"))
    )
    (net (code "76") (name "Net-(C75-Pad1)") (class "Default")
      (node (ref "C75") (pin "1") (pinfunction "1_1") (pintype "passive"))
      (node (ref "L26") (pin "1") (pinfunction "1_1") (pintype "passive"))
      (node (ref "L27") (pin "2") (pinfunction "2_2") (pintype "passive"))
    )
    (net (code "77") (name "Net-(C76-Pad1)") (class "Default")
      (node (ref "C76") (pin "1") (pinfunction "1_1") (pintype "passive"))
      (node (ref "L27") (pin "1") (pinfunction "1_1") (pintype "passive"))
      (node (ref "L28") (pin "2") (pinfunction "2_2") (pintype "passive"))
    )
    (net (code "78") (name "Net-(C79-Pad1)") (class "Default")
      (node (ref "C79") (pin "1") (pinfunction "1_1") (pintype "passive"))
      (node (ref "L29") (pin "1") (pinfunction "1_1") (pintype "passive"))
      (node (ref "L30") (pin "2") (pinfunction "2_2") (pintype "passive"))
    )
    (net (code "79") (name "Net-(C80-Pad1)") (class "Default")
      (node (ref "C80") (pin "1") (pinfunction "1_1") (pintype "passive"))
      (node (ref "L30") (pin "1") (pinfunction "1_1") (pintype "passive"))
      (node (ref "L31") (pin "2") (pinfunction "2_2") (pintype "passive"))
    )
    (net (code "80") (name "Net-(C81-Pad1)") (class "Default")
      (node (ref "C81") (pin "1") (pinfunction "1_1") (pintype "passive"))
      (node (ref "L31") (pin "1") (pinfunction "1_1") (pintype "passive"))
      (node (ref "L32") (pin "2") (pinfunction "2_2") (pintype "passive"))
    )
    (net (code "81") (name "Net-(C82-Pad1)") (class "Default")
      (node (ref "C82") (pin "1") (pinfunction "1_1") (pintype "passive"))
      (node (ref "L32") (pin "1") (pinfunction "1_1") (pintype "passive"))
      (node (ref "L33") (pin "2") (pinfunction "2_2") (pintype "passive"))
    )
    (net (code "82") (name "Net-(C83-Pad1)") (class "Default")
      (node (ref "C83") (pin "1") (pinfunction "1_1") (pintype "passive"))
      (node (ref "L33") (pin "1") (pinfunction "1_1") (pintype "passive"))
      (node (ref "L34") (pin "2") (pinfunction "2_2") (pintype "passive"))
    )
    (net (code "83") (name "Net-(C84-Pad1)") (class "Default")
      (node (ref "C84") (pin "1") (pinfunction "1_1") (pintype "passive"))
      (node (ref "L34") (pin "1") (pinfunction "1_1") (pintype "passive"))
      (node (ref "L35") (pin "2") (pinfunction "2_2") (pintype "passive"))
    )
    (net (code "84") (name "Net-(C87-Pad1)") (class "Default")
      (node (ref "C87") (pin "1") (pinfunction "1_1") (pintype "passive"))
      (node (ref "L36") (pin "1") (pinfunction "1_1") (pintype "passive"))
      (node (ref "L37") (pin "2") (pinfunction "2_2") (pintype "passive"))
    )
    (net (code "85") (name "Net-(C88-Pad1)") (class "Default")
      (node (ref "C88") (pin "1") (pinfunction "1_1") (pintype "passive"))
      (node (ref "L37") (pin "1") (pinfunction "1_1") (pintype "passive"))
      (node (ref "L38") (pin "2") (pinfunction "2_2") (pintype "passive"))
    )
    (net (code "86") (name "Net-(C89-Pad1)") (class "Default")
      (node (ref "C89") (pin "1") (pinfunction "1_1") (pintype "passive"))
      (node (ref "L38") (pin "1") (pinfunction "1_1") (pintype "passive"))
      (node (ref "L39") (pin "2") (pinfunction "2_2") (pintype "passive"))
    )
    (net (code "87") (name "Net-(C90-Pad1)") (class "Default")
      (node (ref "C90") (pin "1") (pinfunction "1_1") (pintype "passive"))
      (node (ref "L39") (pin "1") (pinfunction "1_1") (pintype "passive"))
      (node (ref "L40") (pin "2") (pinfunction "2_2") (pintype "passive"))
    )
    (net (code "88") (name "Net-(C91-Pad1)") (class "Default")
      (node (ref "C91") (pin "1") (pinfunction "1_1") (pintype "passive"))
      (node (ref "L40") (pin "1") (pinfunction "1_1") (pintype "passive"))
      (node (ref "L41") (pin "2") (pinfunction "2_2") (pintype "passive"))
    )
    (net (code "89") (name "Net-(C92-Pad1)") (class "Default")
      (node (ref "C92") (pin "1") (pinfunction "1_1") (pintype "passive"))
      (node (ref "L41") (pin "1") (pinfunction "1_1") (pintype "passive"))
      (node (ref "L42") (pin "2") (pinfunction "2_2") (pintype "passive"))
    )
    (net (code "90") (name "Net-(C95-Pad1)") (class "Default")
      (node (ref "C95") (pin "1") (pinfunction "1_1") (pintype "passive"))
      (node (ref "L43") (pin "1") (pinfunction "1_1") (pintype "passive"))
      (node (ref "L44") (pin "2") (pinfunction "2_2") (pintype "passive"))
    )
    (net (code "91") (name "Net-(C96-Pad1)") (class "Default")
      (node (ref "C96") (pin "1") (pinfunction "1_1") (pintype "passive"))
      (node (ref "L44") (pin "1") (pinfunction "1_1") (pintype "passive"))
      (node (ref "L45") (pin "2") (pinfunction "2_2") (pintype "passive"))
    )
    (net (code "92") (name "Net-(C97-Pad1)") (class "Default")
      (node (ref "C97") (pin "1") (pinfunction "1_1") (pintype "passive"))
      (node (ref "L45") (pin "1") (pinfunction "1_1") (pintype "passive"))
      (node (ref "L46") (pin "2") (pinfunction "2_2") (pintype "passive"))
    )
    (net (code "93") (name "Net-(C98-Pad1)") (class "Default")
      (node (ref "C98") (pin "1") (pinfunction "1_1") (pintype "passive"))
      (node (ref "L46") (pin "1") (pinfunction "1_1") (pintype "passive"))
      (node (ref "L47") (pin "2") (pinfunction "2_2") (pintype "passive"))
    )
    (net (code "94") (name "Net-(C99-Pad1)") (class "Default")
      (node (ref "C99") (pin "1") (pinfunction "1_1") (pintype "passive"))
      (node (ref "L47") (pin "1") (pinfunction "1_1") (pintype "passive"))
      (node (ref "L48") (pin "2") (pinfunction "2_2") (pintype "passive"))
    )
    (net (code "95") (name "Net-(C100-Pad1)") (class "Default")
      (node (ref "C100") (pin "1") (pinfunction "1_1") (pintype "passive"))
      (node (ref "L48") (pin "1") (pinfunction "1_1") (pintype "passive"))
      (node (ref "L49") (pin "2") (pinfunction "2_2") (pintype "passive"))
    )
    (net (code "96") (name "Net-(C102-Pad1)") (class "Default")
      (node (ref "C102") (pin "1") (pinfunction "1_1") (pintype "passive"))
      (node (ref "R29") (pin "2") (pinfunction "2_2") (pintype "passive"))
    )
    (net (code "97") (name "Net-(C106-Pad2)") (class "Default")
      (node (ref "C106") (pin "2") (pinfunction "2_2") (pintype "passive"))
      (node (ref "C108") (pin "1") (pinfunction "1_1") (pintype "passive"))
      (node (ref "L52") (pin "2") (pinfunction "2_2") (pintype "passive"))
    )
    (net (code "98") (name "Net-(C107-Pad1)") (class "Default")
      (node (ref "C107") (pin "1") (pinfunction "1_1") (pintype "passive"))
      (node (ref "C108") (pin "2") (pinfunction "2_2") (pintype "passive"))
      (node (ref "L53") (pin "2") (pinfunction "2_2") (pintype "passive"))
    )
    (net (code "99") (name "Net-(C110-Pad1)") (class "Default")
      (node (ref "C110") (pin "1") (pinfunction "1_1") (pintype "passive"))
      (node (ref "R22") (pin "2") (pinfunction "2_2") (pintype "passive"))
      (node (ref "R25") (pin "2") (pinfunction "2_2") (pintype "passive"))
      (node (ref "R28") (pin "2") (pinfunction "2_2") (pintype "passive"))
    )
    (net (code "100") (name "Net-(C124-Pad2)") (class "Default")
      (node (ref "C124") (pin "2") (pinfunction "2_2") (pintype "passive"))
      (node (ref "R40") (pin "1") (pinfunction "1_1") (pintype "passive"))
      (node (ref "R41") (pin "1") (pinfunction "1_1") (pintype "passive"))
      (node (ref "R42") (pin "1") (pinfunction "1_1") (pintype "passive"))
    )
    (net (code "101") (name "Net-(C125-Pad1)") (class "Default")
      (node (ref "C125") (pin "1") (pinfunction "1_1") (pintype "passive"))
      (node (ref "R43") (pin "1") (pinfunction "1_1") (pintype "passive"))
    )
    (net (code "102") (name "Net-(C126-Pad2)") (class "Default")
      (node (ref "C126") (pin "2") (pinfunction "2_2") (pintype "passive"))
      (node (ref "L58") (pin "2") (pinfunction "2_2") (pintype "passive"))
      (node (ref "R43") (pin "2") (pinfunction "2_2") (pintype "passive"))
    )
    (net (code "103") (name "Net-(C128-Pad2)") (class "Default")
      (node (ref "C128") (pin "2") (pinfunction "2_2") (pintype "passive"))
      (node (ref "L59") (pin "1") (pinfunction "1_1") (pintype "passive"))
      (node (ref "L60") (pin "2") (pinfunction "2_2") (pintype "passive"))
    )
    (net (code "104") (name "Net-(C129-Pad2)") (class "Default")
      (node (ref "C129") (pin "2") (pinfunction "2_2") (pintype "passive"))
      (node (ref "L58") (pin "1") (pinfunction "1_1") (pintype "passive"))
      (node (ref "L59") (pin "2") (pinfunction "2_2") (pintype "passive"))
    )
    (net (code "105") (name "Net-(C143-Pad1)") (class "Default")
      (node (ref "C143") (pin "1") (pinfunction "1_1") (pintype "passive"))
      (node (ref "R50") (pin "1") (pinfunction "1_1") (pintype "passive"))
    )
    (net (code "106") (name "Net-(C143-Pad2)") (class "Default")
      (node (ref "C143") (pin "2") (pinfunction "2_2") (pintype "passive"))
      (node (ref "X1") (pin "1") (pinfunction "1_1") (pintype "passive"))
    )
    (net (code "107") (name "Net-(C144-Pad1)") (class "Default")
      (node (ref "C144") (pin "1") (pinfunction "1_1") (pintype "passive"))
      (node (ref "R49") (pin "2") (pinfunction "2_2") (pintype "passive"))
    )
    (net (code "108") (name "Net-(C148-Pad1)") (class "Default")
      (node (ref "C148") (pin "1") (pinfunction "1_1") (pintype "passive"))
      (node (ref "IC27") (pin "1") (pinfunction "VCC_1") (pintype "bidirectional"))
      (node (ref "IC27") (pin "16") (pinfunction "VCC_16") (pintype "bidirectional"))
      (node (ref "IC27") (pin "21") (pinfunction "VCC_21") (pintype "bidirectional"))
      (node (ref "IC27") (pin "23") (pinfunction "VCC_23") (pintype "bidirectional"))
      (node (ref "L67") (pin "1") (pinfunction "1_1") (pintype "passive"))
    )
    (net (code "109") (name "Net-(C149-Pad1)") (class "Default")
      (node (ref "C149") (pin "1") (pinfunction "1_1") (pintype "passive"))
      (node (ref "R51") (pin "2") (pinfunction "2_2") (pintype "passive"))
      (node (ref "R52") (pin "1") (pinfunction "1_1") (pintype "passive"))
    )
    (net (code "110") (name "Net-(C150-Pad1)") (class "Default")
      (node (ref "C150") (pin "1") (pinfunction "1_1") (pintype "passive"))
      (node (ref "R53") (pin "2") (pinfunction "2_2") (pintype "passive"))
    )
    (net (code "111") (name "Net-(C153-Pad1)") (class "Default")
      (node (ref "C153") (pin "1") (pinfunction "1_1") (pintype "passive"))
      (node (ref "R62") (pin "2") (pinfunction "2_2") (pintype "passive"))
      (node (ref "R63") (pin "1") (pinfunction "1_1") (pintype "passive"))
      (node (ref "R65") (pin "1") (pinfunction "1_1") (pintype "passive"))
    )
    (net (code "112") (name "Net-(IC1-LON)") (class "Default")
      (node (ref "IC1") (pin "4") (pinfunction "LON_4") (pintype "bidirectional"))
      (node (ref "R11") (pin "2") (pinfunction "2_2") (pintype "passive"))
      (node (ref "R9") (pin "2") (pinfunction "2_2") (pintype "passive"))
    )
    (net (code "113") (name "Net-(IC1-LOP)") (class "Default")
      (node (ref "IC1") (pin "3") (pinfunction "LOP_3") (pintype "bidirectional"))
      (node (ref "R10") (pin "2") (pinfunction "2_2") (pintype "passive"))
      (node (ref "R14") (pin "1") (pinfunction "1_1") (pintype "passive"))
    )
    (net (code "114") (name "Net-(IC1-RFOUT)") (class "Default")
      (node (ref "C30") (pin "1") (pinfunction "1_1") (pintype "passive"))
      (node (ref "IC1") (pin "16") (pinfunction "RFOUT_16") (pintype "bidirectional"))
    )
    (net (code "115") (name "Net-(IC1-VCC1)") (class "Default")
      (node (ref "C25") (pin "2") (pinfunction "2_2") (pintype "passive"))
      (node (ref "C28") (pin "2") (pinfunction "2_2") (pintype "passive"))
      (node (ref "IC1") (pin "18") (pinfunction "VCC1_18") (pintype "bidirectional"))
      (node (ref "L1") (pin "2") (pinfunction "2_2") (pintype "passive"))
    )
    (net (code "116") (name "Net-(IC1-VCC2)") (class "Default")
      (node (ref "C26") (pin "1") (pinfunction "1_1") (pintype "passive"))
      (node (ref "C27") (pin "1") (pinfunction "1_1") (pintype "passive"))
      (node (ref "IC1") (pin "24") (pinfunction "VCC2_24") (pintype "bidirectional"))
      (node (ref "L2") (pin "2") (pinfunction "2_2") (pintype "passive"))
    )
    (net (code "117") (name "Net-(IC2-BIAS_FILT)") (class "Default")
      (node (ref "C3") (pin "1") (pinfunction "1_1") (pintype "passive"))
      (node (ref "IC2") (pin "23") (pinfunction "BIAS_FILT_23") (pintype "bidirectional"))
    )
    (net (code "118") (name "Net-(IC2-CP_OUT)") (class "Default")
      (node (ref "C4") (pin "1") (pinfunction "1_1") (pintype "passive"))
      (node (ref "C6") (pin "1") (pinfunction "1_1") (pintype "passive"))
      (node (ref "IC2") (pin "7") (pinfunction "CP_OUT_7") (pintype "bidirectional"))
      (node (ref "R1") (pin "1") (pinfunction "1_1") (pintype "passive"))
    )
    (net (code "119") (name "Net-(IC2-NOISE_FILT)") (class "Default")
      (node (ref "C2") (pin "1") (pinfunction "1_1") (pintype "passive"))
      (node (ref "IC2") (pin "19") (pinfunction "NOISE_FILT_19") (pintype "bidirectional"))
    )
    (net (code "120") (name "Net-(IC2-REF_IN)") (class "Default")
      (node (ref "C19") (pin "2") (pinfunction "2_2") (pintype "passive"))
      (node (ref "IC2") (pin "29") (pinfunction "REF_IN_29") (pintype "input"))
    )
    (net (code "121") (name "Net-(IC2-REG)") (class "Default")
      (node (ref "C1") (pin "1") (pinfunction "1_1") (pintype "passive"))
      (node (ref "IC2") (pin "24") (pinfunction "REG_24") (pintype "bidirectional"))
    )
    (net (code "122") (name "Net-(IC2-RFOUTA_N)") (class "Default")
      (node (ref "C20") (pin "1") (pinfunction "1_1") (pintype "passive"))
      (node (ref "IC2") (pin "13") (pinfunction "RFOUTA_N_13") (pintype "bidirectional"))
      (node (ref "R7") (pin "1") (pinfunction "1_1") (pintype "passive"))
    )
    (net (code "123") (name "Net-(IC2-RFOUTA_P)") (class "Default")
      (node (ref "C21") (pin "1") (pinfunction "1_1") (pintype "passive"))
      (node (ref "IC2") (pin "12") (pinfunction "RFOUTA_P_12") (pintype "bidirectional"))
      (node (ref "R8") (pin "1") (pinfunction "1_1") (pintype "passive"))
    )
    (net (code "124") (name "Net-(IC2-RSET)") (class "Default")
      (node (ref "IC2") (pin "22") (pinfunction "RSET_22") (pintype "bidirectional"))
      (node (ref "R4") (pin "2") (pinfunction "2_2") (pintype "passive"))
    )
    (net (code "125") (name "Net-(IC2-SW)") (class "Default")
      (node (ref "IC2") (pin "5") (pinfunction "SW_5") (pintype "bidirectional"))
      (node (ref "R2") (pin "2") (pinfunction "2_2") (pintype "passive"))
      (node (ref "R3") (pin "1") (pinfunction "1_1") (pintype "passive"))
    )
    (net (code "126") (name "Net-(IC2-TUNE)") (class "Default")
      (node (ref "C5") (pin "2") (pinfunction "2_2") (pintype "passive"))
      (node (ref "IC2") (pin "20") (pinfunction "TUNE_20") (pintype "bidirectional"))
      (node (ref "R1") (pin "2") (pinfunction "2_2") (pintype "passive"))
    )
    (net (code "127") (name "Net-(IC2-VCC_CP)") (class "Default")
      (node (ref "C11") (pin "1") (pinfunction "1_1") (pintype "passive"))
      (node (ref "C15") (pin "1") (pinfunction "1_1") (pintype "passive"))
      (node (ref "C16") (pin "1") (pinfunction "1_1") (pintype "passive"))
      (node (ref "IC2") (pin "10") (pinfunction "VCC_PLL_10") (pintype "bidirectional"))
      (node (ref "IC2") (pin "6") (pinfunction "VCC_CP_6") (pintype "bidirectional"))
      (node (ref "IC4") (pin "5") (pinfunction "VOUT_5") (pintype "power_in"))
    )
    (net (code "128") (name "Net-(IC2-VCC_DIG)") (class "Default")
      (node (ref "C14") (pin "1") (pinfunction "1_1") (pintype "passive"))
      (node (ref "C7") (pin "1") (pinfunction "1_1") (pintype "passive"))
      (node (ref "C8") (pin "1") (pinfunction "1_1") (pintype "passive"))
      (node (ref "IC2") (pin "28") (pinfunction "VCC_DIG_28") (pintype "bidirectional"))
      (node (ref "IC2") (pin "32") (pinfunction "VDD_SD_32") (pintype "bidirectional"))
      (node (ref "IC5") (pin "5") (pinfunction "VOUT_5") (pintype "power_in"))
    )
    (net (code "129") (name "Net-(IC2-VCC_RF)") (class "Default")
      (node (ref "C13") (pin "1") (pinfunction "1_1") (pintype "passive"))
      (node (ref "C18") (pin "1") (pinfunction "1_1") (pintype "passive"))
      (node (ref "IC2") (pin "16") (pinfunction "VCC_RF_16") (pintype "bidirectional"))
      (node (ref "IC2") (pin "17") (pinfunction "VCC_VCO_17") (pintype "bidirectional"))
      (node (ref "IC3") (pin "3") (pinfunction "VOUT_3") (pintype "power_in"))
      (node (ref "R7") (pin "2") (pinfunction "2_2") (pintype "passive"))
      (node (ref "R8") (pin "2") (pinfunction "2_2") (pintype "passive"))
    )
    (net (code "130") (name "Net-(IC6-AVCLK)") (class "Default")
      (node (ref "C35") (pin "1") (pinfunction "1_1") (pintype "passive"))
      (node (ref "C42") (pin "1") (pinfunction "1_1") (pintype "passive"))
      (node (ref "C43") (pin "1") (pinfunction "1_1") (pintype "passive"))
      (node (ref "C44") (pin "1") (pinfunction "1_1") (pintype "passive"))
      (node (ref "C45") (pin "1") (pinfunction "1_1") (pintype "passive"))
      (node (ref "IC6") (pin "14") (pinfunction "AVDD3.3_14") (pintype "bidirectional"))
      (node (ref "IC6") (pin "21") (pinfunction "AVDD3.3_21") (pintype "bidirectional"))
      (node (ref "IC6") (pin "22") (pinfunction "AVDD3.3_22") (pintype "bidirectional"))
      (node (ref "IC6") (pin "31") (pinfunction "AVDD3.3_31") (pintype "bidirectional"))
      (node (ref "IC6") (pin "32") (pinfunction "AVDD3.3_32") (pintype "bidirectional"))
      (node (ref "IC6") (pin "35") (pinfunction "AVCLK_35") (pintype "bidirectional"))
      (node (ref "IC9") (pin "5") (pinfunction "VOUT_5") (pintype "power_in"))
    )
    (net (code "131") (name "Net-(IC6-CLKN)") (class "Default")
      (node (ref "C57") (pin "1") (pinfunction "1_1") (pintype "passive"))
      (node (ref "IC6") (pin "37") (pinfunction "CLKN_37") (pintype "bidirectional"))
    )
    (net (code "132") (name "Net-(IC6-CLKP)") (class "Default")
      (node (ref "C58") (pin "1") (pinfunction "1_1") (pintype "passive"))
      (node (ref "IC6") (pin "38") (pinfunction "CLKP_38") (pintype "bidirectional"))
    )
    (net (code "133") (name "Net-(IC6-DACREF)") (class "Default")
      (node (ref "IC6") (pin "18") (pinfunction "DACREF_18") (pintype "bidirectional"))
      (node (ref "R17") (pin "2") (pinfunction "2_2") (pintype "passive"))
    )
    (net (code "134") (name "Net-(IC6-DVDD1.8)") (class "Default")
      (node (ref "C31") (pin "1") (pinfunction "1_1") (pintype "passive"))
      (node (ref "C40") (pin "1") (pinfunction "1_1") (pintype "passive"))
      (node (ref "IC6") (pin "61") (pinfunction "DVDD1.8_61") (pintype "bidirectional"))
      (node (ref "IC7") (pin "5") (pinfunction "VOUT_5") (pintype "power_in"))
    )
    (net (code "135") (name "Net-(IC6-FSADJ)") (class "Default")
      (node (ref "IC6") (pin "17") (pinfunction "FSADJ_17") (pintype "bidirectional"))
      (node (ref "R17") (pin "1") (pinfunction "1_1") (pintype "passive"))
    )
    (net (code "136") (name "Net-(IC6-OUTIN)") (class "Default")
      (node (ref "C46") (pin "2") (pinfunction "2_2") (pintype "passive"))
      (node (ref "IC6") (pin "28") (pinfunction "OUTIN_28") (pintype "bidirectional"))
      (node (ref "L4") (pin "1") (pinfunction "1_1") (pintype "passive"))
      (node (ref "R20") (pin "1") (pinfunction "1_1") (pintype "passive"))
    )
    (net (code "137") (name "Net-(IC6-OUTIP)") (class "Default")
      (node (ref "C46") (pin "1") (pinfunction "1_1") (pintype "passive"))
      (node (ref "IC6") (pin "29") (pinfunction "OUTIP_29") (pintype "bidirectional"))
      (node (ref "L3") (pin "1") (pinfunction "1_1") (pintype "passive"))
      (node (ref "R19") (pin "1") (pinfunction "1_1") (pintype "passive"))
    )
    (net (code "138") (name "Net-(IC6-OUTQN)") (class "Default")
      (node (ref "C50") (pin "2") (pinfunction "2_2") (pintype "passive"))
      (node (ref "IC6") (pin "24") (pinfunction "OUTQN_24") (pintype "bidirectional"))
      (node (ref "L10") (pin "1") (pinfunction "1_1") (pintype "passive"))
      (node (ref "R18") (pin "1") (pinfunction "1_1") (pintype "passive"))
    )
    (net (code "139") (name "Net-(IC6-OUTQP)") (class "Default")
      (node (ref "C50") (pin "1") (pinfunction "1_1") (pintype "passive"))
      (node (ref "IC6") (pin "25") (pinfunction "OUTQP_25") (pintype "bidirectional"))
      (node (ref "L9") (pin "1") (pinfunction "1_1") (pintype "passive"))
      (node (ref "R21") (pin "1") (pinfunction "1_1") (pintype "passive"))
    )
    (net (code "140") (name "Net-(IC6-REFIO)") (class "Default")
      (node (ref "C54") (pin "1") (pinfunction "1_1") (pintype "passive"))
      (node (ref "IC6") (pin "16") (pinfunction "REFIO_16") (pintype "bidirectional"))
    )
    (net (code "141") (name "Net-(IC10-VOUT)") (class "Default")
      (node (ref "C37") (pin "1") (pinfunction "1_1") (pintype "passive"))
      (node (ref "C41") (pin "1") (pinfunction "1_1") (pintype "passive"))
      (node (ref "IC10") (pin "5") (pinfunction "VOUT_5") (pintype "power_in"))
      (node (ref "IC6") (pin "19") (pinfunction "AVDD1.8_19") (pintype "bidirectional"))
      (node (ref "IC6") (pin "34") (pinfunction "AVDD1.8_34") (pintype "bidirectional"))
    )
    (net (code "142") (name "Net-(IC11A-SS)") (class "Default")
      (node (ref "C23") (pin "1") (pinfunction "1_1") (pintype "passive"))
      (node (ref "IC11") (pin "8") (pinfunction "SS_8") (pintype "bidirectional"))
    )
    (net (code "143") (name "Net-(IC11A-SW)") (class "Default")
      (node (ref "C157") (pin "1") (pinfunction "1_1") (pintype "passive"))
      (node (ref "IC11") (pin "5") (pinfunction "SW_5") (pintype "bidirectional"))
      (node (ref "L70") (pin "P$1") (pinfunction "1_P$1") (pintype "passive"))
    )
    (net (code "144") (name "Net-(IC11A-VBST)") (class "Default")
      (node (ref "C157") (pin "2") (pinfunction "2_2") (pintype "passive"))
      (node (ref "IC11") (pin "4") (pinfunction "VBST_4") (pintype "bidirectional"))
    )
    (net (code "145") (name "Net-(IC11A-VFB)") (class "Default")
      (node (ref "C160") (pin "2") (pinfunction "2_2") (pintype "passive"))
      (node (ref "IC11") (pin "9") (pinfunction "VFB_9") (pintype "bidirectional"))
      (node (ref "R5") (pin "2") (pinfunction "2_2") (pintype "passive"))
      (node (ref "R6") (pin "1") (pinfunction "1_1") (pintype "passive"))
    )
    (net (code "146") (name "Net-(IC11B-SS)") (class "Default")
      (node (ref "C161") (pin "1") (pinfunction "1_1") (pintype "passive"))
      (node (ref "IC11") (pin "13") (pinfunction "SS_13") (pintype "bidirectional"))
    )
    (net (code "147") (name "Net-(IC11B-SW)") (class "Default")
      (node (ref "C163") (pin "1") (pinfunction "1_1") (pintype "passive"))
      (node (ref "IC11") (pin "16") (pinfunction "SW_16") (pintype "bidirectional"))
      (node (ref "L71") (pin "P$1") (pinfunction "1_P$1") (pintype "passive"))
    )
    (net (code "148") (name "Net-(IC11B-VBST)") (class "Default")
      (node (ref "C163") (pin "2") (pinfunction "2_2") (pintype "passive"))
      (node (ref "IC11") (pin "1") (pinfunction "VBST_1") (pintype "bidirectional"))
    )
    (net (code "149") (name "Net-(IC11B-VFB)") (class "Default")
      (node (ref "IC11") (pin "12") (pinfunction "VFB_12") (pintype "bidirectional"))
      (node (ref "R15") (pin "2") (pinfunction "2_2") (pintype "passive"))
      (node (ref "R66") (pin "1") (pinfunction "1_1") (pintype "passive"))
    )
    (net (code "150") (name "Net-(IC11C-VREG5)") (class "Default")
      (node (ref "C22") (pin "1") (pinfunction "1_1") (pintype "passive"))
      (node (ref "IC11") (pin "11") (pinfunction "VREG5_11") (pintype "bidirectional"))
    )
    (net (code "151") (name "Net-(IC12-VA)") (class "Default")
      (node (ref "IC12") (pin "8") (pinfunction "VA_8") (pintype "bidirectional"))
      (node (ref "R26") (pin "1") (pinfunction "1_1") (pintype "passive"))
    )
    (net (code "152") (name "Net-(IC12-VB)") (class "Default")
      (node (ref "IC12") (pin "6") (pinfunction "VB_6") (pintype "bidirectional"))
      (node (ref "R28") (pin "1") (pinfunction "1_1") (pintype "passive"))
    )
    (net (code "153") (name "Net-(IC13A-NRST)") (class "Default")
      (node (ref "C178") (pin "1") (pinfunction "1_1") (pintype "passive"))
      (node (ref "IC13") (pin "7") (pinfunction "NRST_7") (pintype "bidirectional"))
      (node (ref "R72") (pin "1") (pinfunction "1_1") (pintype "passive"))
      (node (ref "SWD") (pin "5") (pinfunction "5_5") (pintype "passive"))
    )
    (net (code "154") (name "Net-(IC13A-PA0-WKUP)") (class "Default")
      (node (ref "C181") (pin "1") (pinfunction "1_1") (pintype "passive"))
      (node (ref "IC13") (pin "10") (pinfunction "PA0-WKUP_10") (pintype "bidirectional"))
      (node (ref "R74") (pin "2") (pinfunction "2_2") (pintype "passive"))
    )
    (net (code "155") (name "Net-(IC13A-PA1)") (class "Default")
      (node (ref "C183") (pin "1") (pinfunction "1_1") (pintype "passive"))
      (node (ref "IC13") (pin "11") (pinfunction "PA1_11") (pintype "bidirectional"))
      (node (ref "R77") (pin "2") (pinfunction "2_2") (pintype "passive"))
    )
    (net (code "156") (name "Net-(IC13A-PA8)") (class "Default")
      (node (ref "IC13") (pin "29") (pinfunction "PA8_29") (pintype "bidirectional"))
      (node (ref "U1") (pin "P24") (pinfunction "IO_L41P_GCLK27_3_P24") (pintype "bidirectional"))
    )
    (net (code "157") (name "Net-(IC13A-PA9)") (class "Default")
      (node (ref "IC13") (pin "30") (pinfunction "PA9_30") (pintype "bidirectional"))
      (node (ref "UART") (pin "3") (pinfunction "3_3") (pintype "passive"))
    )
    (net (code "158") (name "Net-(IC13A-PA10)") (class "Default")
      (node (ref "IC13") (pin "31") (pinfunction "PA10_31") (pintype "bidirectional"))
      (node (ref "UART") (pin "1") (pinfunction "1_1") (pintype "passive"))
    )
    (net (code "159") (name "Net-(IC13A-PA13)") (class "Default")
      (node (ref "IC13") (pin "34") (pinfunction "PA13_34") (pintype "bidirectional"))
      (node (ref "SWD") (pin "4") (pinfunction "4_4") (pintype "passive"))
    )
    (net (code "160") (name "Net-(IC13A-PA14)") (class "Default")
      (node (ref "IC13") (pin "37") (pinfunction "PA14_37") (pintype "bidirectional"))
      (node (ref "SWD") (pin "2") (pinfunction "2_2") (pintype "passive"))
    )
    (net (code "161") (name "Net-(IC13A-PB4)") (class "Default")
      (node (ref "IC13") (pin "40") (pinfunction "PB4_40") (pintype "bidirectional"))
      (node (ref "U1") (pin "P16") (pinfunction "IO_L43N_GCLK22_IRDY2_3_P16") (pintype "bidirectional"))
    )
    (net (code "162") (name "Net-(IC13A-PB12)") (class "Default")
      (node (ref "IC13") (pin "25") (pinfunction "PB12_25") (pintype "bidirectional"))
      (node (ref "SV2") (pin "2") (pinfunction "2_2") (pintype "passive"))
    )
    (net (code "163") (name "Net-(IC13A-PB13)") (class "Default")
      (node (ref "IC13") (pin "26") (pinfunction "PB13_26") (pintype "bidirectional"))
      (node (ref "SV2") (pin "4") (pinfunction "4_4") (pintype "passive"))
      (node (ref "U1") (pin "P21") (pinfunction "IO_L42N_GCLK24_3_P21") (pintype "bidirectional"))
    )
    (net (code "164") (name "Net-(IC13A-PB14)") (class "Default")
      (node (ref "IC13") (pin "27") (pinfunction "PB14_27") (pintype "bidirectional"))
      (node (ref "SV2") (pin "6") (pinfunction "6_6") (pintype "passive"))
      (node (ref "U1") (pin "P32") (pinfunction "IO_L2N_3_P32") (pintype "bidirectional"))
    )
    (net (code "165") (name "Net-(IC13A-PB15)") (class "Default")
      (node (ref "IC13") (pin "28") (pinfunction "PB15_28") (pintype "bidirectional"))
      (node (ref "SV2") (pin "8") (pinfunction "8_8") (pintype "passive"))
      (node (ref "U1") (pin "P33") (pinfunction "IO_L2P_3_P33") (pintype "bidirectional"))
    )
    (net (code "166") (name "Net-(IC14-IN+)") (class "Default")
      (node (ref "IC14") (pin "3") (pinfunction "IN+_3") (pintype "bidirectional"))
      (node (ref "L55") (pin "1") (pinfunction "1_1") (pintype "passive"))
    )
    (net (code "167") (name "Net-(IC14-IN-)") (class "Default")
      (node (ref "IC14") (pin "4") (pinfunction "IN-_4") (pintype "bidirectional"))
      (node (ref "L54") (pin "1") (pinfunction "1_1") (pintype "passive"))
    )
    (net (code "168") (name "Net-(IC14-LO+)") (class "Default")
      (node (ref "C109") (pin "1") (pinfunction "1_1") (pintype "passive"))
      (node (ref "IC14") (pin "8") (pinfunction "LO+_8") (pintype "bidirectional"))
      (node (ref "L52") (pin "1") (pinfunction "1_1") (pintype "passive"))
    )
    (net (code "169") (name "Net-(IC14-LO-)") (class "Default")
      (node (ref "C109") (pin "2") (pinfunction "2_2") (pintype "passive"))
      (node (ref "IC14") (pin "1") (pinfunction "LO-_1") (pintype "bidirectional"))
      (node (ref "L53") (pin "1") (pinfunction "1_1") (pintype "passive"))
    )
    (net (code "170") (name "Net-(IC14-OUT+)") (class "Default")
      (node (ref "C122") (pin "1") (pinfunction "1_1") (pintype "passive"))
      (node (ref "IC14") (pin "6") (pinfunction "OUT+_6") (pintype "bidirectional"))
      (node (ref "R37") (pin "1") (pinfunction "1_1") (pintype "passive"))
    )
    (net (code "171") (name "Net-(IC14-OUT-)") (class "Default")
      (node (ref "C123") (pin "2") (pinfunction "2_2") (pintype "passive"))
      (node (ref "IC14") (pin "5") (pinfunction "OUT-_5") (pintype "bidirectional"))
      (node (ref "R38") (pin "1") (pinfunction "1_1") (pintype "passive"))
    )
    (net (code "172") (name "Net-(IC14-VCC)") (class "Default")
      (node (ref "C116") (pin "1") (pinfunction "1_1") (pintype "passive"))
      (node (ref "C118") (pin "1") (pinfunction "1_1") (pintype "passive"))
      (node (ref "IC14") (pin "7") (pinfunction "VCC_7") (pintype "bidirectional"))
      (node (ref "IC19") (pin "5") (pinfunction "VOUT_5") (pintype "power_in"))
      (node (ref "R37") (pin "2") (pinfunction "2_2") (pintype "passive"))
      (node (ref "R38") (pin "2") (pinfunction "2_2") (pintype "passive"))
    )
    (net (code "173") (name "Net-(IC15-AVDD)") (class "Default")
      (node (ref "C105") (pin "1") (pinfunction "1_1") (pintype "passive"))
      (node (ref "C111") (pin "1") (pinfunction "1_1") (pintype "passive"))
      (node (ref "C113") (pin "1") (pinfunction "1_1") (pintype "passive"))
      (node (ref "C114") (pin "1") (pinfunction "1_1") (pintype "passive"))
      (node (ref "IC15") (pin "2") (pinfunction "AVDD_2") (pintype "bidirectional"))
      (node (ref "IC15") (pin "21") (pinfunction "DVDD_21") (pintype "bidirectional"))
      (node (ref "IC15") (pin "6") (pinfunction "VVCO_6") (pintype "bidirectional"))
      (node (ref "IC18") (pin "5") (pinfunction "VOUT_5") (pintype "power_in"))
      (node (ref "L50") (pin "1") (pinfunction "1_1") (pintype "passive"))
      (node (ref "L51") (pin "1") (pinfunction "1_1") (pintype "passive"))
      (node (ref "Q6") (pin "2") (pinfunction "S_2") (pintype "passive"))
      (node (ref "R73") (pin "2") (pinfunction "2_2") (pintype "passive"))
    )
    (net (code "174") (name "Net-(IC15-CC)") (class "Default")
      (node (ref "C101") (pin "1") (pinfunction "1_1") (pintype "passive"))
      (node (ref "IC15") (pin "12") (pinfunction "CC_12") (pintype "bidirectional"))
    )
    (net (code "175") (name "Net-(IC15-CN)") (class "Default")
      (node (ref "C105") (pin "2") (pinfunction "2_2") (pintype "passive"))
      (node (ref "IC15") (pin "14") (pinfunction "CN_14") (pintype "bidirectional"))
    )
    (net (code "176") (name "Net-(IC15-CP)") (class "Default")
      (node (ref "C103") (pin "1") (pinfunction "1_1") (pintype "passive"))
      (node (ref "IC15") (pin "24") (pinfunction "CP_24") (pintype "bidirectional"))
      (node (ref "R27") (pin "1") (pinfunction "1_1") (pintype "passive"))
      (node (ref "R29") (pin "1") (pinfunction "1_1") (pintype "passive"))
    )
    (net (code "177") (name "Net-(IC15-REFIN)") (class "Default")
      (node (ref "C115") (pin "1") (pinfunction "1_1") (pintype "passive"))
      (node (ref "IC15") (pin "16") (pinfunction "REFIN_16") (pintype "bidirectional"))
    )
    (net (code "178") (name "Net-(IC15-RFOUTA)") (class "Default")
      (node (ref "C107") (pin "2") (pinfunction "2_2") (pintype "passive"))
      (node (ref "IC15") (pin "4") (pinfunction "RFOUTA_4") (pintype "bidirectional"))
      (node (ref "L51") (pin "2") (pinfunction "2_2") (pintype "passive"))
    )
    (net (code "179") (name "Net-(IC15-RFOUTB)") (class "Default")
      (node (ref "C106") (pin "1") (pinfunction "1_1") (pintype "passive"))
      (node (ref "IC15") (pin "5") (pinfunction "RFOUTB_5") (pintype "bidirectional"))
      (node (ref "L50") (pin "2") (pinfunction "2_2") (pintype "passive"))
    )
    (net (code "180") (name "Net-(IC15-RSET)") (class "Default")
      (node (ref "IC15") (pin "13") (pinfunction "RSET_13") (pintype "bidirectional"))
      (node (ref "R30") (pin "2") (pinfunction "2_2") (pintype "passive"))
    )
    (net (code "181") (name "Net-(IC15-VTUNE)") (class "Default")
      (node (ref "C104") (pin "1") (pinfunction "1_1") (pintype "passive"))
      (node (ref "IC15") (pin "7") (pinfunction "VTUNE_7") (pintype "bidirectional"))
      (node (ref "R27") (pin "2") (pinfunction "2_2") (pintype "passive"))
    )
    (net (code "182") (name "Net-(IC16-RF1)") (class "Default")
      (node (ref "IC16") (pin "5") (pinfunction "RF1_5") (pintype "bidirectional"))
      (node (ref "IC17") (pin "8") (pinfunction "RF2_8") (pintype "bidirectional"))
    )
    (net (code "183") (name "Net-(IC16-RF2)") (class "Default")
      (node (ref "IC16") (pin "8") (pinfunction "RF2_8") (pintype "bidirectional"))
      (node (ref "R34") (pin "2") (pinfunction "2_2") (pintype "passive"))
      (node (ref "R35") (pin "1") (pinfunction "1_1") (pintype "passive"))
    )
    (net (code "184") (name "Net-(IC16-RFC)") (class "Default")
      (node (ref "C119") (pin "1") (pinfunction "1_1") (pintype "passive"))
      (node (ref "IC16") (pin "3") (pinfunction "RFC_3") (pintype "bidirectional"))
    )
    (net (code "185") (name "Net-(IC17-RF1)") (class "Default")
      (node (ref "C127") (pin "2") (pinfunction "2_2") (pintype "passive"))
      (node (ref "IC17") (pin "5") (pinfunction "RF1_5") (pintype "bidirectional"))
      (node (ref "L60") (pin "1") (pinfunction "1_1") (pintype "passive"))
    )
    (net (code "186") (name "Net-(IC20-+IN)") (class "Default")
      (node (ref "C122") (pin "2") (pinfunction "2_2") (pintype "passive"))
      (node (ref "IC20") (pin "3") (pinfunction "+IN_3") (pintype "input"))
      (node (ref "R40") (pin "2") (pinfunction "2_2") (pintype "passive"))
    )
    (net (code "187") (name "Net-(IC20--IN)") (class "Default")
      (node (ref "C123") (pin "1") (pinfunction "1_1") (pintype "passive"))
      (node (ref "IC20") (pin "4") (pinfunction "-IN_4") (pintype "input"))
      (node (ref "R39") (pin "2") (pinfunction "2_2") (pintype "passive"))
    )
    (net (code "188") (name "Net-(IC20-OUT)") (class "Default")
      (node (ref "C125") (pin "2") (pinfunction "2_2") (pintype "passive"))
      (node (ref "IC20") (pin "1") (pinfunction "OUT_1") (pintype "output"))
      (node (ref "R39") (pin "1") (pinfunction "1_1") (pintype "passive"))
    )
    (net (code "189") (name "Net-(IC20-V+)") (class "Default")
      (node (ref "C121") (pin "1") (pinfunction "1_1") (pintype "passive"))
      (node (ref "IC20") (pin "5") (pinfunction "V+_5") (pintype "power_in"))
      (node (ref "L56") (pin "1") (pinfunction "1_1") (pintype "passive"))
    )
    (net (code "190") (name "Net-(IC21-GND)") (class "Default")
      (node (ref "C131") (pin "1") (pinfunction "1_1") (pintype "passive"))
      (node (ref "IC21") (pin "2") (pinfunction "GND_2") (pintype "bidirectional"))
    )
    (net (code "191") (name "Net-(IC21-RF1)") (class "Default")
      (node (ref "C130") (pin "1") (pinfunction "1_1") (pintype "passive"))
      (node (ref "IC21") (pin "1") (pinfunction "RF1_1") (pintype "bidirectional"))
    )
    (net (code "192") (name "Net-(IC21-RF2)") (class "Default")
      (node (ref "C132") (pin "2") (pinfunction "2_2") (pintype "passive"))
      (node (ref "IC21") (pin "3") (pinfunction "RF2_3") (pintype "bidirectional"))
    )
    (net (code "193") (name "Net-(IC21-V1)") (class "Default")
      (node (ref "IC21") (pin "4") (pinfunction "V1_4") (pintype "bidirectional"))
      (node (ref "Q3") (pin "3") (pinfunction "D_3") (pintype "passive"))
      (node (ref "R44") (pin "2") (pinfunction "2_2") (pintype "passive"))
    )
    (net (code "194") (name "Net-(IC22-GND)") (class "Default")
      (node (ref "C133") (pin "1") (pinfunction "1_1") (pintype "passive"))
      (node (ref "IC22") (pin "2") (pinfunction "GND_2") (pintype "bidirectional"))
    )
    (net (code "195") (name "Net-(IC22-RF1)") (class "Default")
      (node (ref "C132") (pin "1") (pinfunction "1_1") (pintype "passive"))
      (node (ref "IC22") (pin "1") (pinfunction "RF1_1") (pintype "bidirectional"))
    )
    (net (code "196") (name "Net-(IC22-RF2)") (class "Default")
      (node (ref "C134") (pin "2") (pinfunction "2_2") (pintype "passive"))
      (node (ref "IC22") (pin "3") (pinfunction "RF2_3") (pintype "bidirectional"))
    )
    (net (code "197") (name "Net-(IC22-V1)") (class "Default")
      (node (ref "IC22") (pin "4") (pinfunction "V1_4") (pintype "bidirectional"))
      (node (ref "Q4") (pin "3") (pinfunction "D_3") (pintype "passive"))
      (node (ref "R45") (pin "2") (pinfunction "2_2") (pintype "passive"))
    )
    (net (code "198") (name "Net-(IC23-GND)") (class "Default")
      (node (ref "C135") (pin "1") (pinfunction "1_1") (pintype "passive"))
      (node (ref "IC23") (pin "2") (pinfunction "GND_2") (pintype "bidirectional"))
    )
    (net (code "199") (name "Net-(IC23-RF1)") (class "Default")
      (node (ref "C134") (pin "1") (pinfunction "1_1") (pintype "passive"))
      (node (ref "IC23") (pin "1") (pinfunction "RF1_1") (pintype "bidirectional"))
    )
    (net (code "200") (name "Net-(IC23-RF2)") (class "Default")
      (node (ref "C138") (pin "2") (pinfunction "2_2") (pintype "passive"))
      (node (ref "IC23") (pin "3") (pinfunction "RF2_3") (pintype "bidirectional"))
    )
    (net (code "201") (name "Net-(IC23-V1)") (class "Default")
      (node (ref "IC23") (pin "4") (pinfunction "V1_4") (pintype "bidirectional"))
      (node (ref "Q5") (pin "3") (pinfunction "D_3") (pintype "passive"))
      (node (ref "R46") (pin "2") (pinfunction "2_2") (pintype "passive"))
    )
    (net (code "202") (name "Net-(IC24-RFIN)") (class "Default")
      (node (ref "C136") (pin "1") (pinfunction "1_1") (pintype "passive"))
      (node (ref "IC24") (pin "3") (pinfunction "RFIN_3") (pintype "bidirectional"))
    )
    (net (code "203") (name "Net-(IC24-RFOUT)") (class "Default")
      (node (ref "C119") (pin "2") (pinfunction "2_2") (pintype "passive"))
      (node (ref "IC24") (pin "10") (pinfunction "RFOUT_10") (pintype "bidirectional"))
    )
    (net (code "204") (name "Net-(IC24-SLOPE)") (class "Default")
      (node (ref "IC24") (pin "16") (pinfunction "SLOPE_16") (pintype "bidirectional"))
      (node (ref "R64") (pin "2") (pinfunction "2_2") (pintype "passive"))
    )
    (net (code "205") (name "Net-(IC24-VDD)") (class "Default")
      (node (ref "C137") (pin "1") (pinfunction "1_1") (pintype "passive"))
      (node (ref "IC24") (pin "15") (pinfunction "VDD_15") (pintype "bidirectional"))
      (node (ref "L57") (pin "1") (pinfunction "1_1") (pintype "passive"))
    )
    (net (code "206") (name "Net-(IC25-IN)") (class "Default")
      (node (ref "C138") (pin "1") (pinfunction "1_1") (pintype "passive"))
      (node (ref "IC25") (pin "1") (pinfunction "IN_1") (pintype "bidirectional"))
    )
    (net (code "207") (name "Net-(IC25-OUT)") (class "Default")
      (node (ref "C139") (pin "2") (pinfunction "2_2") (pintype "passive"))
      (node (ref "IC25") (pin "3") (pinfunction "OUT_3") (pintype "bidirectional"))
      (node (ref "L61") (pin "2") (pinfunction "2_2") (pintype "passive"))
    )
    (net (code "208") (name "Net-(IC26-IN)") (class "Default")
      (node (ref "C139") (pin "1") (pinfunction "1_1") (pintype "passive"))
      (node (ref "IC26") (pin "1") (pinfunction "IN_1") (pintype "bidirectional"))
    )
    (net (code "209") (name "Net-(IC26-OUT)") (class "Default")
      (node (ref "C144") (pin "2") (pinfunction "2_2") (pintype "passive"))
      (node (ref "IC26") (pin "3") (pinfunction "OUT_3") (pintype "bidirectional"))
      (node (ref "L64") (pin "2") (pinfunction "2_2") (pintype "passive"))
    )
    (net (code "210") (name "Net-(IC27-COFSA)") (class "Default")
      (node (ref "C151") (pin "2") (pinfunction "2_2") (pintype "passive"))
      (node (ref "IC27") (pin "9") (pinfunction "COFSA_9") (pintype "bidirectional"))
    )
    (net (code "211") (name "Net-(IC27-COFSB)") (class "Default")
      (node (ref "C151") (pin "1") (pinfunction "1_1") (pintype "passive"))
      (node (ref "IC27") (pin "10") (pinfunction "COFSB_10") (pintype "bidirectional"))
    )
    (net (code "212") (name "Net-(IC27-INN)") (class "Default")
      (node (ref "C150") (pin "2") (pinfunction "2_2") (pintype "passive"))
      (node (ref "IC27") (pin "4") (pinfunction "INN_4") (pintype "bidirectional"))
    )
    (net (code "213") (name "Net-(IC27-INP)") (class "Default")
      (node (ref "C149") (pin "2") (pinfunction "2_2") (pintype "passive"))
      (node (ref "IC27") (pin "3") (pinfunction "INP_3") (pintype "bidirectional"))
    )
    (net (code "214") (name "Net-(IC27-RMSOUT)") (class "Default")
      (node (ref "IC27") (pin "15") (pinfunction "RMSOUT_15") (pintype "bidirectional"))
      (node (ref "R60") (pin "1") (pinfunction "1_1") (pintype "passive"))
      (node (ref "R62") (pin "1") (pinfunction "1_1") (pintype "passive"))
    )
    (net (code "215") (name "Net-(IC28-VA)") (class "Default")
      (node (ref "IC28") (pin "8") (pinfunction "VA_8") (pintype "bidirectional"))
      (node (ref "R61") (pin "2") (pinfunction "2_2") (pintype "passive"))
    )
    (net (code "216") (name "Net-(IC28-VB)") (class "Default")
      (node (ref "IC28") (pin "6") (pinfunction "VB_6") (pintype "bidirectional"))
      (node (ref "R65") (pin "2") (pinfunction "2_2") (pintype "passive"))
    )
    (net (code "217") (name "Net-(IC28-VDD)") (class "Default")
      (node (ref "C152") (pin "1") (pinfunction "1_1") (pintype "passive"))
      (node (ref "C17") (pin "1") (pinfunction "1_1") (pintype "passive"))
      (node (ref "IC28") (pin "1") (pinfunction "VDD_1") (pintype "bidirectional"))
      (node (ref "IC29") (pin "5") (pinfunction "VOUT_5") (pintype "power_in"))
    )
    (net (code "218") (name "Net-(IC31-RF1)") (class "Default")
      (node (ref "C93") (pin "1") (pinfunction "1_1") (pintype "passive"))
      (node (ref "IC31") (pin "14") (pinfunction "RF1_14") (pintype "bidirectional"))
      (node (ref "L43") (pin "2") (pinfunction "2_2") (pintype "passive"))
    )
    (net (code "219") (name "Net-(IC31-RF2)") (class "Default")
      (node (ref "C85") (pin "1") (pinfunction "1_1") (pintype "passive"))
      (node (ref "IC31") (pin "11") (pinfunction "RF2_11") (pintype "bidirectional"))
      (node (ref "L36") (pin "2") (pinfunction "2_2") (pintype "passive"))
    )
    (net (code "220") (name "Net-(IC31-RF3)") (class "Default")
      (node (ref "C77") (pin "1") (pinfunction "1_1") (pintype "passive"))
      (node (ref "IC31") (pin "8") (pinfunction "RF3_8") (pintype "bidirectional"))
      (node (ref "L29") (pin "2") (pinfunction "2_2") (pintype "passive"))
    )
    (net (code "221") (name "Net-(IC31-RF4)") (class "Default")
      (node (ref "C69") (pin "1") (pinfunction "1_1") (pintype "passive"))
      (node (ref "IC31") (pin "5") (pinfunction "RF4_5") (pintype "bidirectional"))
      (node (ref "L22") (pin "2") (pinfunction "2_2") (pintype "passive"))
    )
    (net (code "222") (name "Net-(IC31-RF5)") (class "Default")
      (node (ref "C61") (pin "1") (pinfunction "1_1") (pintype "passive"))
      (node (ref "IC31") (pin "2") (pinfunction "RF5_2") (pintype "bidirectional"))
      (node (ref "L15") (pin "2") (pinfunction "2_2") (pintype "passive"))
    )
    (net (code "223") (name "Net-(IC31-RF6)") (class "Default")
      (node (ref "IC31") (pin "24") (pinfunction "RF6_24") (pintype "bidirectional"))
      (node (ref "IC32") (pin "14") (pinfunction "RF1_14") (pintype "bidirectional"))
    )
    (net (code "224") (name "Net-(IC31-VDD)") (class "Default")
      (node (ref "C59") (pin "1") (pinfunction "1_1") (pintype "passive"))
      (node (ref "IC31") (pin "16") (pinfunction "VDD_16") (pintype "bidirectional"))
      (node (ref "L68") (pin "2") (pinfunction "2_2") (pintype "passive"))
    )
    (net (code "225") (name "Net-(IC32-RF2)") (class "Default")
      (node (ref "C62") (pin "1") (pinfunction "1_1") (pintype "passive"))
      (node (ref "IC32") (pin "11") (pinfunction "RF2_11") (pintype "bidirectional"))
      (node (ref "L21") (pin "1") (pinfunction "1_1") (pintype "passive"))
    )
    (net (code "226") (name "Net-(IC32-RF3)") (class "Default")
      (node (ref "C70") (pin "1") (pinfunction "1_1") (pintype "passive"))
      (node (ref "IC32") (pin "8") (pinfunction "RF3_8") (pintype "bidirectional"))
      (node (ref "L28") (pin "1") (pinfunction "1_1") (pintype "passive"))
    )
    (net (code "227") (name "Net-(IC32-RF4)") (class "Default")
      (node (ref "C78") (pin "1") (pinfunction "1_1") (pintype "passive"))
      (node (ref "IC32") (pin "5") (pinfunction "RF4_5") (pintype "bidirectional"))
      (node (ref "L35") (pin "1") (pinfunction "1_1") (pintype "passive"))
    )
    (net (code "228") (name "Net-(IC32-RF5)") (class "Default")
      (node (ref "C86") (pin "1") (pinfunction "1_1") (pintype "passive"))
      (node (ref "IC32") (pin "2") (pinfunction "RF5_2") (pintype "bidirectional"))
      (node (ref "L42") (pin "1") (pinfunction "1_1") (pintype "passive"))
    )
    (net (code "229") (name "Net-(IC32-RF6)") (class "Default")
      (node (ref "C94") (pin "1") (pinfunction "1_1") (pintype "passive"))
      (node (ref "IC32") (pin "24") (pinfunction "RF6_24") (pintype "bidirectional"))
      (node (ref "L49") (pin "1") (pinfunction "1_1") (pintype "passive"))
    )
    (net (code "230") (name "Net-(IC32-VDD)") (class "Default")
      (node (ref "C60") (pin "1") (pinfunction "1_1") (pintype "passive"))
      (node (ref "IC32") (pin "16") (pinfunction "VDD_16") (pintype "bidirectional"))
      (node (ref "L69") (pin "2") (pinfunction "2_2") (pintype "passive"))
    )
    (net (code "231") (name "Net-(J1-ANT)") (class "Default")
      (node (ref "C184") (pin "2") (pinfunction "2_2") (pintype "passive"))
      (node (ref "J1") (pin "SIG") (pinfunction "ANT_SIG") (pintype "bidirectional"))
    )
    (net (code "232") (name "Net-(L61-Pad1)") (class "Default")
      (node (ref "L61") (pin "1") (pinfunction "1_1") (pintype "passive"))
      (node (ref "L62") (pin "2") (pinfunction "2_2") (pintype "passive"))
    )
    (net (code "233") (name "Net-(L63-1)") (class "Default")
      (node (ref "C140") (pin "1") (pinfunction "1_1") (pintype "passive"))
      (node (ref "C141") (pin "1") (pinfunction "1_1") (pintype "passive"))
      (node (ref "C142") (pin "1") (pinfunction "1_1") (pintype "passive"))
      (node (ref "L63") (pin "P$1") (pinfunction "1_P$1") (pintype "passive"))
      (node (ref "R47") (pin "1") (pinfunction "1_1") (pintype "passive"))
    )
    (net (code "234") (name "Net-(L63-2)") (class "Default")
      (node (ref "L62") (pin "1") (pinfunction "1_1") (pintype "passive"))
      (node (ref "L63") (pin "P$3") (pinfunction "2_P$3") (pintype "passive"))
    )
    (net (code "235") (name "Net-(L64-Pad1)") (class "Default")
      (node (ref "L64") (pin "1") (pinfunction "1_1") (pintype "passive"))
      (node (ref "L65") (pin "2") (pinfunction "2_2") (pintype "passive"))
    )
    (net (code "236") (name "Net-(L66-1)") (class "Default")
      (node (ref "C145") (pin "1") (pinfunction "1_1") (pintype "passive"))
      (node (ref "C146") (pin "1") (pinfunction "1_1") (pintype "passive"))
      (node (ref "C147") (pin "1") (pinfunction "1_1") (pintype "passive"))
      (node (ref "L66") (pin "P$1") (pinfunction "1_P$1") (pintype "passive"))
      (node (ref "R48") (pin "1") (pinfunction "1_1") (pintype "passive"))
    )
    (net (code "237") (name "Net-(L66-2)") (class "Default")
      (node (ref "L65") (pin "1") (pinfunction "1_1") (pintype "passive"))
      (node (ref "L66") (pin "P$3") (pinfunction "2_P$3") (pintype "passive"))
    )
    (net (code "238") (name "Net-(LED1-PadC)") (class "Default")
      (node (ref "LED1") (pin "C") (pinfunction "C_C") (pintype "passive"))
      (node (ref "R78") (pin "2") (pinfunction "2_2") (pintype "passive"))
    )
    (net (code "239") (name "Net-(LED2-PadC)") (class "Default")
      (node (ref "LED2") (pin "C") (pinfunction "C_C") (pintype "passive"))
      (node (ref "R79") (pin "2") (pinfunction "2_2") (pintype "passive"))
    )
    (net (code "240") (name "Net-(LED3-PadC)") (class "Default")
      (node (ref "LED3") (pin "C") (pinfunction "C_C") (pintype "passive"))
      (node (ref "R80") (pin "2") (pinfunction "2_2") (pintype "passive"))
    )
    (net (code "241") (name "Net-(LED4-PadC)") (class "Default")
      (node (ref "LED4") (pin "C") (pinfunction "C_C") (pintype "passive"))
      (node (ref "R81") (pin "2") (pinfunction "2_2") (pintype "passive"))
    )
    (net (code "242") (name "Net-(LED5-PadC)") (class "Default")
      (node (ref "LED5") (pin "C") (pinfunction "C_C") (pintype "passive"))
      (node (ref "R82") (pin "2") (pinfunction "2_2") (pintype "passive"))
    )
    (net (code "243") (name "Net-(Q6-D)") (class "Default")
      (node (ref "C179") (pin "1") (pinfunction "1_1") (pintype "passive"))
      (node (ref "Q6") (pin "3") (pinfunction "D_3") (pintype "passive"))
      (node (ref "TC1") (pin "4") (pinfunction "VCC_4") (pintype "power_in"))
    )
    (net (code "244") (name "Net-(R49-Pad1)") (class "Default")
      (node (ref "R49") (pin "1") (pinfunction "1_1") (pintype "passive"))
      (node (ref "R50") (pin "2") (pinfunction "2_2") (pintype "passive"))
      (node (ref "R51") (pin "1") (pinfunction "1_1") (pintype "passive"))
    )
    (net (code "245") (name "Net-(U1B-IO_L1N_VREF_1)") (class "Default")
      (node (ref "U1") (pin "P104") (pinfunction "IO_L1N_VREF_1_P104") (pintype "bidirectional"))
      (node (ref "X2") (pin "19") (pinfunction "1_19") (pintype "passive"))
    )
    (net (code "246") (name "Net-(U1B-IO_L1P_1)") (class "Default")
      (node (ref "U1") (pin "P105") (pinfunction "IO_L1P_1_P105") (pintype "bidirectional"))
      (node (ref "X2") (pin "20") (pinfunction "1_20") (pintype "passive"))
    )
    (net (code "247") (name "Net-(U1B-IO_L32N_1)") (class "Default")
      (node (ref "U1") (pin "P101") (pinfunction "IO_L32N_1_P101") (pintype "bidirectional"))
      (node (ref "X2") (pin "16") (pinfunction "1_16") (pintype "passive"))
    )
    (net (code "248") (name "Net-(U1B-IO_L32P_1)") (class "Default")
      (node (ref "U1") (pin "P102") (pinfunction "IO_L32P_1_P102") (pintype "bidirectional"))
      (node (ref "X2") (pin "17") (pinfunction "1_17") (pintype "passive"))
    )
    (net (code "249") (name "Net-(U1B-IO_L33N_1)") (class "Default")
      (node (ref "U1") (pin "P99") (pinfunction "IO_L33N_1_P99") (pintype "bidirectional"))
      (node (ref "X2") (pin "14") (pinfunction "1_14") (pintype "passive"))
    )
    (net (code "250") (name "Net-(U1B-IO_L33P_1)") (class "Default")
      (node (ref "U1") (pin "P100") (pinfunction "IO_L33P_1_P100") (pintype "bidirectional"))
      (node (ref "X2") (pin "15") (pinfunction "1_15") (pintype "passive"))
    )
    (net (code "251") (name "Net-(U1B-IO_L34N_1)") (class "Default")
      (node (ref "U1") (pin "P97") (pinfunction "IO_L34N_1_P97") (pintype "bidirectional"))
      (node (ref "X2") (pin "12") (pinfunction "1_12") (pintype "passive"))
    )
    (net (code "252") (name "Net-(U1B-IO_L34P_1)") (class "Default")
      (node (ref "U1") (pin "P98") (pinfunction "IO_L34P_1_P98") (pintype "bidirectional"))
      (node (ref "X2") (pin "13") (pinfunction "1_13") (pintype "passive"))
    )
    (net (code "253") (name "Net-(U1B-IO_L40N_GCLK10_1)") (class "Default")
      (node (ref "U1") (pin "P94") (pinfunction "IO_L40N_GCLK10_1_P94") (pintype "bidirectional"))
      (node (ref "X2") (pin "9") (pinfunction "1_9") (pintype "passive"))
    )
    (net (code "254") (name "Net-(U1B-IO_L40P_GCLK11_1)") (class "Default")
      (node (ref "U1") (pin "P95") (pinfunction "IO_L40P_GCLK11_1_P95") (pintype "bidirectional"))
      (node (ref "X2") (pin "10") (pinfunction "1_10") (pintype "passive"))
    )
    (net (code "255") (name "Net-(U1B-IO_L41N_GCLK8_1)") (class "Default")
      (node (ref "U1") (pin "P92") (pinfunction "IO_L41N_GCLK8_1_P92") (pintype "bidirectional"))
      (node (ref "X2") (pin "7") (pinfunction "1_7") (pintype "passive"))
    )
    (net (code "256") (name "Net-(U1B-IO_L41P_GCLK9_IRDY1_1)") (class "Default")
      (node (ref "U1") (pin "P93") (pinfunction "IO_L41P_GCLK9_IRDY1_1_P93") (pintype "bidirectional"))
      (node (ref "X2") (pin "8") (pinfunction "1_8") (pintype "passive"))
    )
    (net (code "257") (name "Net-(U1B-IO_L42N_GCLK6_TRDY1_1)") (class "Default")
      (node (ref "U1") (pin "P87") (pinfunction "IO_L42N_GCLK6_TRDY1_1_P87") (pintype "bidirectional"))
      (node (ref "X2") (pin "2") (pinfunction "1_2") (pintype "passive"))
    )
    (net (code "258") (name "Net-(U1B-IO_L42P_GCLK7_1)") (class "Default")
      (node (ref "U1") (pin "P88") (pinfunction "IO_L42P_GCLK7_1_P88") (pintype "bidirectional"))
      (node (ref "X2") (pin "3") (pinfunction "1_3") (pintype "passive"))
    )
    (net (code "259") (name "Net-(U1B-IO_L46N_1)") (class "Default")
      (node (ref "LED5") (pin "A") (pinfunction "A_A") (pintype "passive"))
      (node (ref "U1") (pin "P80") (pinfunction "IO_L46N_1_P80") (pintype "bidirectional"))
    )
    (net (code "260") (name "Net-(U1B-IO_L47N_1)") (class "Default")
      (node (ref "LED3") (pin "A") (pinfunction "A_A") (pintype "passive"))
      (node (ref "U1") (pin "P78") (pinfunction "IO_L47N_1_P78") (pintype "bidirectional"))
    )
    (net (code "261") (name "Net-(U1B-IO_L47P_1)") (class "Default")
      (node (ref "LED4") (pin "A") (pinfunction "A_A") (pintype "passive"))
      (node (ref "U1") (pin "P79") (pinfunction "IO_L47P_1_P79") (pintype "bidirectional"))
    )
    (net (code "262") (name "Net-(U1B-IO_L74N_DOUT_BUSY_1)") (class "Default")
      (node (ref "LED1") (pin "A") (pinfunction "A_A") (pintype "passive"))
      (node (ref "U1") (pin "P74") (pinfunction "IO_L74N_DOUT_BUSY_1_P74") (pintype "bidirectional"))
    )
    (net (code "263") (name "Net-(U1B-IO_L74P_AWAKE_1)") (class "Default")
      (node (ref "LED2") (pin "A") (pinfunction "A_A") (pintype "passive"))
      (node (ref "U1") (pin "P75") (pinfunction "IO_L74P_AWAKE_1_P75") (pintype "bidirectional"))
    )
    (net (code "264") (name "Net-(U1C-DONE_2)") (class "Default")
      (node (ref "R70") (pin "1") (pinfunction "1_1") (pintype "passive"))
      (node (ref "U1") (pin "P71") (pinfunction "DONE_2_P71") (pintype "bidirectional"))
    )
    (net (code "265") (name "Net-(U1C-IO_L1P_CCLK_2)") (class "Default")
      (node (ref "U1") (pin "P70") (pinfunction "IO_L1P_CCLK_2_P70") (pintype "bidirectional"))
      (node (ref "U4") (pin "6") (pinfunction "CLK_6") (pintype "input"))
    )
    (net (code "266") (name "Net-(U1C-IO_L3N_MOSI_CSI_B_MISO0_2)") (class "Default")
      (node (ref "U1") (pin "P64") (pinfunction "IO_L3N_MOSI_CSI_B_MISO0_2_P64") (pintype "bidirectional"))
      (node (ref "U4") (pin "5") (pinfunction "DI_5") (pintype "input"))
    )
    (net (code "267") (name "Net-(U1C-IO_L3P_D0_DIN_MISO_MISO1_2)") (class "Default")
      (node (ref "R67") (pin "2") (pinfunction "2_2") (pintype "passive"))
      (node (ref "U1") (pin "P65") (pinfunction "IO_L3P_D0_DIN_MISO_MISO1_2_P65") (pintype "bidirectional"))
    )
    (net (code "268") (name "Net-(U1C-IO_L65N_CSO_B_2)") (class "Default")
      (node (ref "U1") (pin "P38") (pinfunction "IO_L65N_CSO_B_2_P38") (pintype "bidirectional"))
      (node (ref "U4") (pin "1") (pinfunction "~{CS}_1") (pintype "input"))
    )
    (net (code "269") (name "Net-(U1C-IO_L65P_INIT_B_2)") (class "Default")
      (node (ref "R71") (pin "1") (pinfunction "1_1") (pintype "passive"))
      (node (ref "U1") (pin "P39") (pinfunction "IO_L65P_INIT_B_2_P39") (pintype "bidirectional"))
    )
    (net (code "270") (name "Net-(U1C-PROGRAM_B_2)") (class "Default")
      (node (ref "R68") (pin "1") (pinfunction "1_1") (pintype "passive"))
      (node (ref "U1") (pin "P37") (pinfunction "PROGRAM_B_2_P37") (pintype "input"))
    )
    (net (code "271") (name "Net-(U1D-IO_L36P_3)") (class "Default")
      (node (ref "SV2") (pin "10") (pinfunction "10_10") (pintype "passive"))
      (node (ref "U1") (pin "P30") (pinfunction "IO_L36P_3_P30") (pintype "bidirectional"))
    )
    (net (code "272") (name "Net-(U1D-IO_L41N_GCLK26_3)") (class "Default")
      (node (ref "R76") (pin "2") (pinfunction "2_2") (pintype "passive"))
      (node (ref "U1") (pin "P23") (pinfunction "IO_L41N_GCLK26_3_P23") (pintype "bidirectional"))
    )
    (net (code "273") (name "Net-(U1D-IO_L43P_GCLK23_3)") (class "Default")
      (node (ref "C182") (pin "1") (pinfunction "1_1") (pintype "passive"))
      (node (ref "R75") (pin "2") (pinfunction "2_2") (pintype "passive"))
      (node (ref "U1") (pin "P17") (pinfunction "IO_L43P_GCLK23_3_P17") (pintype "bidirectional"))
    )
    (net (code "274") (name "Net-(U1F-TCK)") (class "Default")
      (node (ref "JTAG") (pin "1") (pinfunction "1_1") (pintype "passive"))
      (node (ref "U1") (pin "P109") (pinfunction "TCK_P109") (pintype "input"))
    )
    (net (code "275") (name "Net-(U1F-TDI)") (class "Default")
      (node (ref "JTAG") (pin "9") (pinfunction "9_9") (pintype "passive"))
      (node (ref "U1") (pin "P110") (pinfunction "TDI_P110") (pintype "input"))
    )
    (net (code "276") (name "Net-(U1F-TDO)") (class "Default")
      (node (ref "JTAG") (pin "3") (pinfunction "3_3") (pintype "passive"))
      (node (ref "U1") (pin "P106") (pinfunction "TDO_P106") (pintype "output"))
    )
    (net (code "277") (name "Net-(U1F-TMS)") (class "Default")
      (node (ref "JTAG") (pin "5") (pinfunction "5_5") (pintype "passive"))
      (node (ref "U1") (pin "P107") (pinfunction "TMS_P107") (pintype "input"))
    )
    (net (code "278") (name "Net-(U4-DO)") (class "Default")
      (node (ref "R67") (pin "1") (pinfunction "1_1") (pintype "passive"))
      (node (ref "U4") (pin "2") (pinfunction "DO_2") (pintype "output"))
    )
    (net (code "279") (name "OFFSET_CS") (class "Default")
      (node (ref "IC12") (pin "2") (pinfunction "CS_2") (pintype "bidirectional"))
      (node (ref "IC13") (pin "19") (pinfunction "PB1_19") (pintype "bidirectional"))
    )
    (net (code "280") (name "Q0") (class "Default")
      (node (ref "IC6") (pin "5") (pinfunction "A0_5") (pintype "bidirectional"))
      (node (ref "U1") (pin "P111") (pinfunction "IO_L66N_SCP0_0_P111") (pintype "bidirectional"))
    )
    (net (code "281") (name "Q1") (class "Default")
      (node (ref "IC6") (pin "4") (pinfunction "A1_4") (pintype "bidirectional"))
      (node (ref "U1") (pin "P112") (pinfunction "IO_L66P_SCP1_0_P112") (pintype "bidirectional"))
    )
    (net (code "282") (name "Q2") (class "Default")
      (node (ref "IC6") (pin "3") (pinfunction "A2_3") (pintype "bidirectional"))
      (node (ref "U1") (pin "P114") (pinfunction "IO_L65N_SCP2_0_P114") (pintype "bidirectional"))
    )
    (net (code "283") (name "Q3") (class "Default")
      (node (ref "IC6") (pin "2") (pinfunction "A3_2") (pintype "bidirectional"))
      (node (ref "U1") (pin "P115") (pinfunction "IO_L65P_SCP3_0_P115") (pintype "bidirectional"))
    )
    (net (code "284") (name "Q4") (class "Default")
      (node (ref "IC6") (pin "1") (pinfunction "A4_1") (pintype "bidirectional"))
      (node (ref "U1") (pin "P116") (pinfunction "IO_L64N_SCP4_0_P116") (pintype "bidirectional"))
    )
    (net (code "285") (name "Q5") (class "Default")
      (node (ref "IC6") (pin "68") (pinfunction "A5_68") (pintype "bidirectional"))
      (node (ref "U1") (pin "P117") (pinfunction "IO_L64P_SCP5_0_P117") (pintype "bidirectional"))
    )
    (net (code "286") (name "Q6") (class "Default")
      (node (ref "IC6") (pin "67") (pinfunction "A6_67") (pintype "bidirectional"))
      (node (ref "U1") (pin "P118") (pinfunction "IO_L63N_SCP6_0_P118") (pintype "bidirectional"))
    )
    (net (code "287") (name "Q7") (class "Default")
      (node (ref "IC6") (pin "66") (pinfunction "A7_66") (pintype "bidirectional"))
      (node (ref "U1") (pin "P119") (pinfunction "IO_L63P_SCP7_0_P119") (pintype "bidirectional"))
    )
    (net (code "288") (name "Q8") (class "Default")
      (node (ref "IC6") (pin "65") (pinfunction "A8_65") (pintype "bidirectional"))
      (node (ref "U1") (pin "P120") (pinfunction "IO_L62N_VREF_0_P120") (pintype "bidirectional"))
    )
    (net (code "289") (name "Q9") (class "Default")
      (node (ref "IC6") (pin "64") (pinfunction "A9_64") (pintype "bidirectional"))
      (node (ref "U1") (pin "P121") (pinfunction "IO_L62P_0_P121") (pintype "bidirectional"))
    )
    (net (code "290") (name "Q10") (class "Default")
      (node (ref "IC6") (pin "63") (pinfunction "A10_63") (pintype "bidirectional"))
      (node (ref "U1") (pin "P123") (pinfunction "IO_L37N_GCLK12_0_P123") (pintype "bidirectional"))
    )
    (net (code "291") (name "Q11") (class "Default")
      (node (ref "IC6") (pin "62") (pinfunction "A11_62") (pintype "bidirectional"))
      (node (ref "U1") (pin "P124") (pinfunction "IO_L37P_GCLK13_0_P124") (pintype "bidirectional"))
    )
    (net (code "292") (name "RMSOUT") (class "Default")
      (node (ref "C155") (pin "1") (pinfunction "1_1") (pintype "passive"))
      (node (ref "IC27") (pin "14") (pinfunction "VSET_14") (pintype "bidirectional"))
      (node (ref "R59") (pin "1") (pinfunction "1_1") (pintype "passive"))
      (node (ref "R60") (pin "2") (pinfunction "2_2") (pintype "passive"))
      (node (ref "R61") (pin "1") (pinfunction "1_1") (pintype "passive"))
      (node (ref "R77") (pin "1") (pinfunction "1_1") (pintype "passive"))
    )
    (net (code "293") (name "SELIQ") (class "Default")
      (node (ref "IC6") (pin "44") (pinfunction "SELIQ_44") (pintype "bidirectional"))
      (node (ref "U1") (pin "P10") (pinfunction "IO_L50P_3_P10") (pintype "bidirectional"))
    )
    (net (code "294") (name "SPI_CLK") (class "Default")
      (node (ref "IC12") (pin "3") (pinfunction "SCK_3") (pintype "bidirectional"))
      (node (ref "IC13") (pin "41") (pinfunction "PB5_41") (pintype "bidirectional"))
      (node (ref "IC15") (pin "17") (pinfunction "CLK_17") (pintype "bidirectional"))
      (node (ref "IC2") (pin "1") (pinfunction "CLK_1") (pintype "input"))
      (node (ref "IC28") (pin "3") (pinfunction "SCK_3") (pintype "bidirectional"))
      (node (ref "R75") (pin "1") (pinfunction "1_1") (pintype "passive"))
    )
    (net (code "295") (name "SPI_MOSI") (class "Default")
      (node (ref "IC12") (pin "4") (pinfunction "SDI_4") (pintype "bidirectional"))
      (node (ref "IC13") (pin "39") (pinfunction "PB3_39") (pintype "bidirectional"))
      (node (ref "IC15") (pin "18") (pinfunction "DATA_18") (pintype "bidirectional"))
      (node (ref "IC2") (pin "2") (pinfunction "DATA_2") (pintype "input"))
      (node (ref "IC28") (pin "4") (pinfunction "SDI_4") (pintype "bidirectional"))
      (node (ref "U1") (pin "P15") (pinfunction "IO_L44P_GCLK21_3_P15") (pintype "bidirectional"))
    )
    (net (code "296") (name "SW1_CTL1") (class "Default")
      (node (ref "IC31") (pin "17") (pinfunction "V1_17") (pintype "bidirectional"))
      (node (ref "U1") (pin "P1") (pinfunction "IO_L83N_VREF_3_P1") (pintype "bidirectional"))
    )
    (net (code "297") (name "SW1_CTL2") (class "Default")
      (node (ref "IC31") (pin "18") (pinfunction "V2_18") (pintype "bidirectional"))
      (node (ref "U1") (pin "P2") (pinfunction "IO_L83P_3_P2") (pintype "bidirectional"))
    )
    (net (code "298") (name "SW1_CTL3") (class "Default")
      (node (ref "IC31") (pin "19") (pinfunction "V3_19") (pintype "bidirectional"))
      (node (ref "U1") (pin "P5") (pinfunction "IO_L52N_3_P5") (pintype "bidirectional"))
    )
    (net (code "299") (name "SW2_CTL1") (class "Default")
      (node (ref "IC32") (pin "17") (pinfunction "V1_17") (pintype "bidirectional"))
      (node (ref "U1") (pin "P6") (pinfunction "IO_L52P_3_P6") (pintype "bidirectional"))
    )
    (net (code "300") (name "SW2_CTL2") (class "Default")
      (node (ref "IC32") (pin "18") (pinfunction "V2_18") (pintype "bidirectional"))
      (node (ref "U1") (pin "P7") (pinfunction "IO_L51N_3_P7") (pintype "bidirectional"))
    )
    (net (code "301") (name "SW2_CTL3") (class "Default")
      (node (ref "IC32") (pin "19") (pinfunction "V3_19") (pintype "bidirectional"))
      (node (ref "U1") (pin "P8") (pinfunction "IO_L51P_3_P8") (pintype "bidirectional"))
    )
    (net (code "302") (name "SW_DIRECT") (class "Default")
      (node (ref "IC16") (pin "1") (pinfunction "A_1") (pintype "bidirectional"))
      (node (ref "IC17") (pin "2") (pinfunction "B_2") (pintype "bidirectional"))
      (node (ref "Q1") (pin "3") (pinfunction "D_3") (pintype "passive"))
      (node (ref "Q2") (pin "1") (pinfunction "G_1") (pintype "passive"))
      (node (ref "R31") (pin "2") (pinfunction "2_2") (pintype "passive"))
    )
    (net (code "303") (name "SW_HET") (class "Default")
      (node (ref "IC16") (pin "2") (pinfunction "B_2") (pintype "bidirectional"))
      (node (ref "IC17") (pin "1") (pinfunction "A_1") (pintype "bidirectional"))
      (node (ref "Q2") (pin "3") (pinfunction "D_3") (pintype "passive"))
      (node (ref "R32") (pin "2") (pinfunction "2_2") (pintype "passive"))
    )
    (net (code "304") (name "SYNTH_CE") (class "Default")
      (node (ref "IC13") (pin "32") (pinfunction "PA11_32") (pintype "bidirectional"))
      (node (ref "IC2") (pin "4") (pinfunction "CE_4") (pintype "bidirectional"))
      (node (ref "R16") (pin "2") (pinfunction "2_2") (pintype "passive"))
    )
    (net (code "305") (name "SYNTH_LE") (class "Default")
      (node (ref "IC13") (pin "22") (pinfunction "PB11_22") (pintype "bidirectional"))
      (node (ref "IC2") (pin "3") (pinfunction "LE_3") (pintype "input"))
    )
    (net (code "306") (name "SYNTH_LOCK_DETECT") (class "Default")
      (node (ref "IC13") (pin "33") (pinfunction "PA12_33") (pintype "bidirectional"))
      (node (ref "IC2") (pin "25") (pinfunction "LD_25") (pintype "output"))
    )
    (net (code "307") (name "SYNTH_MUX") (class "Default")
      (node (ref "IC13") (pin "21") (pinfunction "PB10_21") (pintype "bidirectional"))
      (node (ref "IC2") (pin "30") (pinfunction "MUX_30") (pintype "bidirectional"))
    )
    (net (code "308") (name "SYNTH_RF_EN") (class "Default")
      (node (ref "IC13") (pin "20") (pinfunction "PB2_20") (pintype "bidirectional"))
      (node (ref "IC2") (pin "26") (pinfunction "RFOUT_EN_26") (pintype "input"))
    )
    (net (code "309") (name "VCCINT") (class "Default")
      (node (ref "C164") (pin "1") (pinfunction "1_1") (pintype "passive"))
      (node (ref "C165") (pin "1") (pinfunction "1_1") (pintype "passive"))
      (node (ref "C171") (pin "1") (pinfunction "1_1") (pintype "passive"))
      (node (ref "C172") (pin "1") (pinfunction "1_1") (pintype "passive"))
      (node (ref "C173") (pin "1") (pinfunction "1_1") (pintype "passive"))
      (node (ref "C174") (pin "1") (pinfunction "1_1") (pintype "passive"))
      (node (ref "L71") (pin "P$2") (pinfunction "2_P$2") (pintype "passive"))
      (node (ref "R15") (pin "1") (pinfunction "1_1") (pintype "passive"))
      (node (ref "U1") (pin "P128") (pinfunction "VCCINT_P128") (pintype "input"))
      (node (ref "U1") (pin "P19") (pinfunction "VCCINT_P19") (pintype "input"))
      (node (ref "U1") (pin "P28") (pinfunction "VCCINT_P28") (pintype "input"))
      (node (ref "U1") (pin "P52") (pinfunction "VCCINT_P52") (pintype "input"))
      (node (ref "U1") (pin "P89") (pinfunction "VCCINT_P89") (pintype "input"))
      (node (ref "X2") (pin "4") (pinfunction "1_4") (pintype "passive"))
    )
    (net (code "310") (name "unconnected-(IC2-RFOUTB_N-Pad15)") (class "Default")
      (node (ref "IC2") (pin "15") (pinfunction "RFOUTB_N_15") (pintype "bidirectional"))
    )
    (net (code "311") (name "unconnected-(IC2-RFOUTB_P-Pad14)") (class "Default")
      (node (ref "IC2") (pin "14") (pinfunction "RFOUTB_P_14") (pintype "bidirectional"))
    )
    (net (code "312") (name "unconnected-(IC13A-PA7-Pad17)") (class "Default")
      (node (ref "IC13") (pin "17") (pinfunction "PA7_17") (pintype "bidirectional"))
    )
    (net (code "313") (name "unconnected-(JTAG-Pad6)") (class "Default")
      (node (ref "JTAG") (pin "6") (pinfunction "6_6") (pintype "passive"))
    )
    (net (code "314") (name "unconnected-(JTAG-Pad7)") (class "Default")
      (node (ref "JTAG") (pin "7") (pinfunction "7_7") (pintype "passive"))
    )
    (net (code "315") (name "unconnected-(JTAG-Pad8)") (class "Default")
      (node (ref "JTAG") (pin "8") (pinfunction "8_8") (pintype "passive"))
    )
    (net (code "316") (name "unconnected-(U1B-IO_L43N_GCLK4_1-PadP84)") (class "Default")
      (node (ref "U1") (pin "P84") (pinfunction "IO_L43N_GCLK4_1_P84") (pintype "bidirectional"))
    )
    (net (code "317") (name "unconnected-(U1B-IO_L43P_GCLK5_1-PadP85)") (class "Default")
      (node (ref "U1") (pin "P85") (pinfunction "IO_L43P_GCLK5_1_P85") (pintype "bidirectional"))
    )
    (net (code "318") (name "unconnected-(U1B-IO_L45N_1-PadP82)") (class "Default")
      (node (ref "U1") (pin "P82") (pinfunction "IO_L45N_1_P82") (pintype "bidirectional"))
    )
    (net (code "319") (name "unconnected-(U1B-IO_L45P_1-PadP83)") (class "Default")
      (node (ref "U1") (pin "P83") (pinfunction "IO_L45P_1_P83") (pintype "bidirectional"))
    )
    (net (code "320") (name "unconnected-(U1B-IO_L46P_1-PadP81)") (class "Default")
      (node (ref "U1") (pin "P81") (pinfunction "IO_L46P_1_P81") (pintype "bidirectional"))
    )
    (net (code "321") (name "unconnected-(U1C-CMPCS_B_2-PadP72)") (class "Default")
      (node (ref "U1") (pin "P72") (pinfunction "CMPCS_B_2_P72") (pintype "bidirectional"))
    )
    (net (code "322") (name "unconnected-(U1C-IO_L2N_CMPMOSI_2-PadP66)") (class "Default")
      (node (ref "U1") (pin "P66") (pinfunction "IO_L2N_CMPMOSI_2_P66") (pintype "bidirectional"))
    )
    (net (code "323") (name "unconnected-(U1C-IO_L2P_CMPCLK_2-PadP67)") (class "Default")
      (node (ref "U1") (pin "P67") (pinfunction "IO_L2P_CMPCLK_2_P67") (pintype "bidirectional"))
    )
    (net (code "324") (name "unconnected-(U1C-IO_L12N_D2_MISO3_2-PadP61)") (class "Default")
      (node (ref "U1") (pin "P61") (pinfunction "IO_L12N_D2_MISO3_2_P61") (pintype "bidirectional"))
    )
    (net (code "325") (name "unconnected-(U1C-IO_L12P_D1_MISO2_2-PadP62)") (class "Default")
      (node (ref "U1") (pin "P62") (pinfunction "IO_L12P_D1_MISO2_2_P62") (pintype "bidirectional"))
    )
    (net (code "326") (name "unconnected-(U1C-IO_L13N_D10_2-PadP59)") (class "Default")
      (node (ref "U1") (pin "P59") (pinfunction "IO_L13N_D10_2_P59") (pintype "bidirectional"))
    )
    (net (code "327") (name "unconnected-(U1C-IO_L14N_D12_2-PadP57)") (class "Default")
      (node (ref "U1") (pin "P57") (pinfunction "IO_L14N_D12_2_P57") (pintype "bidirectional"))
    )
    (net (code "328") (name "unconnected-(U1C-IO_L14P_D11_2-PadP58)") (class "Default")
      (node (ref "U1") (pin "P58") (pinfunction "IO_L14P_D11_2_P58") (pintype "bidirectional"))
    )
    (net (code "329") (name "unconnected-(U1C-IO_L30N_GCLK0_USERCCLK_2-PadP55)") (class "Default")
      (node (ref "U1") (pin "P55") (pinfunction "IO_L30N_GCLK0_USERCCLK_2_P55") (pintype "bidirectional"))
    )
    (net (code "330") (name "unconnected-(U1C-IO_L30P_GCLK1_D13_2-PadP56)") (class "Default")
      (node (ref "U1") (pin "P56") (pinfunction "IO_L30P_GCLK1_D13_2_P56") (pintype "bidirectional"))
    )
    (net (code "331") (name "unconnected-(U1C-IO_L31N_GCLK30_D15_2-PadP50)") (class "Default")
      (node (ref "U1") (pin "P50") (pinfunction "IO_L31N_GCLK30_D15_2_P50") (pintype "bidirectional"))
    )
    (net (code "332") (name "unconnected-(U1C-IO_L31P_GCLK31_D14_2-PadP51)") (class "Default")
      (node (ref "U1") (pin "P51") (pinfunction "IO_L31P_GCLK31_D14_2_P51") (pintype "bidirectional"))
    )
    (net (code "333") (name "unconnected-(U1C-IO_L48N_RDWR_B_VREF_2-PadP47)") (class "Default")
      (node (ref "U1") (pin "P47") (pinfunction "IO_L48N_RDWR_B_VREF_2_P47") (pintype "bidirectional"))
    )
    (net (code "334") (name "unconnected-(U1C-IO_L48P_D7_2-PadP48)") (class "Default")
      (node (ref "U1") (pin "P48") (pinfunction "IO_L48P_D7_2_P48") (pintype "bidirectional"))
    )
    (net (code "335") (name "unconnected-(U1C-IO_L49N_D4_2-PadP45)") (class "Default")
      (node (ref "U1") (pin "P45") (pinfunction "IO_L49N_D4_2_P45") (pintype "bidirectional"))
    )
    (net (code "336") (name "unconnected-(U1C-IO_L49P_D3_2-PadP46)") (class "Default")
      (node (ref "U1") (pin "P46") (pinfunction "IO_L49P_D3_2_P46") (pintype "bidirectional"))
    )
    (net (code "337") (name "unconnected-(U1C-IO_L62N_D6_2-PadP43)") (class "Default")
      (node (ref "U1") (pin "P43") (pinfunction "IO_L62N_D6_2_P43") (pintype "bidirectional"))
    )
    (net (code "338") (name "unconnected-(U1C-IO_L62P_D5_2-PadP44)") (class "Default")
      (node (ref "U1") (pin "P44") (pinfunction "IO_L62P_D5_2_P44") (pintype "bidirectional"))
    )
    (net (code "339") (name "unconnected-(U1C-IO_L64N_D9_2-PadP40)") (class "Default")
      (node (ref "U1") (pin "P40") (pinfunction "IO_L64N_D9_2_P40") (pintype "bidirectional"))
    )
    (net (code "340") (name "unconnected-(U1C-IO_L64P_D8_2-PadP41)") (class "Default")
      (node (ref "U1") (pin "P41") (pinfunction "IO_L64P_D8_2_P41") (pintype "bidirectional"))
    )
    (net (code "341") (name "unconnected-(U1D-IO_L1N_VREF_3-PadP34)") (class "Default")
      (node (ref "U1") (pin "P34") (pinfunction "IO_L1N_VREF_3_P34") (pintype "bidirectional"))
    )
    (net (code "342") (name "unconnected-(U1D-IO_L36N_3-PadP29)") (class "Default")
      (node (ref "U1") (pin "P29") (pinfunction "IO_L36N_3_P29") (pintype "bidirectional"))
    )
    (net (code "343") (name "unconnected-(U1D-IO_L37N_3-PadP26)") (class "Default")
      (node (ref "U1") (pin "P26") (pinfunction "IO_L37N_3_P26") (pintype "bidirectional"))
    )
    (net (code "344") (name "unconnected-(U1D-IO_L37P_3-PadP27)") (class "Default")
      (node (ref "U1") (pin "P27") (pinfunction "IO_L37P_3_P27") (pintype "bidirectional"))
    )
    (net (code "345") (name "unconnected-(U1D-IO_L42P_GCLK25_TRDY2_3-PadP22)") (class "Default")
      (node (ref "U1") (pin "P22") (pinfunction "IO_L42P_GCLK25_TRDY2_3_P22") (pintype "bidirectional"))
    )
    (net (code "346") (name "unconnected-(U1D-IO_L44N_GCLK20_3-PadP14)") (class "Default")
      (node (ref "U1") (pin "P14") (pinfunction "IO_L44N_GCLK20_3_P14") (pintype "bidirectional"))
    )
    (net (code "347") (name "unconnected-(U1D-IO_L49P_3-PadP12)") (class "Default")
      (node (ref "U1") (pin "P12") (pinfunction "IO_L49P_3_P12") (pintype "bidirectional"))
    )
    (net (code "348") (name "{slash}MOD_EN") (class "Default")
      (node (ref "IC1") (pin "7") (pinfunction "EN_7") (pintype "bidirectional"))
      (node (ref "U1") (pin "P11") (pinfunction "IO_L49N_3_P11") (pintype "bidirectional"))
    )
  )
)
